# ProPrj_PEDRO.net
KiCad netlist of a schematic drawn in EasyEDA Pro
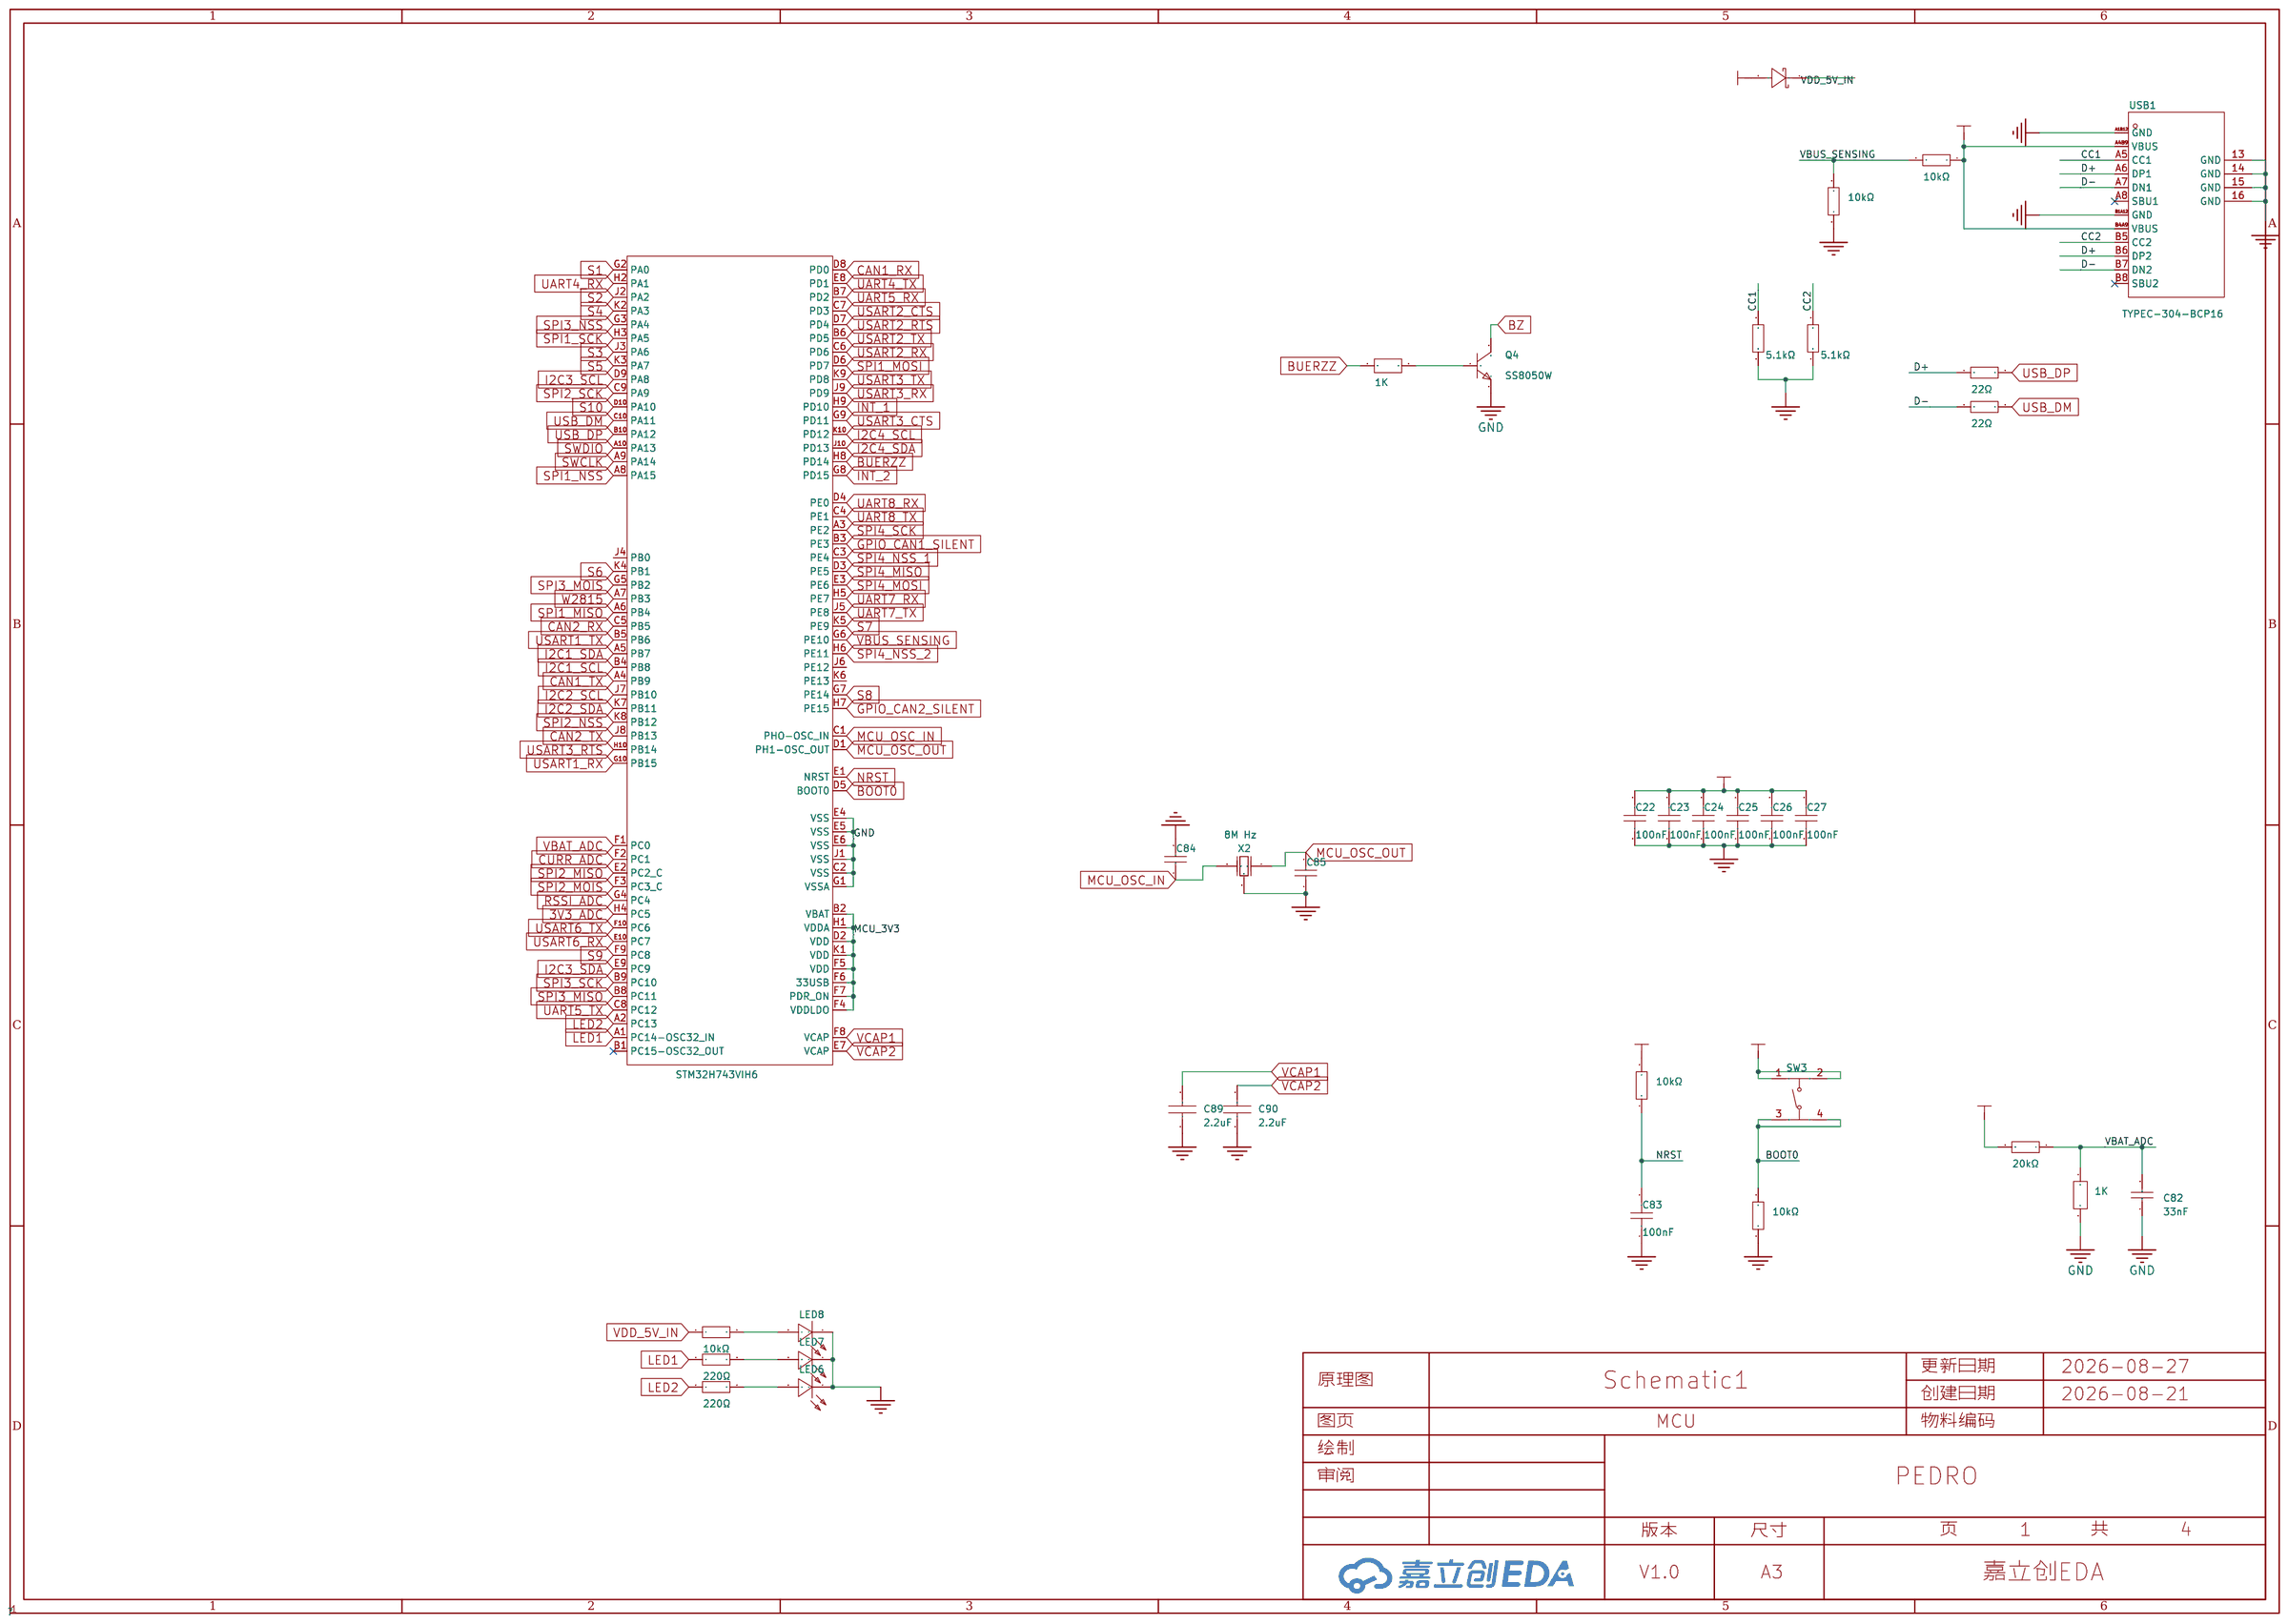
[diagram p0: MCU]
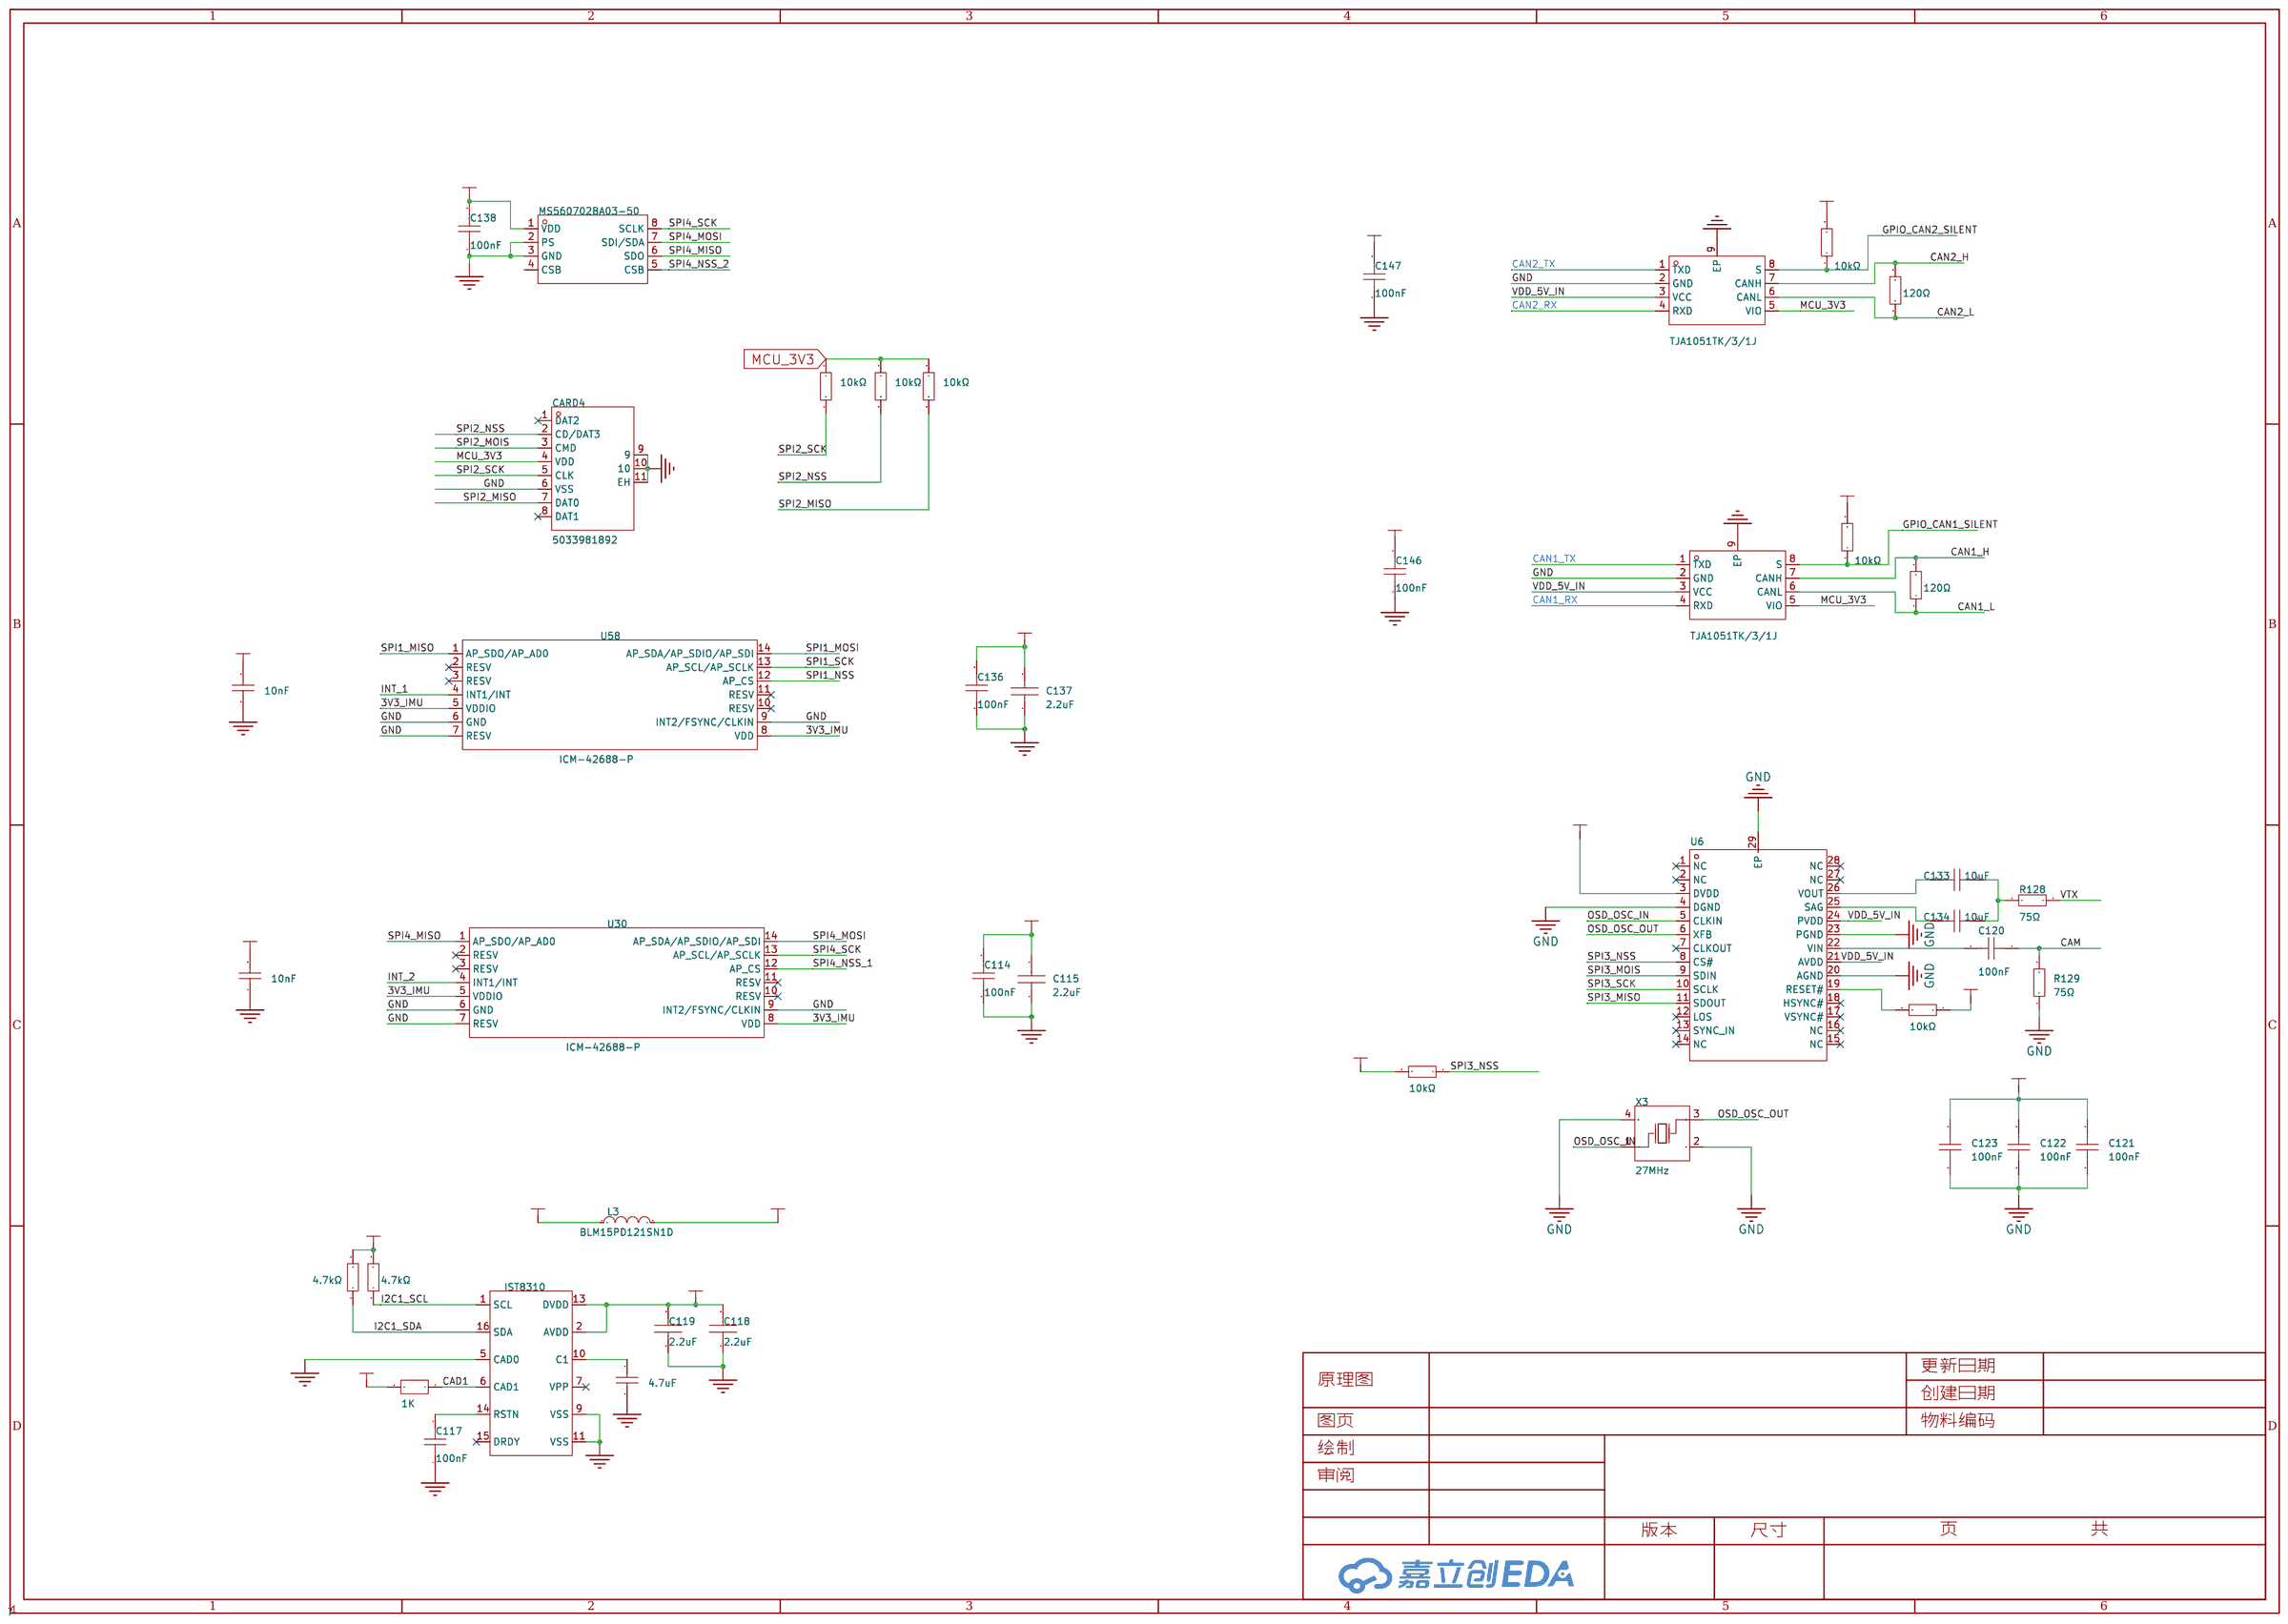
[diagram p1: 传感器]
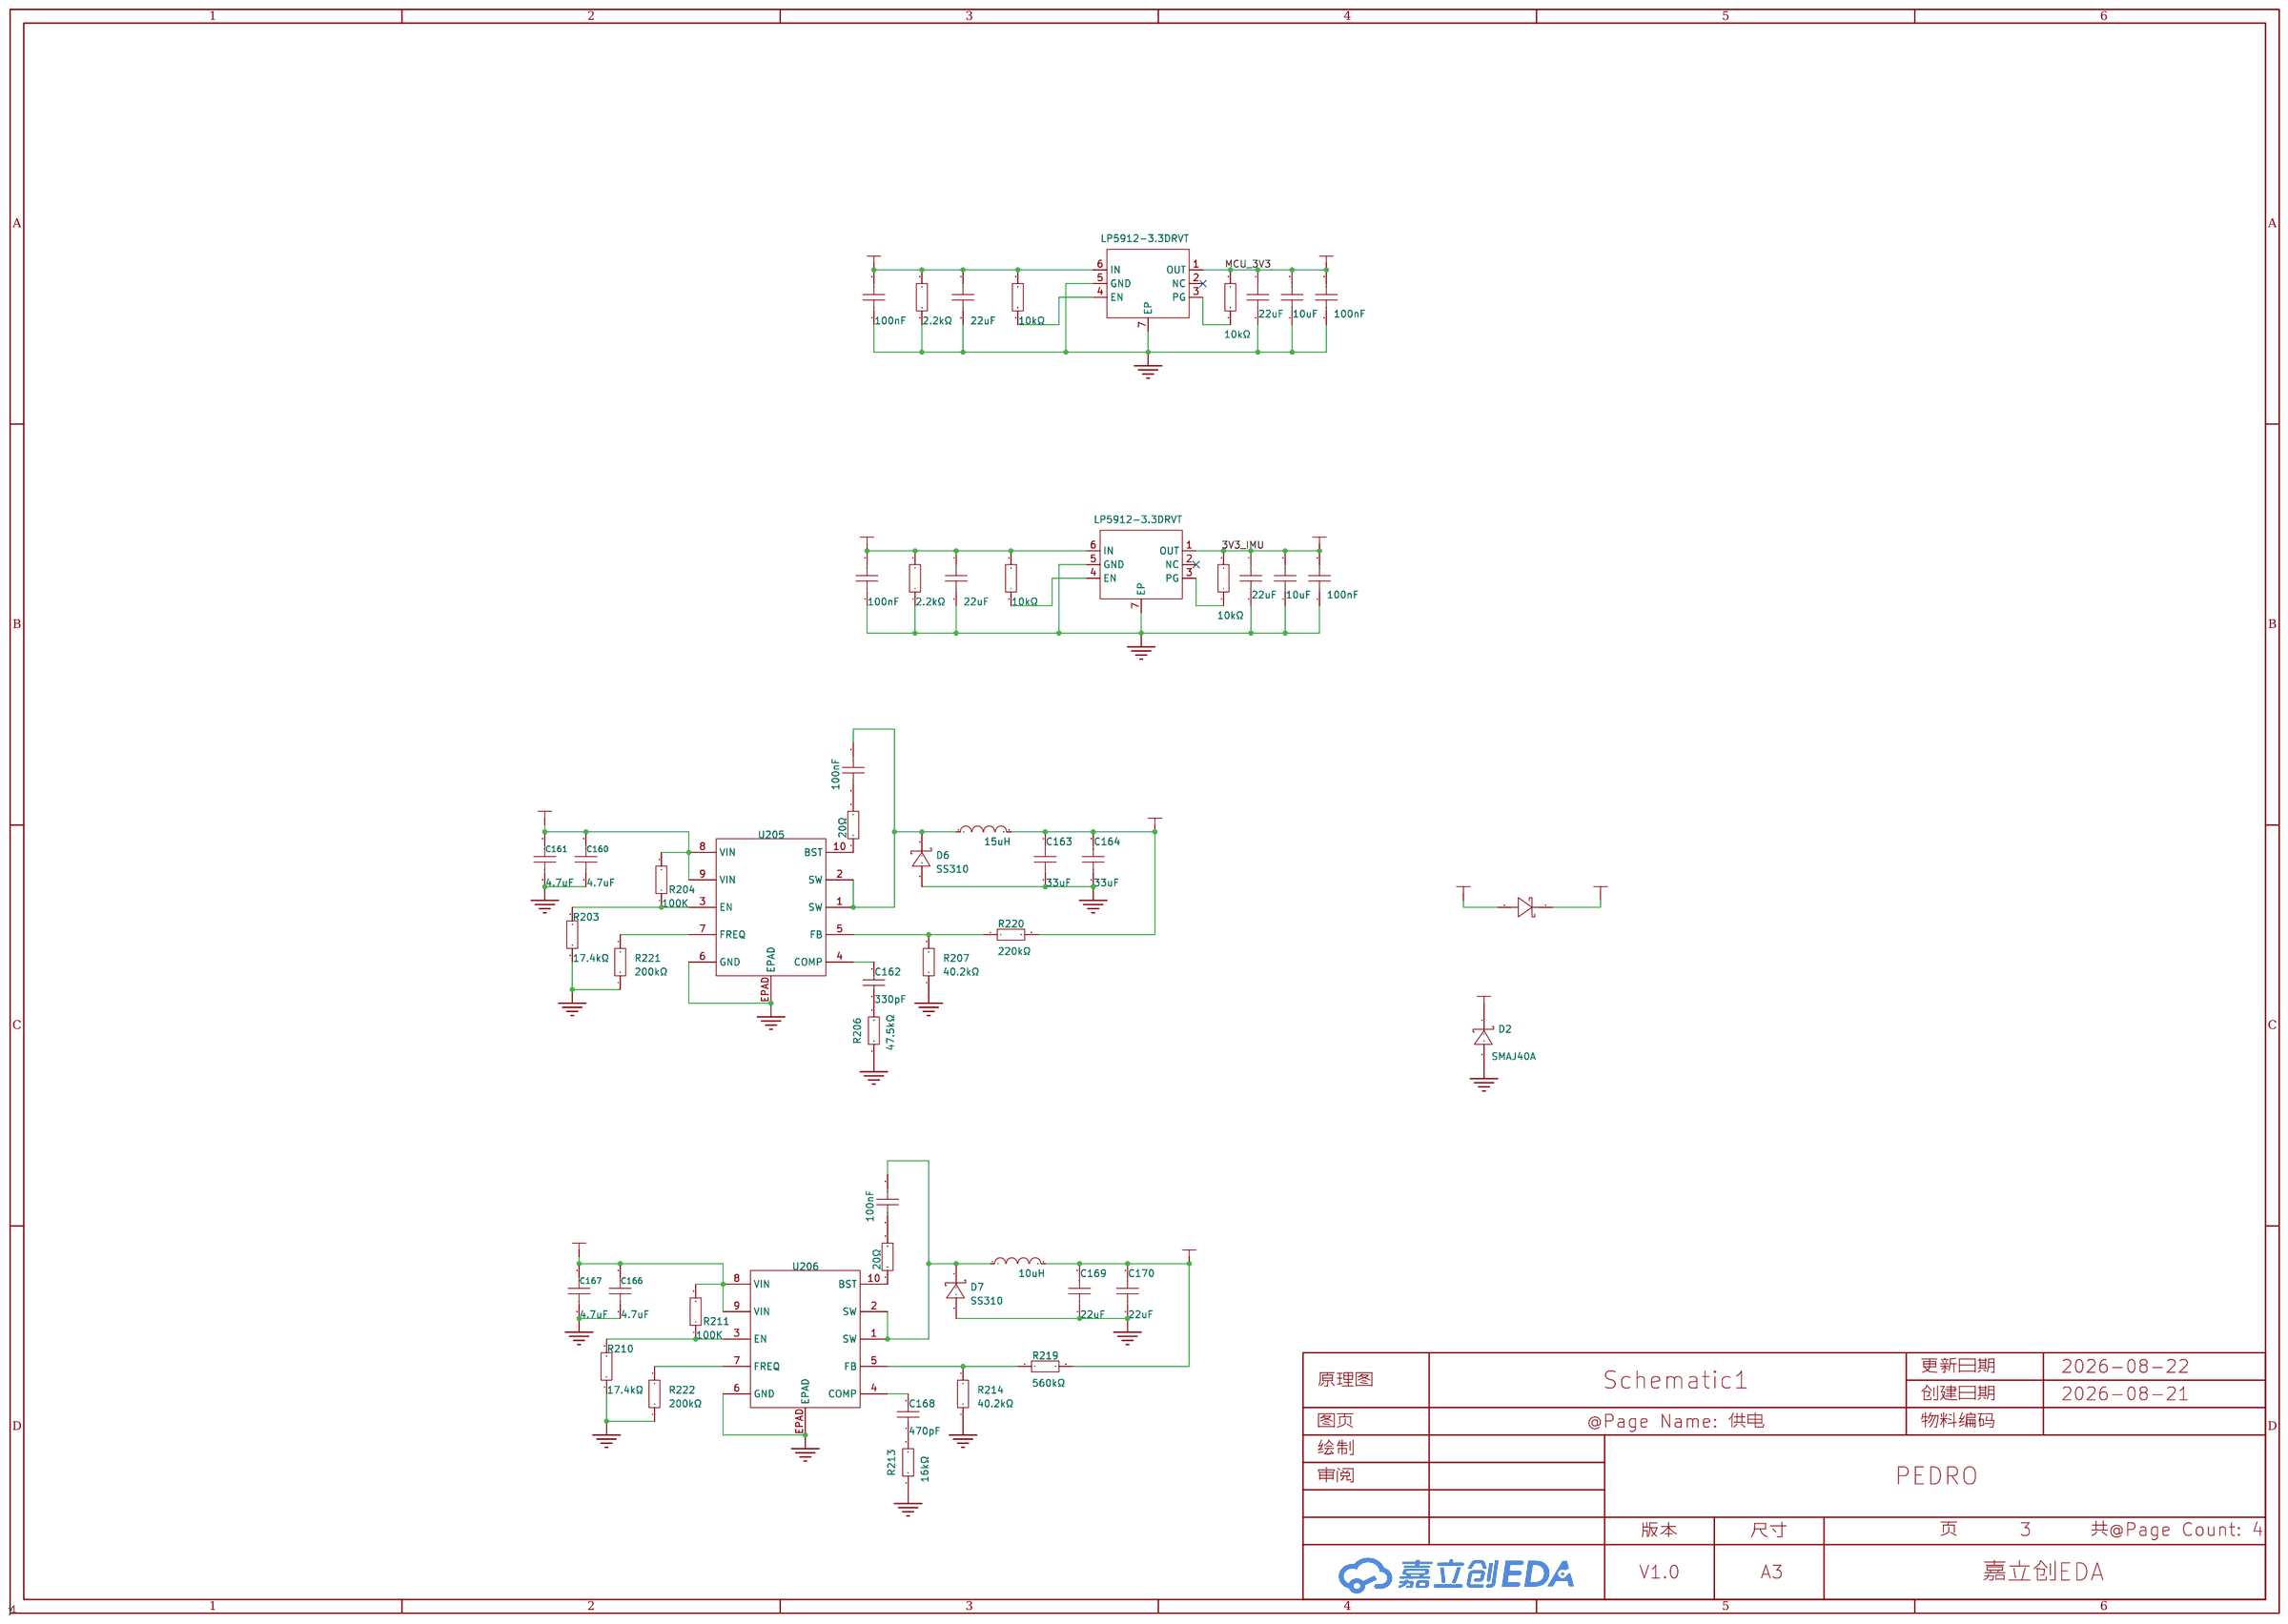
[diagram p2: 供电]
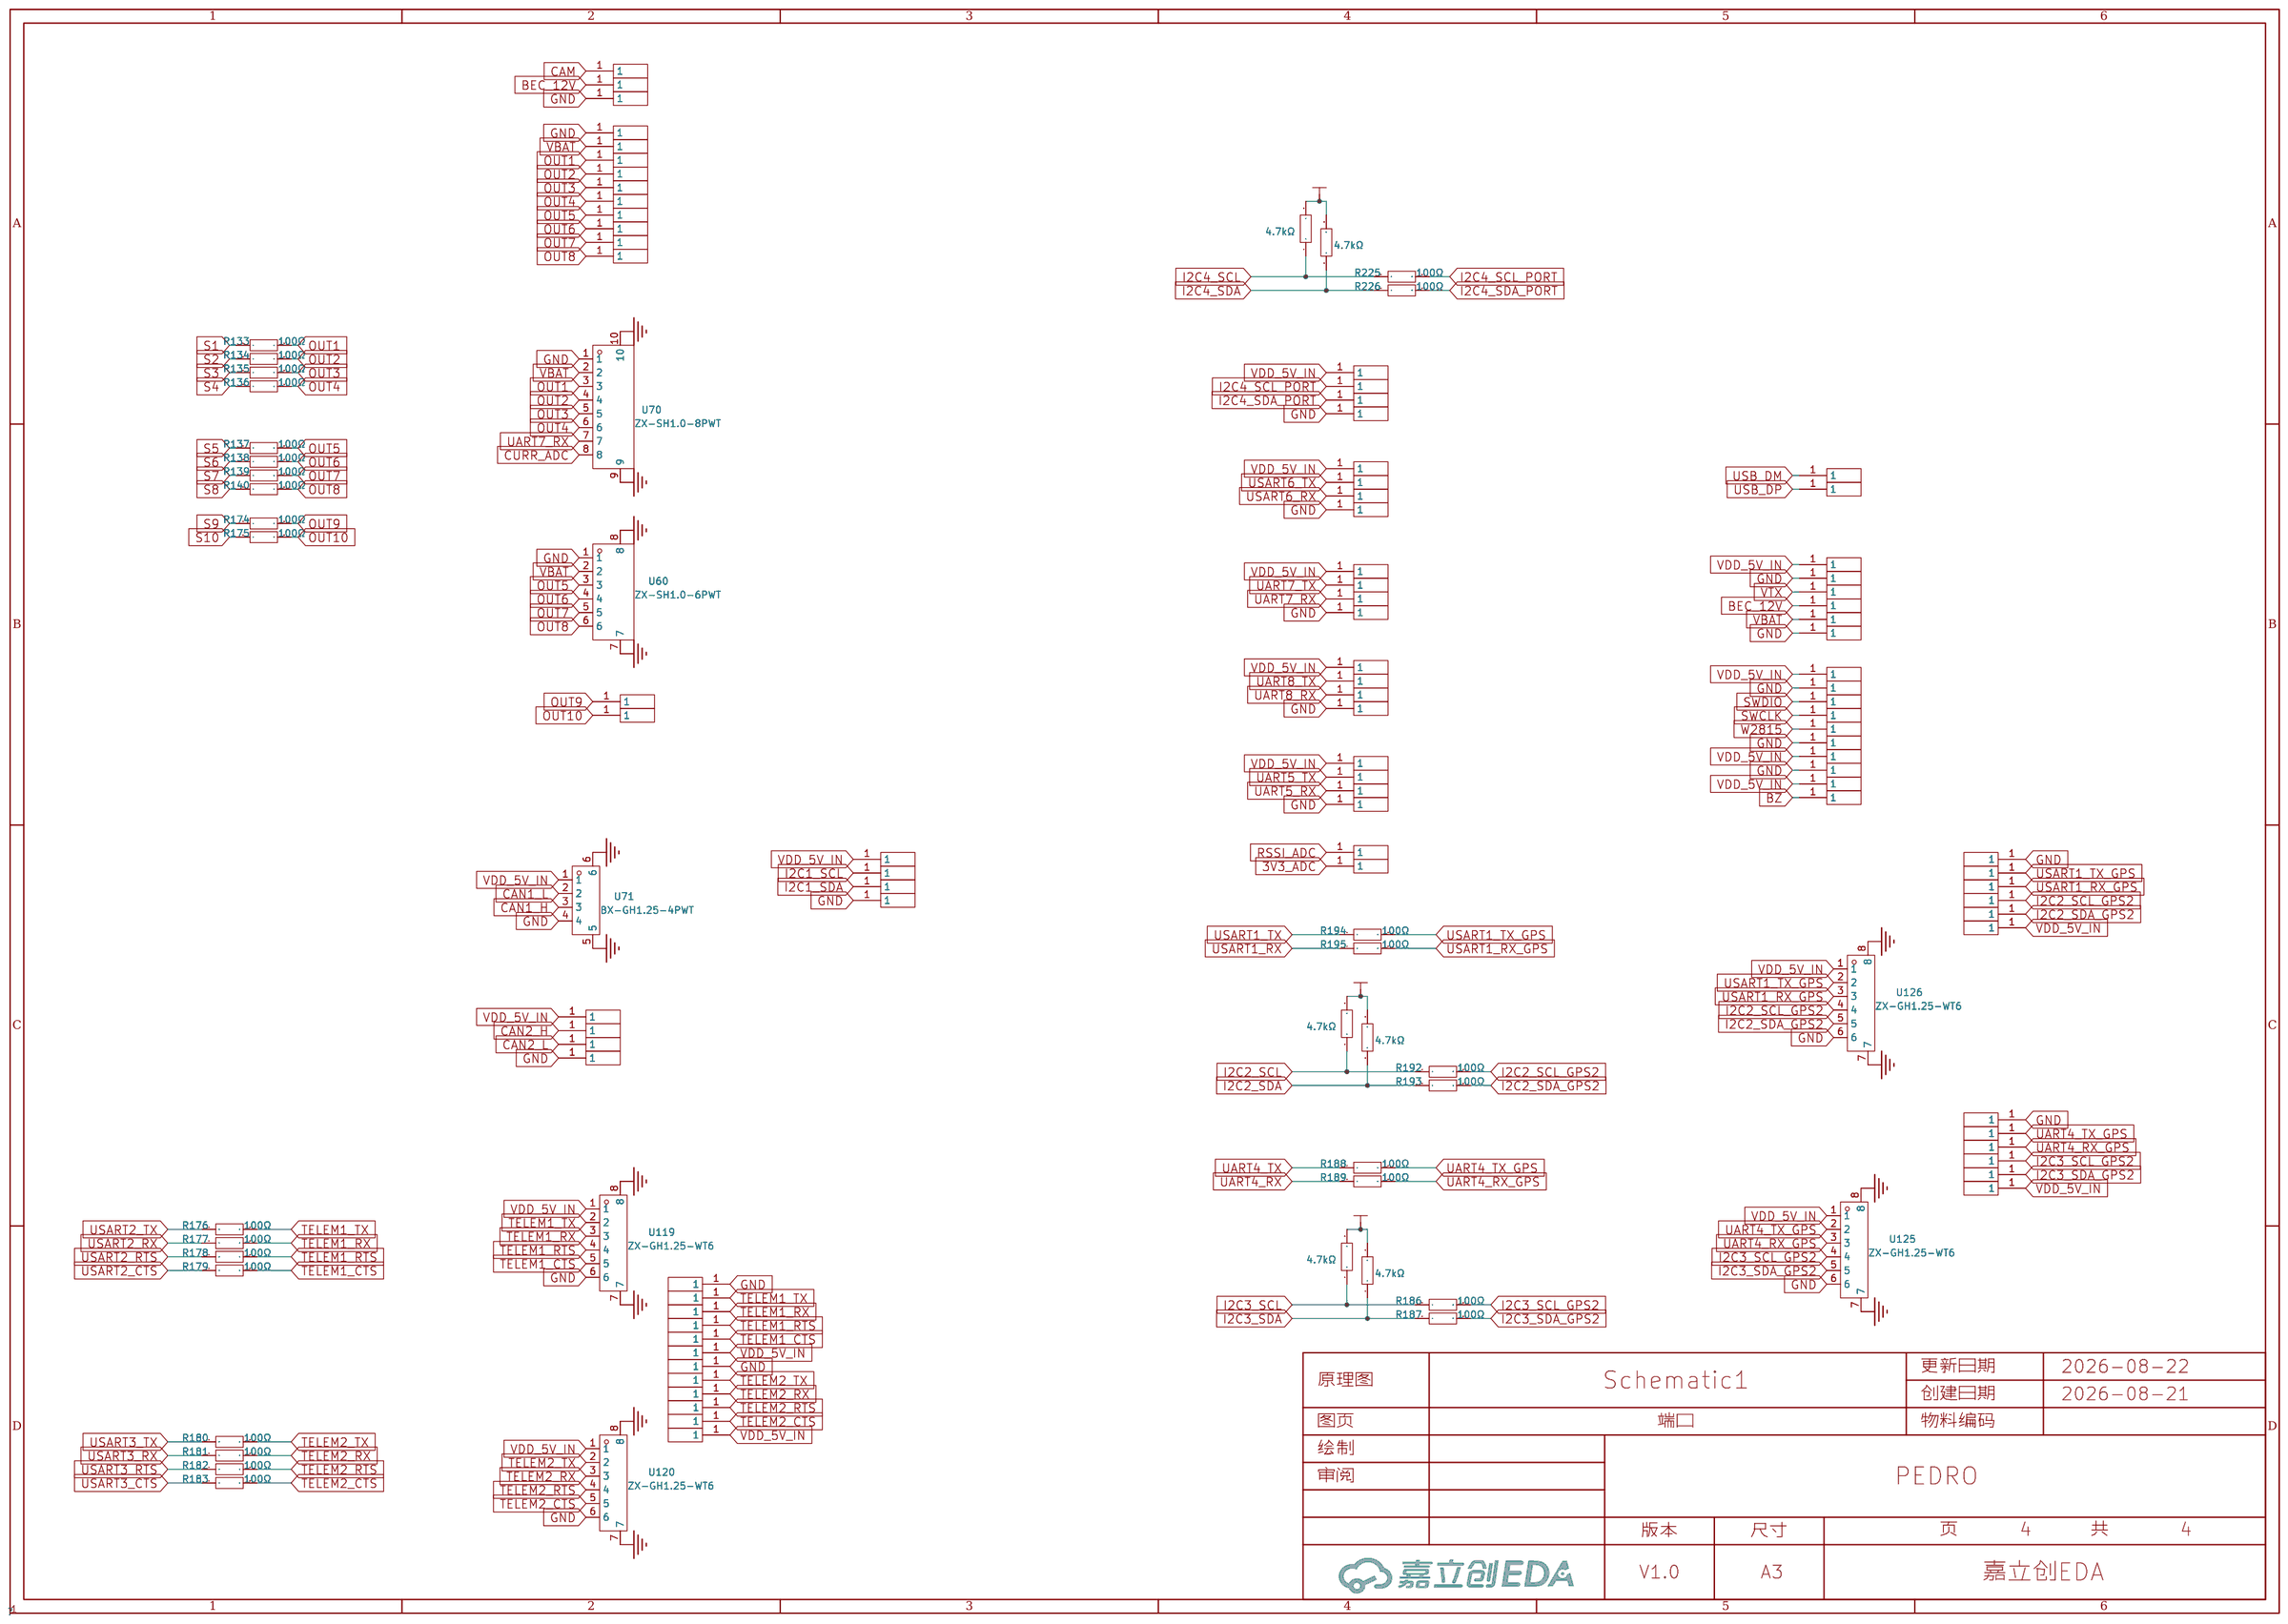
[diagram p3: 端口]

(export (version "E")
  (design (tool "Eeschema 10.0.6"))
  (components
    (comp (ref "C22")
      (value "100nF")
      (footprint "easyedapro:C0402")
      (description "容值:100nF;精度:±10%;额定电压:16V;材质(温度系数):X7R;")
      (fields
        (field (name "Manufacturer Part") "CC0402KRX7R7BB104")
        (field (name "Manufacturer") "YAGEO(国巨)")
      )
      (libsource (lib "easyedapro") (part "CC0402KRX7R7BB104"))
    )
    (comp (ref "C23")
      (value "100nF")
      (footprint "easyedapro:C0402")
      (description "容值:100nF;精度:±10%;额定电压:16V;材质(温度系数):X7R;")
      (fields
        (field (name "Manufacturer Part") "CC0402KRX7R7BB104")
        (field (name "Manufacturer") "YAGEO(国巨)")
      )
      (libsource (lib "easyedapro") (part "CC0402KRX7R7BB104"))
    )
    (comp (ref "C24")
      (value "100nF")
      (footprint "easyedapro:C0402")
      (description "容值:100nF;精度:±10%;额定电压:16V;材质(温度系数):X7R;")
      (fields
        (field (name "Manufacturer Part") "CC0402KRX7R7BB104")
        (field (name "Manufacturer") "YAGEO(国巨)")
      )
      (libsource (lib "easyedapro") (part "CC0402KRX7R7BB104"))
    )
    (comp (ref "C25")
      (value "100nF")
      (footprint "easyedapro:C0402")
      (description "容值:100nF;精度:±10%;额定电压:16V;材质(温度系数):X7R;")
      (fields
        (field (name "Manufacturer Part") "CC0402KRX7R7BB104")
        (field (name "Manufacturer") "YAGEO(国巨)")
      )
      (libsource (lib "easyedapro") (part "CC0402KRX7R7BB104"))
    )
    (comp (ref "C26")
      (value "100nF")
      (footprint "easyedapro:C0402")
      (description "容值:100nF;精度:±10%;额定电压:16V;材质(温度系数):X7R;")
      (fields
        (field (name "Manufacturer Part") "CC0402KRX7R7BB104")
        (field (name "Manufacturer") "YAGEO(国巨)")
      )
      (libsource (lib "easyedapro") (part "CC0402KRX7R7BB104"))
    )
    (comp (ref "C27")
      (value "100nF")
      (footprint "easyedapro:C0402")
      (description "容值:100nF;精度:±10%;额定电压:16V;材质(温度系数):X7R;")
      (fields
        (field (name "Manufacturer Part") "CC0402KRX7R7BB104")
        (field (name "Manufacturer") "YAGEO(国巨)")
      )
      (libsource (lib "easyedapro") (part "CC0402KRX7R7BB104"))
    )
    (comp (ref "C82")
      (value "33nF")
      (footprint "easyedapro:C0402")
      (description "容值:33nF;精度:±10%;额定电压:50V;材质(温度系数):X7R;")
      (fields
        (field (name "Manufacturer Part") "CC0402KRX7R9BB333")
        (field (name "Manufacturer") "YAGEO(国巨)")
      )
      (libsource (lib "easyedapro") (part "CC0402KRX7R9BB333"))
    )
    (comp (ref "C83")
      (value "100nF")
      (footprint "easyedapro:C0402")
      (description "容值:100nF;精度:±10%;额定电压:16V;材质(温度系数):X7R;")
      (fields
        (field (name "Manufacturer Part") "CC0402KRX7R7BB104")
        (field (name "Manufacturer") "YAGEO(国巨)")
      )
      (libsource (lib "easyedapro") (part "CC0402KRX7R7BB104"))
    )
    (comp (ref "C84")
      (value "12pF")
      (footprint "easyedapro:C0402")
      (description "容值:12pF;精度:±5%;额定电压:50V;材质(温度系数):C0G;")
      (fields (field (name "Manufacturer Part") "0402CG120J500NT") (field (name "Manufacturer") "FH(风华)"))
      (libsource (lib "easyedapro") (part "0402CG120J500NT"))
    )
    (comp (ref "C85")
      (value "12pF")
      (footprint "easyedapro:C0402")
      (description "容值:12pF;精度:±5%;额定电压:50V;材质(温度系数):C0G;")
      (fields (field (name "Manufacturer Part") "0402CG120J500NT") (field (name "Manufacturer") "FH(风华)"))
      (libsource (lib "easyedapro") (part "0402CG120J500NT"))
    )
    (comp (ref "C89")
      (value "2.2uF")
      (footprint "easyedapro:C0402")
      (description "容值:2.2uF;精度:±20%;额定电压:6.3V;材质(温度系数):X5R;")
      (fields
        (field (name "Manufacturer Part") "CL05A225MQ5NSNC")
        (field (name "Manufacturer") "SAMSUNG(三星)")
      )
      (libsource (lib "easyedapro") (part "CL05A225MQ5NSNC"))
    )
    (comp (ref "C90")
      (value "2.2uF")
      (footprint "easyedapro:C0402")
      (description "容值:2.2uF;精度:±20%;额定电压:6.3V;材质(温度系数):X5R;")
      (fields
        (field (name "Manufacturer Part") "CL05A225MQ5NSNC")
        (field (name "Manufacturer") "SAMSUNG(三星)")
      )
      (libsource (lib "easyedapro") (part "CL05A225MQ5NSNC"))
    )
    (comp (ref "D4")
      (value "DSK34")
      (footprint "easyedapro:SOD-123_L2.8-W1.8-LS3.7-RD")
      (description "二极管配置:-;正向压降(Vf):550mV@3A;直流反向耐压(Vr):40V;平均整流电流(Io):3A;")
      (fields (field (name "Manufacturer") "FUXINSEMI(富芯森美)"))
      (libsource (lib "easyedapro") (part "DSK34_C908230"))
    )
    (comp (ref "LED6")
      (value "NCD0402R1")
      (footprint "easyedapro:LED0402-RD")
      (fields (field (name "Manufacturer") "国星光电"))
      (libsource (lib "easyedapro") (part "FC-F1005HRK-620H5"))
    )
    (comp (ref "LED7")
      (value "NCD0402R1")
      (footprint "easyedapro:LED0402-RD")
      (fields (field (name "Manufacturer") "国星光电"))
      (libsource (lib "easyedapro") (part "FC-F1005HRK-620H5"))
    )
    (comp (ref "LED8")
      (value "NCD0402R1")
      (footprint "easyedapro:LED0402-RD")
      (fields (field (name "Manufacturer") "国星光电"))
      (libsource (lib "easyedapro") (part "FC-F1005HRK-620H5"))
    )
    (comp (ref "Q4")
      (value "SS8050W")
      (footprint "easyedapro:SOT-323-3_L2.1-W1.3-P1.30-LS2.3-BR")
      (description "晶体管类型:-;集电极电流(Ic):-;集射极击穿电压(Vceo):-;功率(Pd):-;")
      (fields (field (name "Manufacturer") "CBI(创基)"))
      (libsource (lib "easyedapro") (part "SS8050W"))
    )
    (comp (ref "R99")
      (value "5.1kΩ")
      (footprint "easyedapro:R0402")
      (description "电阻类型:厚膜电阻;阻值:5.1kΩ;精度:±1%;功率:62.5mW;最大工作电压:50V;温度系数:±100ppm/°C;")
      (fields
        (field (name "Manufacturer Part") "0402WGF5101TCE")
        (field (name "Manufacturer") "UNI-ROYAL(厚声)")
      )
      (libsource (lib "easyedapro") (part "0402WGF5101TCE"))
    )
    (comp (ref "R100")
      (value "5.1kΩ")
      (footprint "easyedapro:R0402")
      (description "电阻类型:厚膜电阻;阻值:5.1kΩ;精度:±1%;功率:62.5mW;最大工作电压:50V;温度系数:±100ppm/°C;")
      (fields
        (field (name "Manufacturer Part") "0402WGF5101TCE")
        (field (name "Manufacturer") "UNI-ROYAL(厚声)")
      )
      (libsource (lib "easyedapro") (part "0402WGF5101TCE"))
    )
    (comp (ref "R101")
      (value "22Ω")
      (footprint "easyedapro:R0402")
      (description "电阻类型:厚膜电阻;阻值:22Ω;精度:±1%;功率:62.5mW;最大工作电压:50V;温度系数:±100ppm/°C;")
      (fields
        (field (name "Manufacturer Part") "0402WGF220JTCE")
        (field (name "Manufacturer") "UNI-ROYAL(厚声)")
      )
      (libsource (lib "easyedapro") (part "0402WGF220JTCE"))
    )
    (comp (ref "R102")
      (value "22Ω")
      (footprint "easyedapro:R0402")
      (description "电阻类型:厚膜电阻;阻值:22Ω;精度:±1%;功率:62.5mW;最大工作电压:50V;温度系数:±100ppm/°C;")
      (fields
        (field (name "Manufacturer Part") "0402WGF220JTCE")
        (field (name "Manufacturer") "UNI-ROYAL(厚声)")
      )
      (libsource (lib "easyedapro") (part "0402WGF220JTCE"))
    )
    (comp (ref "R108")
      (value "10kΩ")
      (footprint "easyedapro:R0402")
      (description "电阻类型:厚膜电阻;阻值:10kΩ;精度:±1%;功率:62.5mW;最大工作电压:50V;温度系数:±100ppm/°C;")
      (fields (field (name "Manufacturer Part") "RC0402FR-0710KL") (field (name "Manufacturer") "YAGEO(国巨)"))
      (libsource (lib "easyedapro") (part "RC0402FR-0710KL"))
    )
    (comp (ref "R109")
      (value "10kΩ")
      (footprint "easyedapro:R0402")
      (description "电阻类型:厚膜电阻;阻值:10kΩ;精度:±1%;功率:62.5mW;最大工作电压:50V;温度系数:±100ppm/°C;")
      (fields (field (name "Manufacturer Part") "RC0402FR-0710KL") (field (name "Manufacturer") "YAGEO(国巨)"))
      (libsource (lib "easyedapro") (part "RC0402FR-0710KL"))
    )
    (comp (ref "R118")
      (value "10kΩ")
      (footprint "easyedapro:R0402")
      (description "电阻类型:厚膜电阻;阻值:10kΩ;精度:±1%;功率:62.5mW;最大工作电压:50V;温度系数:±100ppm/°C;")
      (fields (field (name "Manufacturer Part") "RC0402FR-0710KL") (field (name "Manufacturer") "YAGEO(国巨)"))
      (libsource (lib "easyedapro") (part "RC0402FR-0710KL"))
    )
    (comp (ref "R119")
      (value "10kΩ")
      (footprint "easyedapro:R0402")
      (description "电阻类型:厚膜电阻;阻值:10kΩ;精度:±1%;功率:62.5mW;最大工作电压:50V;温度系数:±100ppm/°C;")
      (fields (field (name "Manufacturer Part") "RC0402FR-0710KL") (field (name "Manufacturer") "YAGEO(国巨)"))
      (libsource (lib "easyedapro") (part "RC0402FR-0710KL"))
    )
    (comp (ref "R143")
      (value "10kΩ")
      (footprint "easyedapro:R0402")
      (description "电阻类型:厚膜电阻;阻值:10kΩ;精度:±1%;功率:62.5mW;最大工作电压:50V;温度系数:±100ppm/°C;")
      (fields (field (name "Manufacturer Part") "RC0402FR-0710KL") (field (name "Manufacturer") "YAGEO(国巨)"))
      (libsource (lib "easyedapro") (part "RC0402FR-0710KL"))
    )
    (comp (ref "R170")
      (value "20kΩ")
      (footprint "easyedapro:R0402")
      (description "电阻类型:厚膜电阻;阻值:10kΩ;精度:±1%;功率:62.5mW;最大工作电压:50V;温度系数:±100ppm/°C;")
      (fields (field (name "Manufacturer Part") "RC0402FR-0710KL") (field (name "Manufacturer") "YAGEO(国巨)"))
      (libsource (lib "easyedapro") (part "RC0402FR-0710KL"))
    )
    (comp (ref "R171")
      (value "1K")
      (footprint "easyedapro:R0402")
      (description "电阻类型:厚膜电阻;阻值:22Ω;精度:±1%;功率:200mW;温度系数:±100ppm/°C;最大工作电压:-;工作温度范围:-55°C~+155°C;")
      (fields (field (name "Manufacturer Part") "ERJPA2F22R0X") (field (name "Manufacturer") "PANASONIC(松下)"))
      (libsource (lib "easyedapro") (part "ERJPA2F22R0X"))
    )
    (comp (ref "R228")
      (value "1K")
      (footprint "easyedapro:R0402")
      (description "电阻类型:厚膜电阻;阻值:22Ω;精度:±1%;功率:200mW;温度系数:±100ppm/°C;最大工作电压:-;工作温度范围:-55°C~+155°C;")
      (fields (field (name "Manufacturer Part") "ERJPA2F22R0X") (field (name "Manufacturer") "PANASONIC(松下)"))
      (libsource (lib "easyedapro") (part "ERJPA2F22R0X"))
    )
    (comp (ref "R229")
      (value "220Ω")
      (footprint "easyedapro:R0402")
      (description "电阻类型:厚膜电阻;阻值:220Ω;精度:±1%;功率:62.5mW;最大工作电压:50V;温度系数:±100ppm/°C;")
      (fields
        (field (name "Manufacturer Part") "0402WGF2200TCE")
        (field (name "Manufacturer") "UNI-ROYAL(厚声)")
      )
      (libsource (lib "easyedapro") (part "0402WGF2200TCE"))
    )
    (comp (ref "R230")
      (value "220Ω")
      (footprint "easyedapro:R0402")
      (description "电阻类型:厚膜电阻;阻值:220Ω;精度:±1%;功率:62.5mW;最大工作电压:50V;温度系数:±100ppm/°C;")
      (fields
        (field (name "Manufacturer Part") "0402WGF2200TCE")
        (field (name "Manufacturer") "UNI-ROYAL(厚声)")
      )
      (libsource (lib "easyedapro") (part "0402WGF2200TCE"))
    )
    (comp (ref "SW3")
      (value "TS-1089S-02526")
      (footprint "easyedapro:SW-SMD_4P-L4.2-W3.3-P2.15-LS5.1")
      (description "电路结构:单刀单掷;按钮形状:椭圆形按钮;安装方式:立贴;开关长度:4.2mm;开关宽度:3.25mm;开关高度:2.5mm;触点电流:50mA;额定电压(DC):12V;带灯:-;机械寿命:-;")
      (fields (field (name "Manufacturer") "XUNPU(讯普)"))
      (libsource (lib "easyedapro") (part "TS-1089S-02526"))
    )
    (comp (ref "U65")
      (value "STM32H743VIH6")
      (footprint "easyedapro:BGA-100_L8.0-W8.0-P0.80-R10-C10-BL")
      (description "32位Arm Cortex -M7 480MHz mcu,高达2MB的Flash,高达1MB的RAM,46com和模拟接口")
      (fields (field (name "Manufacturer") "ST(意法半导体)"))
      (libsource (lib "easyedapro") (part "STM32H743VIH6"))
    )
    (comp (ref "USB1")
      (value "TYPEC-304-BCP16")
      (footprint "easyedapro:USB-C-SMD_TYPEC-304-BCP16_2")
      (fields (field (name "Manufacturer") "XUNPU(讯普)"))
      (libsource (lib "easyedapro") (part "TYPEC-304-BCP16_2"))
    )
    (comp (ref "X2")
      (value "8M Hz")
      (footprint "easyedapro:OSC-SMD_3P-L3.2-W1.3-P1.20-L")
      (fields
        (field (name "Manufacturer Part") "CSTNE8M00GH5C000R0")
        (field (name "Manufacturer") "muRata(村田)")
      )
      (libsource (lib "easyedapro") (part "CSTNE8M00GH5C000R0"))
    )
    (comp (ref "C32")
      (value "10nF")
      (footprint "easyedapro:C0402")
      (description "容值:10nF;精度:±10%;额定电压:50V;材质(温度系数):X7R;")
      (fields
        (field (name "Manufacturer Part") "CC0402KRX7R9BB103")
        (field (name "Manufacturer") "YAGEO(国巨)")
      )
      (libsource (lib "easyedapro") (part "CC0402KRX7R9BB103"))
    )
    (comp (ref "C102")
      (value "4.7uF")
      (footprint "easyedapro:C0402")
      (description "容值:4.7uF;精度:±20%;额定电压:10V;材质(温度系数):X5R;")
      (fields
        (field (name "Manufacturer Part") "CL05A475MP5NRNC")
        (field (name "Manufacturer") "SAMSUNG(三星)")
      )
      (libsource (lib "easyedapro") (part "CL05A475MP5NRNC"))
    )
    (comp (ref "C114")
      (value "100nF")
      (footprint "easyedapro:C0402")
      (description "容值:100nF;精度:±10%;额定电压:16V;材质(温度系数):X7R;")
      (fields
        (field (name "Manufacturer Part") "CC0402KRX7R7BB104")
        (field (name "Manufacturer") "YAGEO(国巨)")
      )
      (libsource (lib "easyedapro") (part "CC0402KRX7R7BB104"))
    )
    (comp (ref "C115")
      (value "2.2uF")
      (footprint "easyedapro:C0402")
      (description "容值:2.2uF;精度:±20%;额定电压:6.3V;材质(温度系数):X5R;")
      (fields
        (field (name "Manufacturer Part") "CL05A225MQ5NSNC")
        (field (name "Manufacturer") "SAMSUNG(三星)")
      )
      (libsource (lib "easyedapro") (part "CL05A225MQ5NSNC"))
    )
    (comp (ref "C117")
      (value "100nF")
      (footprint "easyedapro:C0402")
      (description "容值:100nF;精度:±10%;额定电压:16V;材质(温度系数):X7R;")
      (fields
        (field (name "Manufacturer Part") "CC0402KRX7R7BB104")
        (field (name "Manufacturer") "YAGEO(国巨)")
      )
      (libsource (lib "easyedapro") (part "CC0402KRX7R7BB104"))
    )
    (comp (ref "C118")
      (value "2.2uF")
      (footprint "easyedapro:C0402")
      (description "容值:2.2uF;精度:±20%;额定电压:6.3V;材质(温度系数):X5R;")
      (fields
        (field (name "Manufacturer Part") "CL05A225MQ5NSNC")
        (field (name "Manufacturer") "SAMSUNG(三星)")
      )
      (libsource (lib "easyedapro") (part "CL05A225MQ5NSNC"))
    )
    (comp (ref "C119")
      (value "2.2uF")
      (footprint "easyedapro:C0402")
      (description "容值:2.2uF;精度:±20%;额定电压:6.3V;材质(温度系数):X5R;")
      (fields
        (field (name "Manufacturer Part") "CL05A225MQ5NSNC")
        (field (name "Manufacturer") "SAMSUNG(三星)")
      )
      (libsource (lib "easyedapro") (part "CL05A225MQ5NSNC"))
    )
    (comp (ref "C120")
      (value "100nF")
      (footprint "easyedapro:C0402")
      (description "容值:100nF;精度:±10%;额定电压:16V;材质(温度系数):X7R;")
      (fields
        (field (name "Manufacturer Part") "CC0402KRX7R7BB104")
        (field (name "Manufacturer") "YAGEO(国巨)")
      )
      (libsource (lib "easyedapro") (part "CC0402KRX7R7BB104"))
    )
    (comp (ref "C121")
      (value "100nF")
      (footprint "easyedapro:C0402")
      (description "容值:100nF;精度:±10%;额定电压:16V;材质(温度系数):X7R;")
      (fields
        (field (name "Manufacturer Part") "CC0402KRX7R7BB104")
        (field (name "Manufacturer") "YAGEO(国巨)")
      )
      (libsource (lib "easyedapro") (part "CC0402KRX7R7BB104"))
    )
    (comp (ref "C122")
      (value "100nF")
      (footprint "easyedapro:C0402")
      (description "容值:100nF;精度:±10%;额定电压:16V;材质(温度系数):X7R;")
      (fields
        (field (name "Manufacturer Part") "CC0402KRX7R7BB104")
        (field (name "Manufacturer") "YAGEO(国巨)")
      )
      (libsource (lib "easyedapro") (part "CC0402KRX7R7BB104"))
    )
    (comp (ref "C123")
      (value "100nF")
      (footprint "easyedapro:C0402")
      (description "容值:100nF;精度:±10%;额定电压:16V;材质(温度系数):X7R;")
      (fields
        (field (name "Manufacturer Part") "CC0402KRX7R7BB104")
        (field (name "Manufacturer") "YAGEO(国巨)")
      )
      (libsource (lib "easyedapro") (part "CC0402KRX7R7BB104"))
    )
    (comp (ref "C133")
      (value "10uF")
      (footprint "easyedapro:C0603")
      (description "容值:10uF;精度:±10%;额定电压:10V;材质(温度系数):X5R;")
      (fields
        (field (name "Manufacturer Part") "CL10A106KP8NNNC")
        (field (name "Manufacturer") "SAMSUNG(三星)")
      )
      (libsource (lib "easyedapro") (part "CL10A106KP8NNNC"))
    )
    (comp (ref "C134")
      (value "10uF")
      (footprint "easyedapro:C0603")
      (description "容值:10uF;精度:±10%;额定电压:10V;材质(温度系数):X5R;")
      (fields
        (field (name "Manufacturer Part") "CL10A106KP8NNNC")
        (field (name "Manufacturer") "SAMSUNG(三星)")
      )
      (libsource (lib "easyedapro") (part "CL10A106KP8NNNC"))
    )
    (comp (ref "C135")
      (value "10nF")
      (footprint "easyedapro:C0402")
      (description "容值:10nF;精度:±10%;额定电压:50V;材质(温度系数):X7R;")
      (fields
        (field (name "Manufacturer Part") "CC0402KRX7R9BB103")
        (field (name "Manufacturer") "YAGEO(国巨)")
      )
      (libsource (lib "easyedapro") (part "CC0402KRX7R9BB103"))
    )
    (comp (ref "C136")
      (value "100nF")
      (footprint "easyedapro:C0402")
      (description "容值:100nF;精度:±10%;额定电压:16V;材质(温度系数):X7R;")
      (fields
        (field (name "Manufacturer Part") "CC0402KRX7R7BB104")
        (field (name "Manufacturer") "YAGEO(国巨)")
      )
      (libsource (lib "easyedapro") (part "CC0402KRX7R7BB104"))
    )
    (comp (ref "C137")
      (value "2.2uF")
      (footprint "easyedapro:C0402")
      (description "容值:2.2uF;精度:±20%;额定电压:6.3V;材质(温度系数):X5R;")
      (fields
        (field (name "Manufacturer Part") "CL05A225MQ5NSNC")
        (field (name "Manufacturer") "SAMSUNG(三星)")
      )
      (libsource (lib "easyedapro") (part "CL05A225MQ5NSNC"))
    )
    (comp (ref "C138")
      (value "100nF")
      (footprint "easyedapro:C0402")
      (description "容值:100nF;精度:±10%;额定电压:16V;材质(温度系数):X7R;")
      (fields
        (field (name "Manufacturer Part") "CC0402KRX7R7BB104")
        (field (name "Manufacturer") "YAGEO(国巨)")
      )
      (libsource (lib "easyedapro") (part "CC0402KRX7R7BB104"))
    )
    (comp (ref "C146")
      (value "100nF")
      (footprint "easyedapro:C0402")
      (description "容值:100nF;精度:±10%;额定电压:16V;材质(温度系数):X7R;")
      (fields
        (field (name "Manufacturer Part") "CC0402KRX7R7BB104")
        (field (name "Manufacturer") "YAGEO(国巨)")
      )
      (libsource (lib "easyedapro") (part "CC0402KRX7R7BB104"))
    )
    (comp (ref "C147")
      (value "100nF")
      (footprint "easyedapro:C0402")
      (description "容值:100nF;精度:±10%;额定电压:16V;材质(温度系数):X7R;")
      (fields
        (field (name "Manufacturer Part") "CC0402KRX7R7BB104")
        (field (name "Manufacturer") "YAGEO(国巨)")
      )
      (libsource (lib "easyedapro") (part "CC0402KRX7R7BB104"))
    )
    (comp (ref "CARD4")
      (value "5033981892")
      (footprint "easyedapro:TF-SMD_503398-1892")
      (description "卡连接方式:自弹式;卡类型:MicroSD卡(TF卡);连接器类型:卡座;本体最大高度:1.28mm;触头镀层:金;工作温度范围:-25°C~+85°C;")
      (fields (field (name "Manufacturer") "MOLEX"))
      (libsource (lib "easyedapro") (part "503398-1892"))
    )
    (comp (ref "L3")
      (value "BLM15PD121SN1D")
      (footprint "easyedapro:L0402")
      (description "标称阻抗@测试频率:120Ω@100MHz;误差:±25%;直流电阻(RDC):90mΩ;")
      (fields (field (name "Manufacturer") "muRata(村田)"))
      (libsource (lib "easyedapro") (part "BLM15PD121SN1D"))
    )
    (comp (ref "R56")
      (value "120Ω")
      (footprint "easyedapro:R0402")
      (description "电阻类型:厚膜电阻;阻值:120Ω;精度:±1%;功率:62.5mW;")
      (fields
        (field (name "Manufacturer Part") "0402WGF1200TCE")
        (field (name "Manufacturer") "UNI-ROYAL(厚声)")
      )
      (libsource (lib "easyedapro") (part "0402WGF1200TCE"))
    )
    (comp (ref "R76")
      (value "4.7kΩ")
      (footprint "easyedapro:R0402")
      (description "电阻类型:厚膜电阻;阻值:4.7kΩ;精度:±1%;功率:62.5mW;最大工作电压:50V;温度系数:±100ppm/°C;")
      (fields
        (field (name "Manufacturer Part") "0402WGF4701TCE")
        (field (name "Manufacturer") "UNI-ROYAL(厚声)")
      )
      (libsource (lib "easyedapro") (part "0402WGF4701TCE"))
    )
    (comp (ref "R88")
      (value "4.7kΩ")
      (footprint "easyedapro:R0402")
      (description "电阻类型:厚膜电阻;阻值:4.7kΩ;精度:±1%;功率:62.5mW;最大工作电压:50V;温度系数:±100ppm/°C;")
      (fields
        (field (name "Manufacturer Part") "0402WGF4701TCE")
        (field (name "Manufacturer") "UNI-ROYAL(厚声)")
      )
      (libsource (lib "easyedapro") (part "0402WGF4701TCE"))
    )
    (comp (ref "R110")
      (value "10kΩ")
      (footprint "easyedapro:R0402")
      (description "电阻类型:厚膜电阻;阻值:10kΩ;精度:±1%;功率:62.5mW;")
      (fields
        (field (name "Manufacturer Part") "0402WGF1002TCE")
        (field (name "Manufacturer") "UNI-ROYAL(厚声)")
      )
      (libsource (lib "easyedapro") (part "0402WGF1002TCE"))
    )
    (comp (ref "R111")
      (value "10kΩ")
      (footprint "easyedapro:R0402")
      (description "电阻类型:厚膜电阻;阻值:10kΩ;精度:±1%;功率:62.5mW;")
      (fields
        (field (name "Manufacturer Part") "0402WGF1002TCE")
        (field (name "Manufacturer") "UNI-ROYAL(厚声)")
      )
      (libsource (lib "easyedapro") (part "0402WGF1002TCE"))
    )
    (comp (ref "R126")
      (value "1K")
      (footprint "easyedapro:R0402")
      (description "电阻类型:厚膜电阻;阻值:22Ω;精度:±1%;功率:200mW;温度系数:±100ppm/°C;最大工作电压:-;工作温度范围:-55°C~+155°C;")
      (fields (field (name "Manufacturer Part") "ERJPA2F22R0X") (field (name "Manufacturer") "PANASONIC(松下)"))
      (libsource (lib "easyedapro") (part "ERJPA2F22R0X"))
    )
    (comp (ref "R128")
      (value "75Ω")
      (footprint "easyedapro:R0402")
      (description "电阻类型:厚膜电阻;阻值:75Ω;精度:±1%;功率:62.5mW;最大工作电压:50V;温度系数:±100ppm/°C;")
      (fields
        (field (name "Manufacturer Part") "0402WGF750JTCE")
        (field (name "Manufacturer") "UNI-ROYAL(厚声)")
      )
      (libsource (lib "easyedapro") (part "0402WGF750JTCE"))
    )
    (comp (ref "R129")
      (value "75Ω")
      (footprint "easyedapro:R0402")
      (description "电阻类型:厚膜电阻;阻值:75Ω;精度:±1%;功率:62.5mW;最大工作电压:50V;温度系数:±100ppm/°C;")
      (fields
        (field (name "Manufacturer Part") "0402WGF750JTCE")
        (field (name "Manufacturer") "UNI-ROYAL(厚声)")
      )
      (libsource (lib "easyedapro") (part "0402WGF750JTCE"))
    )
    (comp (ref "R130")
      (value "10kΩ")
      (footprint "easyedapro:R0402")
      (description "电阻类型:厚膜电阻;阻值:10kΩ;精度:±1%;功率:62.5mW;最大工作电压:50V;温度系数:±100ppm/°C;")
      (fields (field (name "Manufacturer Part") "RC0402FR-0710KL") (field (name "Manufacturer") "YAGEO(国巨)"))
      (libsource (lib "easyedapro") (part "RC0402FR-0710KL"))
    )
    (comp (ref "R131")
      (value "10kΩ")
      (footprint "easyedapro:R0402")
      (description "电阻类型:厚膜电阻;阻值:10kΩ;精度:±1%;功率:62.5mW;最大工作电压:50V;温度系数:±100ppm/°C;")
      (fields (field (name "Manufacturer Part") "RC0402FR-0710KL") (field (name "Manufacturer") "YAGEO(国巨)"))
      (libsource (lib "easyedapro") (part "RC0402FR-0710KL"))
    )
    (comp (ref "R172")
      (value "120Ω")
      (footprint "easyedapro:R0402")
      (description "电阻类型:厚膜电阻;阻值:120Ω;精度:±1%;功率:62.5mW;")
      (fields
        (field (name "Manufacturer Part") "0402WGF1200TCE")
        (field (name "Manufacturer") "UNI-ROYAL(厚声)")
      )
      (libsource (lib "easyedapro") (part "0402WGF1200TCE"))
    )
    (comp (ref "R173")
      (value "10kΩ")
      (footprint "easyedapro:R0402")
      (description "电阻类型:厚膜电阻;阻值:10kΩ;精度:±1%;功率:62.5mW;最大工作电压:50V;温度系数:±100ppm/°C;")
      (fields (field (name "Manufacturer Part") "RC0402FR-0710KL") (field (name "Manufacturer") "YAGEO(国巨)"))
      (libsource (lib "easyedapro") (part "RC0402FR-0710KL"))
    )
    (comp (ref "R196")
      (value "10kΩ")
      (footprint "easyedapro:R0402")
      (description "电阻类型:厚膜电阻;阻值:10kΩ;精度:±1%;功率:62.5mW;")
      (fields
        (field (name "Manufacturer Part") "0402WGF1002TCE")
        (field (name "Manufacturer") "UNI-ROYAL(厚声)")
      )
      (libsource (lib "easyedapro") (part "0402WGF1002TCE"))
    )
    (comp (ref "R227")
      (value "10kΩ")
      (footprint "easyedapro:R0402")
      (description "电阻类型:厚膜电阻;阻值:10kΩ;精度:±1%;功率:62.5mW;最大工作电压:50V;温度系数:±100ppm/°C;")
      (fields (field (name "Manufacturer Part") "RC0402FR-0710KL") (field (name "Manufacturer") "YAGEO(国巨)"))
      (libsource (lib "easyedapro") (part "RC0402FR-0710KL"))
    )
    (comp (ref "U6")
      (value "AT7456E")
      (footprint "easyedapro:TSSOP-28_L9.7-W4.4-P0.65-LS6.4-BL-EP-2")
      (description "视频字符叠加芯片，跟MAX7456-pin-pin")
      (fields (field (name "Manufacturer") "杭州中科微"))
      (libsource (lib "easyedapro") (part "AT7456E"))
    )
    (comp (ref "U30")
      (value "ICM-42688-P")
      (footprint "easyedapro:LGA-14_L3.0-W2.5-P0.50-TL")
      (description "传感器类型:加速度计陀螺仪;")
      (fields (field (name "Manufacturer") "TDK InvenSense(应美盛)"))
      (libsource (lib "easyedapro") (part "ICM-42688-P"))
    )
    (comp (ref "U37")
      (value "IST8310")
      (footprint "easyedapro:LGA-16_L3.0-W3.0-P0.5-BL")
      (libsource (lib "easyedapro") (part "IST8310"))
    )
    (comp (ref "U38")
      (value "TJA1051TK/3/1J")
      (footprint "easyedapro:HVSON-8_L3.0-W3.0-P0.65-BL-EP")
      (fields (field (name "Manufacturer") "NXP(恩智浦)"))
      (libsource (lib "easyedapro") (part "TJA1051TK/3/1J"))
    )
    (comp (ref "U58")
      (value "ICM-42688-P")
      (footprint "easyedapro:LGA-14_L3.0-W2.5-P0.50-TL")
      (description "传感器类型:加速度计陀螺仪;")
      (fields (field (name "Manufacturer") "TDK InvenSense(应美盛)"))
      (libsource (lib "easyedapro") (part "ICM-42688-P"))
    )
    (comp (ref "U59")
      (value "MS560702BA03-50")
      (footprint "easyedapro:SENSOR-SMD_MS560702BA03-50")
      (description "压力范围:1Kpa~120Kpa;")
      (fields (field (name "Manufacturer") "TE Connectivity(泰科电子)"))
      (libsource (lib "easyedapro") (part "MS560702BA03-50"))
    )
    (comp (ref "U67")
      (value "TJA1051TK/3/1J")
      (footprint "easyedapro:HVSON-8_L3.0-W3.0-P0.65-BL-EP")
      (fields (field (name "Manufacturer") "NXP(恩智浦)"))
      (libsource (lib "easyedapro") (part "TJA1051TK/3/1J"))
    )
    (comp (ref "X3")
      (value "27MHz")
      (footprint "easyedapro:CRYSTAL-SMD_4P-L2.0-W1.6-BL-A")
      (description "频率:24MHz;频率公差:±20ppm;负载电容:10pF;")
      (fields (field (name "Manufacturer Part") "TAXM24M4ZDBCCT2T") (field (name "Manufacturer") "TAE(雅晶鑫)"))
      (libsource (lib "easyedapro") (part "TAXM24M4ZDBCCT2T"))
    )
    (comp (ref "C150")
      (value "22uF")
      (footprint "easyedapro:C0603")
      (description "容值:22uF;精度:±20%;额定电压:16V;材质(温度系数):X5R;")
      (fields
        (field (name "Manufacturer Part") "CL10A226MO7JZNC")
        (field (name "Manufacturer") "SAMSUNG(三星)")
      )
      (libsource (lib "easyedapro") (part "CL10A226MO7JZNC"))
    )
    (comp (ref "C151")
      (value "10uF")
      (footprint "easyedapro:C0603")
      (description "容值:10uF;精度:±20%;额定电压:25V;材质(温度系数):X5R;")
      (fields
        (field (name "Manufacturer Part") "CL10A106MA8NRNC")
        (field (name "Manufacturer") "SAMSUNG(三星)")
      )
      (libsource (lib "easyedapro") (part "CL10A106MA8NRNC"))
    )
    (comp (ref "C152")
      (value "22uF")
      (footprint "easyedapro:C0603")
      (description "容值:22uF;精度:±20%;额定电压:16V;材质(温度系数):X5R;")
      (fields
        (field (name "Manufacturer Part") "CL10A226MO7JZNC")
        (field (name "Manufacturer") "SAMSUNG(三星)")
      )
      (libsource (lib "easyedapro") (part "CL10A226MO7JZNC"))
    )
    (comp (ref "C153")
      (value "100nF")
      (footprint "easyedapro:C0402")
      (description "容值:100nF;精度:±10%;额定电压:50V;材质(温度系数):X7R;")
      (fields
        (field (name "Manufacturer Part") "GRM155R71H104KE14D")
        (field (name "Manufacturer") "muRata(村田)")
      )
      (libsource (lib "easyedapro") (part "GRM155R71H104KE14D"))
    )
    (comp (ref "C154")
      (value "100nF")
      (footprint "easyedapro:C0402")
      (description "容值:100nF;精度:±10%;额定电压:50V;材质(温度系数):X7R;")
      (fields
        (field (name "Manufacturer Part") "GRM155R71H104KE14D")
        (field (name "Manufacturer") "muRata(村田)")
      )
      (libsource (lib "easyedapro") (part "GRM155R71H104KE14D"))
    )
    (comp (ref "C155")
      (value "100nF")
      (footprint "easyedapro:C0402")
      (description "容值:100nF;精度:±10%;额定电压:50V;材质(温度系数):X7R;")
      (fields
        (field (name "Manufacturer Part") "GRM155R71H104KE14D")
        (field (name "Manufacturer") "muRata(村田)")
      )
      (libsource (lib "easyedapro") (part "GRM155R71H104KE14D"))
    )
    (comp (ref "C156")
      (value "22uF")
      (footprint "easyedapro:C0603")
      (description "容值:22uF;精度:±20%;额定电压:16V;材质(温度系数):X5R;")
      (fields
        (field (name "Manufacturer Part") "CL10A226MO7JZNC")
        (field (name "Manufacturer") "SAMSUNG(三星)")
      )
      (libsource (lib "easyedapro") (part "CL10A226MO7JZNC"))
    )
    (comp (ref "C157")
      (value "10uF")
      (footprint "easyedapro:C0603")
      (description "容值:10uF;精度:±20%;额定电压:25V;材质(温度系数):X5R;")
      (fields
        (field (name "Manufacturer Part") "CL10A106MA8NRNC")
        (field (name "Manufacturer") "SAMSUNG(三星)")
      )
      (libsource (lib "easyedapro") (part "CL10A106MA8NRNC"))
    )
    (comp (ref "C158")
      (value "22uF")
      (footprint "easyedapro:C0603")
      (description "容值:22uF;精度:±20%;额定电压:16V;材质(温度系数):X5R;")
      (fields
        (field (name "Manufacturer Part") "CL10A226MO7JZNC")
        (field (name "Manufacturer") "SAMSUNG(三星)")
      )
      (libsource (lib "easyedapro") (part "CL10A226MO7JZNC"))
    )
    (comp (ref "C159")
      (value "100nF")
      (footprint "easyedapro:C0402")
      (description "容值:100nF;精度:±10%;额定电压:50V;材质(温度系数):X7R;")
      (fields
        (field (name "Manufacturer Part") "GRM155R71H104KE14D")
        (field (name "Manufacturer") "muRata(村田)")
      )
      (libsource (lib "easyedapro") (part "GRM155R71H104KE14D"))
    )
    (comp (ref "C160")
      (value "4.7uF")
      (footprint "easyedapro:C1206")
      (description "容值:4.7uF;精度:±10%;额定电压:100V;材质(温度系数):X7S;")
      (fields
        (field (name "Manufacturer Part") "CM316X7S475K100AT")
        (field (name "Manufacturer") "Kyocera AVX")
      )
      (libsource (lib "easyedapro") (part "CM316X7S475K100AT"))
    )
    (comp (ref "C161")
      (value "4.7uF")
      (footprint "easyedapro:C1206")
      (description "容值:4.7uF;精度:±10%;额定电压:100V;材质(温度系数):X7S;")
      (fields
        (field (name "Manufacturer Part") "CM316X7S475K100AT")
        (field (name "Manufacturer") "Kyocera AVX")
      )
      (libsource (lib "easyedapro") (part "CM316X7S475K100AT"))
    )
    (comp (ref "C162")
      (value "330pF")
      (footprint "easyedapro:C0402")
      (description "容值:330pF;精度:±10%;额定电压:50V;材质(温度系数):X7R;")
      (fields (field (name "Manufacturer Part") "0402B331K500NT") (field (name "Manufacturer") "FH(风华)"))
      (libsource (lib "easyedapro") (part "0402B331K500NT"))
    )
    (comp (ref "C163")
      (value "33uF")
      (footprint "easyedapro:C1206")
      (description "容值:33uF;精度:±20%;额定电压:25V;材质(温度系数):X5R;")
      (fields (field (name "Manufacturer Part") "C3216X5R1E336MT000E") (field (name "Manufacturer") "TDK"))
      (libsource (lib "easyedapro") (part "C3216X5R1E336MT000E"))
    )
    (comp (ref "C164")
      (value "33uF")
      (footprint "easyedapro:C1206")
      (description "容值:33uF;精度:±20%;额定电压:25V;材质(温度系数):X5R;")
      (fields (field (name "Manufacturer Part") "C3216X5R1E336MT000E") (field (name "Manufacturer") "TDK"))
      (libsource (lib "easyedapro") (part "C3216X5R1E336MT000E"))
    )
    (comp (ref "C165")
      (value "100nF")
      (footprint "easyedapro:C0402")
      (description "容值:100nF;精度:±10%;额定电压:50V;材质(温度系数):X7R;")
      (fields
        (field (name "Manufacturer Part") "GRM155R71H104KE14D")
        (field (name "Manufacturer") "muRata(村田)")
      )
      (libsource (lib "easyedapro") (part "GRM155R71H104KE14D"))
    )
    (comp (ref "C166")
      (value "4.7uF")
      (footprint "easyedapro:C1206")
      (description "容值:4.7uF;精度:±10%;额定电压:100V;材质(温度系数):X7S;")
      (fields
        (field (name "Manufacturer Part") "CM316X7S475K100AT")
        (field (name "Manufacturer") "Kyocera AVX")
      )
      (libsource (lib "easyedapro") (part "CM316X7S475K100AT"))
    )
    (comp (ref "C167")
      (value "4.7uF")
      (footprint "easyedapro:C1206")
      (description "容值:4.7uF;精度:±10%;额定电压:100V;材质(温度系数):X7S;")
      (fields
        (field (name "Manufacturer Part") "CM316X7S475K100AT")
        (field (name "Manufacturer") "Kyocera AVX")
      )
      (libsource (lib "easyedapro") (part "CM316X7S475K100AT"))
    )
    (comp (ref "C168")
      (value "470pF")
      (footprint "easyedapro:C0402")
      (description "容值:330pF;精度:±10%;额定电压:50V;材质(温度系数):X7R;")
      (fields (field (name "Manufacturer Part") "0402B331K500NT") (field (name "Manufacturer") "FH(风华)"))
      (libsource (lib "easyedapro") (part "0402B331K500NT"))
    )
    (comp (ref "C169")
      (value "22uF")
      (footprint "easyedapro:C1206")
      (description "容值:33uF;精度:±20%;额定电压:25V;材质(温度系数):X5R;")
      (fields (field (name "Manufacturer Part") "C3216X5R1E336MT000E") (field (name "Manufacturer") "TDK"))
      (libsource (lib "easyedapro") (part "C3216X5R1E336MT000E"))
    )
    (comp (ref "C170")
      (value "22uF")
      (footprint "easyedapro:C1206")
      (description "容值:33uF;精度:±20%;额定电压:25V;材质(温度系数):X5R;")
      (fields (field (name "Manufacturer Part") "C3216X5R1E336MT000E") (field (name "Manufacturer") "TDK"))
      (libsource (lib "easyedapro") (part "C3216X5R1E336MT000E"))
    )
    (comp (ref "C171")
      (value "100nF")
      (footprint "easyedapro:C0402")
      (description "容值:100nF;精度:±10%;额定电压:50V;材质(温度系数):X7R;")
      (fields
        (field (name "Manufacturer Part") "GRM155R71H104KE14D")
        (field (name "Manufacturer") "muRata(村田)")
      )
      (libsource (lib "easyedapro") (part "GRM155R71H104KE14D"))
    )
    (comp (ref "D2")
      (value "SMAJ40A")
      (footprint "easyedapro:SMA_L4.4-W2.6-LS5.0-RD")
      (description "极性:单向;反向截止电压(Vrwm):33V;击穿电压:36.7V;反向漏电流(Ir):5uA;峰值脉冲电流(Ipp)@10/1000s:7.5A;最大钳位电压:53.3V;")
      (fields (field (name "Manufacturer") "FMS(美丽微)"))
      (libsource (lib "easyedapro") (part "SMAJ33A_C143131"))
    )
    (comp (ref "D5")
      (value "DSK34")
      (footprint "easyedapro:SOD-123_L2.8-W1.8-LS3.7-RD")
      (description "二极管配置:-;正向压降(Vf):550mV@3A;直流反向耐压(Vr):40V;平均整流电流(Io):3A;")
      (fields (field (name "Manufacturer") "FUXINSEMI(富芯森美)"))
      (libsource (lib "easyedapro") (part "DSK34_C908230"))
    )
    (comp (ref "D6")
      (value "SS310")
      (footprint "easyedapro:SMA_L4.3-W2.6-LS5.2-RD")
      (description "正向压降(Vf):850mV@3A;直流反向耐压(Vr):100V;平均整流电流(Io):3A;")
      (fields (field (name "Manufacturer") "MDD"))
      (libsource (lib "easyedapro") (part "SS310"))
    )
    (comp (ref "D7")
      (value "SS310")
      (footprint "easyedapro:SMA_L4.3-W2.6-LS5.2-RD")
      (description "正向压降(Vf):850mV@3A;直流反向耐压(Vr):100V;平均整流电流(Io):3A;")
      (fields (field (name "Manufacturer") "MDD"))
      (libsource (lib "easyedapro") (part "SS310"))
    )
    (comp (ref "L8")
      (value "15uH")
      (footprint "easyedapro:IND-SMD_L4.4-W4.2")
      (description "类型:一体成型电感;电感值:10uH;精度:±20%;额定电流:1.6A;饱和电流(Isat):2.2A;")
      (fields (field (name "Manufacturer Part") "FXL0420-100-M") (field (name "Manufacturer") "cjiang(长江微电)"))
      (libsource (lib "easyedapro") (part "FXL0420-100-M"))
    )
    (comp (ref "L9")
      (value "10uH")
      (footprint "easyedapro:IND-SMD_L4.4-W4.2")
      (description "类型:一体成型电感;电感值:10uH;精度:±20%;额定电流:1.6A;饱和电流(Isat):2.2A;")
      (fields (field (name "Manufacturer Part") "FXL0420-100-M") (field (name "Manufacturer") "cjiang(长江微电)"))
      (libsource (lib "easyedapro") (part "FXL0420-100-M"))
    )
    (comp (ref "R197")
      (value "2.2kΩ")
      (footprint "easyedapro:R0402")
      (description "电阻类型:厚膜电阻;阻值:2.2kΩ;精度:±1%;功率:62.5mW;最大工作电压:50V;温度系数:±100ppm/°C;")
      (fields
        (field (name "Manufacturer Part") "0402WGF2201TCE")
        (field (name "Manufacturer") "UNI-ROYAL(厚声)")
      )
      (libsource (lib "easyedapro") (part "0402WGF2201TCE"))
    )
    (comp (ref "R198")
      (value "10kΩ")
      (footprint "easyedapro:R0402")
      (description "电阻类型:厚膜电阻;阻值:10kΩ;精度:±1%;功率:62.5mW;最大工作电压:50V;温度系数:±100ppm/°C;")
      (fields (field (name "Manufacturer Part") "RC0402FR-0710KL") (field (name "Manufacturer") "YAGEO(国巨)"))
      (libsource (lib "easyedapro") (part "RC0402FR-0710KL"))
    )
    (comp (ref "R199")
      (value "10kΩ")
      (footprint "easyedapro:R0402")
      (description "电阻类型:厚膜电阻;阻值:10kΩ;精度:±1%;功率:62.5mW;最大工作电压:50V;温度系数:±100ppm/°C;")
      (fields (field (name "Manufacturer Part") "RC0402FR-0710KL") (field (name "Manufacturer") "YAGEO(国巨)"))
      (libsource (lib "easyedapro") (part "RC0402FR-0710KL"))
    )
    (comp (ref "R200")
      (value "2.2kΩ")
      (footprint "easyedapro:R0402")
      (description "电阻类型:厚膜电阻;阻值:2.2kΩ;精度:±1%;功率:62.5mW;最大工作电压:50V;温度系数:±100ppm/°C;")
      (fields
        (field (name "Manufacturer Part") "0402WGF2201TCE")
        (field (name "Manufacturer") "UNI-ROYAL(厚声)")
      )
      (libsource (lib "easyedapro") (part "0402WGF2201TCE"))
    )
    (comp (ref "R201")
      (value "10kΩ")
      (footprint "easyedapro:R0402")
      (description "电阻类型:厚膜电阻;阻值:10kΩ;精度:±1%;功率:62.5mW;最大工作电压:50V;温度系数:±100ppm/°C;")
      (fields (field (name "Manufacturer Part") "RC0402FR-0710KL") (field (name "Manufacturer") "YAGEO(国巨)"))
      (libsource (lib "easyedapro") (part "RC0402FR-0710KL"))
    )
    (comp (ref "R202")
      (value "10kΩ")
      (footprint "easyedapro:R0402")
      (description "电阻类型:厚膜电阻;阻值:10kΩ;精度:±1%;功率:62.5mW;最大工作电压:50V;温度系数:±100ppm/°C;")
      (fields (field (name "Manufacturer Part") "RC0402FR-0710KL") (field (name "Manufacturer") "YAGEO(国巨)"))
      (libsource (lib "easyedapro") (part "RC0402FR-0710KL"))
    )
    (comp (ref "R203")
      (value "17.4kΩ")
      (footprint "easyedapro:R0402")
      (description "电阻类型:厚膜电阻;阻值:17.4kΩ;精度:±1%;功率:62.5mW;最大工作电压:50V;温度系数:±100ppm/°C;")
      (fields
        (field (name "Manufacturer Part") "0402WGF1742TCE")
        (field (name "Manufacturer") "UNI-ROYAL(厚声)")
      )
      (libsource (lib "easyedapro") (part "0402WGF1742TCE"))
    )
    (comp (ref "R204")
      (value "100K")
      (footprint "easyedapro:R0402")
      (description "电阻类型:厚膜电阻;阻值:1MΩ;精度:±1%;功率:62.5mW;最大工作电压:50V;温度系数:±100ppm/°C;")
      (fields
        (field (name "Manufacturer Part") "0402WGF1004TCE")
        (field (name "Manufacturer") "UNI-ROYAL(厚声)")
      )
      (libsource (lib "easyedapro") (part "0402WGF1004TCE"))
    )
    (comp (ref "R206")
      (value "47.5kΩ")
      (footprint "easyedapro:R0402")
      (description "电阻类型:厚膜电阻;阻值:47.5kΩ;精度:±1%;功率:62.5mW;最大工作电压:50V;温度系数:±100ppm/°C;")
      (fields
        (field (name "Manufacturer Part") "0402WGF4752TCE")
        (field (name "Manufacturer") "UNI-ROYAL(厚声)")
      )
      (libsource (lib "easyedapro") (part "0402WGF4752TCE"))
    )
    (comp (ref "R207")
      (value "40.2kΩ")
      (footprint "easyedapro:R0402")
      (description "电阻类型:厚膜电阻;阻值:40.2kΩ;精度:±1%;功率:62.5mW;最大工作电压:50V;温度系数:±100ppm/°C;")
      (fields
        (field (name "Manufacturer Part") "0402WGF4022TCE")
        (field (name "Manufacturer") "UNI-ROYAL(厚声)")
      )
      (libsource (lib "easyedapro") (part "0402WGF4022TCE"))
    )
    (comp (ref "R209")
      (value "20Ω")
      (footprint "easyedapro:R0402")
      (description "电阻类型:厚膜电阻;阻值:20Ω;精度:±1%;功率:62.5mW;最大工作电压:50V;温度系数:±200ppm/°C;")
      (fields
        (field (name "Manufacturer Part") "0402WGF200JTCE")
        (field (name "Manufacturer") "UNI-ROYAL(厚声)")
      )
      (libsource (lib "easyedapro") (part "0402WGF200JTCE"))
    )
    (comp (ref "R210")
      (value "17.4kΩ")
      (footprint "easyedapro:R0402")
      (description "电阻类型:厚膜电阻;阻值:17.4kΩ;精度:±1%;功率:62.5mW;最大工作电压:50V;温度系数:±100ppm/°C;")
      (fields
        (field (name "Manufacturer Part") "0402WGF1742TCE")
        (field (name "Manufacturer") "UNI-ROYAL(厚声)")
      )
      (libsource (lib "easyedapro") (part "0402WGF1742TCE"))
    )
    (comp (ref "R211")
      (value "100K")
      (footprint "easyedapro:R0402")
      (description "电阻类型:厚膜电阻;阻值:1MΩ;精度:±1%;功率:62.5mW;最大工作电压:50V;温度系数:±100ppm/°C;")
      (fields
        (field (name "Manufacturer Part") "0402WGF1004TCE")
        (field (name "Manufacturer") "UNI-ROYAL(厚声)")
      )
      (libsource (lib "easyedapro") (part "0402WGF1004TCE"))
    )
    (comp (ref "R213")
      (value "16kΩ")
      (footprint "easyedapro:R0402")
      (description "电阻类型:厚膜电阻;阻值:47.5kΩ;精度:±1%;功率:62.5mW;最大工作电压:50V;温度系数:±100ppm/°C;")
      (fields
        (field (name "Manufacturer Part") "0402WGF4752TCE")
        (field (name "Manufacturer") "UNI-ROYAL(厚声)")
      )
      (libsource (lib "easyedapro") (part "0402WGF4752TCE"))
    )
    (comp (ref "R214")
      (value "40.2kΩ")
      (footprint "easyedapro:R0402")
      (description "电阻类型:厚膜电阻;阻值:40.2kΩ;精度:±1%;功率:62.5mW;最大工作电压:50V;温度系数:±100ppm/°C;")
      (fields
        (field (name "Manufacturer Part") "0402WGF4022TCE")
        (field (name "Manufacturer") "UNI-ROYAL(厚声)")
      )
      (libsource (lib "easyedapro") (part "0402WGF4022TCE"))
    )
    (comp (ref "R216")
      (value "20Ω")
      (footprint "easyedapro:R0402")
      (description "电阻类型:厚膜电阻;阻值:20Ω;精度:±1%;功率:62.5mW;最大工作电压:50V;温度系数:±200ppm/°C;")
      (fields
        (field (name "Manufacturer Part") "0402WGF200JTCE")
        (field (name "Manufacturer") "UNI-ROYAL(厚声)")
      )
      (libsource (lib "easyedapro") (part "0402WGF200JTCE"))
    )
    (comp (ref "R219")
      (value "560kΩ")
      (footprint "easyedapro:R0402")
      (description "电阻类型:厚膜电阻;阻值:560kΩ;精度:±1%;功率:62.5mW;最大工作电压:50V;温度系数:±100ppm/°C;")
      (fields (field (name "Manufacturer Part") "RC0402FR-07560KL") (field (name "Manufacturer") "YAGEO(国巨)"))
      (libsource (lib "easyedapro") (part "RC0402FR-07560KL"))
    )
    (comp (ref "R220")
      (value "220kΩ")
      (footprint "easyedapro:R0402")
      (description "电阻类型:厚膜电阻;阻值:220kΩ;精度:±1%;功率:62.5mW;最大工作电压:50V;温度系数:±100ppm/°C;")
      (fields
        (field (name "Manufacturer Part") "0402WGF2203TCE")
        (field (name "Manufacturer") "UNI-ROYAL(厚声)")
      )
      (libsource (lib "easyedapro") (part "0402WGF2203TCE"))
    )
    (comp (ref "R221")
      (value "200kΩ")
      (footprint "easyedapro:R0402")
      (description "电阻类型:厚膜电阻;阻值:200kΩ;精度:±1%;功率:62.5mW;最大工作电压:50V;温度系数:±100ppm/°C;")
      (fields
        (field (name "Manufacturer Part") "0402WGF2003TCE")
        (field (name "Manufacturer") "UNI-ROYAL(厚声)")
      )
      (libsource (lib "easyedapro") (part "0402WGF2003TCE"))
    )
    (comp (ref "R222")
      (value "200kΩ")
      (footprint "easyedapro:R0402")
      (description "电阻类型:厚膜电阻;阻值:200kΩ;精度:±1%;功率:62.5mW;最大工作电压:50V;温度系数:±100ppm/°C;")
      (fields
        (field (name "Manufacturer Part") "0402WGF2003TCE")
        (field (name "Manufacturer") "UNI-ROYAL(厚声)")
      )
      (libsource (lib "easyedapro") (part "0402WGF2003TCE"))
    )
    (comp (ref "U98")
      (value "LP5912-3.3DRVT")
      (footprint "easyedapro:WSON-6_L2.0-W2.0-P0.65-TL-EP")
      (description "输出类型:固定;最大输入电压:6.5V;输出电压:3.3V;最大输出电流:500mA;电源纹波抑制比(PSRR):40dB@(100kHz);输出极性:正极;")
      (fields (field (name "Manufacturer") "TI(德州仪器)"))
      (libsource (lib "easyedapro") (part "LP5912-3.3DRVT"))
    )
    (comp (ref "U204")
      (value "LP5912-3.3DRVT")
      (footprint "easyedapro:WSON-6_L2.0-W2.0-P0.65-TL-EP")
      (description "输出类型:固定;最大输入电压:6.5V;输出电压:3.3V;最大输出电流:500mA;电源纹波抑制比(PSRR):40dB@(100kHz);输出极性:正极;")
      (fields (field (name "Manufacturer") "TI(德州仪器)"))
      (libsource (lib "easyedapro") (part "LP5912-3.3DRVT"))
    )
    (comp (ref "U205") (value "~") (libsource (lib "easyedapro") (part "MP4560DQ")))
    (comp (ref "U206") (value "~") (libsource (lib "easyedapro") (part "MP4560DQ")))
    (comp (ref "R133")
      (value "100Ω")
      (footprint "easyedapro:R0402")
      (description "电阻类型:厚膜电阻;阻值:100Ω;精度:±1%;功率:62.5mW;最大工作电压:50V;温度系数:±200ppm/°C;")
      (fields
        (field (name "Manufacturer Part") "0402WGF1000TCE")
        (field (name "Manufacturer") "UNI-ROYAL(厚声)")
      )
      (libsource (lib "easyedapro") (part "0402WGF1000TCE"))
    )
    (comp (ref "R134")
      (value "100Ω")
      (footprint "easyedapro:R0402")
      (description "电阻类型:厚膜电阻;阻值:100Ω;精度:±1%;功率:62.5mW;最大工作电压:50V;温度系数:±200ppm/°C;")
      (fields
        (field (name "Manufacturer Part") "0402WGF1000TCE")
        (field (name "Manufacturer") "UNI-ROYAL(厚声)")
      )
      (libsource (lib "easyedapro") (part "0402WGF1000TCE"))
    )
    (comp (ref "R135")
      (value "100Ω")
      (footprint "easyedapro:R0402")
      (description "电阻类型:厚膜电阻;阻值:100Ω;精度:±1%;功率:62.5mW;最大工作电压:50V;温度系数:±200ppm/°C;")
      (fields
        (field (name "Manufacturer Part") "0402WGF1000TCE")
        (field (name "Manufacturer") "UNI-ROYAL(厚声)")
      )
      (libsource (lib "easyedapro") (part "0402WGF1000TCE"))
    )
    (comp (ref "R136")
      (value "100Ω")
      (footprint "easyedapro:R0402")
      (description "电阻类型:厚膜电阻;阻值:100Ω;精度:±1%;功率:62.5mW;最大工作电压:50V;温度系数:±200ppm/°C;")
      (fields
        (field (name "Manufacturer Part") "0402WGF1000TCE")
        (field (name "Manufacturer") "UNI-ROYAL(厚声)")
      )
      (libsource (lib "easyedapro") (part "0402WGF1000TCE"))
    )
    (comp (ref "R137")
      (value "100Ω")
      (footprint "easyedapro:R0402")
      (description "电阻类型:厚膜电阻;阻值:100Ω;精度:±1%;功率:62.5mW;最大工作电压:50V;温度系数:±200ppm/°C;")
      (fields
        (field (name "Manufacturer Part") "0402WGF1000TCE")
        (field (name "Manufacturer") "UNI-ROYAL(厚声)")
      )
      (libsource (lib "easyedapro") (part "0402WGF1000TCE"))
    )
    (comp (ref "R138")
      (value "100Ω")
      (footprint "easyedapro:R0402")
      (description "电阻类型:厚膜电阻;阻值:100Ω;精度:±1%;功率:62.5mW;最大工作电压:50V;温度系数:±200ppm/°C;")
      (fields
        (field (name "Manufacturer Part") "0402WGF1000TCE")
        (field (name "Manufacturer") "UNI-ROYAL(厚声)")
      )
      (libsource (lib "easyedapro") (part "0402WGF1000TCE"))
    )
    (comp (ref "R139")
      (value "100Ω")
      (footprint "easyedapro:R0402")
      (description "电阻类型:厚膜电阻;阻值:100Ω;精度:±1%;功率:62.5mW;最大工作电压:50V;温度系数:±200ppm/°C;")
      (fields
        (field (name "Manufacturer Part") "0402WGF1000TCE")
        (field (name "Manufacturer") "UNI-ROYAL(厚声)")
      )
      (libsource (lib "easyedapro") (part "0402WGF1000TCE"))
    )
    (comp (ref "R140")
      (value "100Ω")
      (footprint "easyedapro:R0402")
      (description "电阻类型:厚膜电阻;阻值:100Ω;精度:±1%;功率:62.5mW;最大工作电压:50V;温度系数:±200ppm/°C;")
      (fields
        (field (name "Manufacturer Part") "0402WGF1000TCE")
        (field (name "Manufacturer") "UNI-ROYAL(厚声)")
      )
      (libsource (lib "easyedapro") (part "0402WGF1000TCE"))
    )
    (comp (ref "R174")
      (value "100Ω")
      (footprint "easyedapro:R0402")
      (description "电阻类型:厚膜电阻;阻值:100Ω;精度:±1%;功率:62.5mW;最大工作电压:50V;温度系数:±200ppm/°C;")
      (fields
        (field (name "Manufacturer Part") "0402WGF1000TCE")
        (field (name "Manufacturer") "UNI-ROYAL(厚声)")
      )
      (libsource (lib "easyedapro") (part "0402WGF1000TCE"))
    )
    (comp (ref "R175")
      (value "100Ω")
      (footprint "easyedapro:R0402")
      (description "电阻类型:厚膜电阻;阻值:100Ω;精度:±1%;功率:62.5mW;最大工作电压:50V;温度系数:±200ppm/°C;")
      (fields
        (field (name "Manufacturer Part") "0402WGF1000TCE")
        (field (name "Manufacturer") "UNI-ROYAL(厚声)")
      )
      (libsource (lib "easyedapro") (part "0402WGF1000TCE"))
    )
    (comp (ref "R176")
      (value "100Ω")
      (footprint "easyedapro:R0402")
      (description "电阻类型:厚膜电阻;阻值:100Ω;精度:±1%;功率:62.5mW;最大工作电压:50V;温度系数:±200ppm/°C;")
      (fields
        (field (name "Manufacturer Part") "0402WGF1000TCE")
        (field (name "Manufacturer") "UNI-ROYAL(厚声)")
      )
      (libsource (lib "easyedapro") (part "0402WGF1000TCE"))
    )
    (comp (ref "R177")
      (value "100Ω")
      (footprint "easyedapro:R0402")
      (description "电阻类型:厚膜电阻;阻值:100Ω;精度:±1%;功率:62.5mW;最大工作电压:50V;温度系数:±200ppm/°C;")
      (fields
        (field (name "Manufacturer Part") "0402WGF1000TCE")
        (field (name "Manufacturer") "UNI-ROYAL(厚声)")
      )
      (libsource (lib "easyedapro") (part "0402WGF1000TCE"))
    )
    (comp (ref "R178")
      (value "100Ω")
      (footprint "easyedapro:R0402")
      (description "电阻类型:厚膜电阻;阻值:100Ω;精度:±1%;功率:62.5mW;最大工作电压:50V;温度系数:±200ppm/°C;")
      (fields
        (field (name "Manufacturer Part") "0402WGF1000TCE")
        (field (name "Manufacturer") "UNI-ROYAL(厚声)")
      )
      (libsource (lib "easyedapro") (part "0402WGF1000TCE"))
    )
    (comp (ref "R179")
      (value "100Ω")
      (footprint "easyedapro:R0402")
      (description "电阻类型:厚膜电阻;阻值:100Ω;精度:±1%;功率:62.5mW;最大工作电压:50V;温度系数:±200ppm/°C;")
      (fields
        (field (name "Manufacturer Part") "0402WGF1000TCE")
        (field (name "Manufacturer") "UNI-ROYAL(厚声)")
      )
      (libsource (lib "easyedapro") (part "0402WGF1000TCE"))
    )
    (comp (ref "R180")
      (value "100Ω")
      (footprint "easyedapro:R0402")
      (description "电阻类型:厚膜电阻;阻值:100Ω;精度:±1%;功率:62.5mW;最大工作电压:50V;温度系数:±200ppm/°C;")
      (fields
        (field (name "Manufacturer Part") "0402WGF1000TCE")
        (field (name "Manufacturer") "UNI-ROYAL(厚声)")
      )
      (libsource (lib "easyedapro") (part "0402WGF1000TCE"))
    )
    (comp (ref "R181")
      (value "100Ω")
      (footprint "easyedapro:R0402")
      (description "电阻类型:厚膜电阻;阻值:100Ω;精度:±1%;功率:62.5mW;最大工作电压:50V;温度系数:±200ppm/°C;")
      (fields
        (field (name "Manufacturer Part") "0402WGF1000TCE")
        (field (name "Manufacturer") "UNI-ROYAL(厚声)")
      )
      (libsource (lib "easyedapro") (part "0402WGF1000TCE"))
    )
    (comp (ref "R182")
      (value "100Ω")
      (footprint "easyedapro:R0402")
      (description "电阻类型:厚膜电阻;阻值:100Ω;精度:±1%;功率:62.5mW;最大工作电压:50V;温度系数:±200ppm/°C;")
      (fields
        (field (name "Manufacturer Part") "0402WGF1000TCE")
        (field (name "Manufacturer") "UNI-ROYAL(厚声)")
      )
      (libsource (lib "easyedapro") (part "0402WGF1000TCE"))
    )
    (comp (ref "R183")
      (value "100Ω")
      (footprint "easyedapro:R0402")
      (description "电阻类型:厚膜电阻;阻值:100Ω;精度:±1%;功率:62.5mW;最大工作电压:50V;温度系数:±200ppm/°C;")
      (fields
        (field (name "Manufacturer Part") "0402WGF1000TCE")
        (field (name "Manufacturer") "UNI-ROYAL(厚声)")
      )
      (libsource (lib "easyedapro") (part "0402WGF1000TCE"))
    )
    (comp (ref "R184")
      (value "4.7kΩ")
      (footprint "easyedapro:R0402")
      (description "电阻类型:厚膜电阻;阻值:4.7kΩ;精度:±1%;功率:62.5mW;最大工作电压:50V;温度系数:±100ppm/°C;")
      (fields
        (field (name "Manufacturer Part") "0402WGF4701TCE")
        (field (name "Manufacturer") "UNI-ROYAL(厚声)")
      )
      (libsource (lib "easyedapro") (part "0402WGF4701TCE"))
    )
    (comp (ref "R185")
      (value "4.7kΩ")
      (footprint "easyedapro:R0402")
      (description "电阻类型:厚膜电阻;阻值:4.7kΩ;精度:±1%;功率:62.5mW;最大工作电压:50V;温度系数:±100ppm/°C;")
      (fields
        (field (name "Manufacturer Part") "0402WGF4701TCE")
        (field (name "Manufacturer") "UNI-ROYAL(厚声)")
      )
      (libsource (lib "easyedapro") (part "0402WGF4701TCE"))
    )
    (comp (ref "R186")
      (value "100Ω")
      (footprint "easyedapro:R0402")
      (description "电阻类型:厚膜电阻;阻值:100Ω;精度:±1%;功率:62.5mW;最大工作电压:50V;温度系数:±200ppm/°C;")
      (fields
        (field (name "Manufacturer Part") "0402WGF1000TCE")
        (field (name "Manufacturer") "UNI-ROYAL(厚声)")
      )
      (libsource (lib "easyedapro") (part "0402WGF1000TCE"))
    )
    (comp (ref "R187")
      (value "100Ω")
      (footprint "easyedapro:R0402")
      (description "电阻类型:厚膜电阻;阻值:100Ω;精度:±1%;功率:62.5mW;最大工作电压:50V;温度系数:±200ppm/°C;")
      (fields
        (field (name "Manufacturer Part") "0402WGF1000TCE")
        (field (name "Manufacturer") "UNI-ROYAL(厚声)")
      )
      (libsource (lib "easyedapro") (part "0402WGF1000TCE"))
    )
    (comp (ref "R188")
      (value "100Ω")
      (footprint "easyedapro:R0402")
      (description "电阻类型:厚膜电阻;阻值:100Ω;精度:±1%;功率:62.5mW;最大工作电压:50V;温度系数:±200ppm/°C;")
      (fields
        (field (name "Manufacturer Part") "0402WGF1000TCE")
        (field (name "Manufacturer") "UNI-ROYAL(厚声)")
      )
      (libsource (lib "easyedapro") (part "0402WGF1000TCE"))
    )
    (comp (ref "R189")
      (value "100Ω")
      (footprint "easyedapro:R0402")
      (description "电阻类型:厚膜电阻;阻值:100Ω;精度:±1%;功率:62.5mW;最大工作电压:50V;温度系数:±200ppm/°C;")
      (fields
        (field (name "Manufacturer Part") "0402WGF1000TCE")
        (field (name "Manufacturer") "UNI-ROYAL(厚声)")
      )
      (libsource (lib "easyedapro") (part "0402WGF1000TCE"))
    )
    (comp (ref "R190")
      (value "4.7kΩ")
      (footprint "easyedapro:R0402")
      (description "电阻类型:厚膜电阻;阻值:4.7kΩ;精度:±1%;功率:62.5mW;最大工作电压:50V;温度系数:±100ppm/°C;")
      (fields
        (field (name "Manufacturer Part") "0402WGF4701TCE")
        (field (name "Manufacturer") "UNI-ROYAL(厚声)")
      )
      (libsource (lib "easyedapro") (part "0402WGF4701TCE"))
    )
    (comp (ref "R191")
      (value "4.7kΩ")
      (footprint "easyedapro:R0402")
      (description "电阻类型:厚膜电阻;阻值:4.7kΩ;精度:±1%;功率:62.5mW;最大工作电压:50V;温度系数:±100ppm/°C;")
      (fields
        (field (name "Manufacturer Part") "0402WGF4701TCE")
        (field (name "Manufacturer") "UNI-ROYAL(厚声)")
      )
      (libsource (lib "easyedapro") (part "0402WGF4701TCE"))
    )
    (comp (ref "R192")
      (value "100Ω")
      (footprint "easyedapro:R0402")
      (description "电阻类型:厚膜电阻;阻值:100Ω;精度:±1%;功率:62.5mW;最大工作电压:50V;温度系数:±200ppm/°C;")
      (fields
        (field (name "Manufacturer Part") "0402WGF1000TCE")
        (field (name "Manufacturer") "UNI-ROYAL(厚声)")
      )
      (libsource (lib "easyedapro") (part "0402WGF1000TCE"))
    )
    (comp (ref "R193")
      (value "100Ω")
      (footprint "easyedapro:R0402")
      (description "电阻类型:厚膜电阻;阻值:100Ω;精度:±1%;功率:62.5mW;最大工作电压:50V;温度系数:±200ppm/°C;")
      (fields
        (field (name "Manufacturer Part") "0402WGF1000TCE")
        (field (name "Manufacturer") "UNI-ROYAL(厚声)")
      )
      (libsource (lib "easyedapro") (part "0402WGF1000TCE"))
    )
    (comp (ref "R194")
      (value "100Ω")
      (footprint "easyedapro:R0402")
      (description "电阻类型:厚膜电阻;阻值:100Ω;精度:±1%;功率:62.5mW;最大工作电压:50V;温度系数:±200ppm/°C;")
      (fields
        (field (name "Manufacturer Part") "0402WGF1000TCE")
        (field (name "Manufacturer") "UNI-ROYAL(厚声)")
      )
      (libsource (lib "easyedapro") (part "0402WGF1000TCE"))
    )
    (comp (ref "R195")
      (value "100Ω")
      (footprint "easyedapro:R0402")
      (description "电阻类型:厚膜电阻;阻值:100Ω;精度:±1%;功率:62.5mW;最大工作电压:50V;温度系数:±200ppm/°C;")
      (fields
        (field (name "Manufacturer Part") "0402WGF1000TCE")
        (field (name "Manufacturer") "UNI-ROYAL(厚声)")
      )
      (libsource (lib "easyedapro") (part "0402WGF1000TCE"))
    )
    (comp (ref "R223")
      (value "4.7kΩ")
      (footprint "easyedapro:R0402")
      (description "电阻类型:厚膜电阻;阻值:4.7kΩ;精度:±1%;功率:62.5mW;最大工作电压:50V;温度系数:±100ppm/°C;")
      (fields
        (field (name "Manufacturer Part") "0402WGF4701TCE")
        (field (name "Manufacturer") "UNI-ROYAL(厚声)")
      )
      (libsource (lib "easyedapro") (part "0402WGF4701TCE"))
    )
    (comp (ref "R224")
      (value "4.7kΩ")
      (footprint "easyedapro:R0402")
      (description "电阻类型:厚膜电阻;阻值:4.7kΩ;精度:±1%;功率:62.5mW;最大工作电压:50V;温度系数:±100ppm/°C;")
      (fields
        (field (name "Manufacturer Part") "0402WGF4701TCE")
        (field (name "Manufacturer") "UNI-ROYAL(厚声)")
      )
      (libsource (lib "easyedapro") (part "0402WGF4701TCE"))
    )
    (comp (ref "R225")
      (value "100Ω")
      (footprint "easyedapro:R0402")
      (description "电阻类型:厚膜电阻;阻值:100Ω;精度:±1%;功率:62.5mW;最大工作电压:50V;温度系数:±200ppm/°C;")
      (fields
        (field (name "Manufacturer Part") "0402WGF1000TCE")
        (field (name "Manufacturer") "UNI-ROYAL(厚声)")
      )
      (libsource (lib "easyedapro") (part "0402WGF1000TCE"))
    )
    (comp (ref "R226")
      (value "100Ω")
      (footprint "easyedapro:R0402")
      (description "电阻类型:厚膜电阻;阻值:100Ω;精度:±1%;功率:62.5mW;最大工作电压:50V;温度系数:±200ppm/°C;")
      (fields
        (field (name "Manufacturer Part") "0402WGF1000TCE")
        (field (name "Manufacturer") "UNI-ROYAL(厚声)")
      )
      (libsource (lib "easyedapro") (part "0402WGF1000TCE"))
    )
    (comp (ref "U60")
      (value "ZX-SH1.0-6PWT")
      (footprint "easyedapro:CONN-SMD_6P-P1.00_MEGASTAR_ZX-SH1.0-6PWT")
      (fields (field (name "Manufacturer") "Megastar(兆星)"))
      (libsource (lib "easyedapro") (part "ZX-SH1.0-6PWT"))
    )
    (comp (ref "U70")
      (value "ZX-SH1.0-8PWT")
      (footprint "easyedapro:CONN-SMD_8P-P1.00_MEGASTAR_ZX-SH1.0-8PWT")
      (fields (field (name "Manufacturer") "Megastar(兆星)"))
      (libsource (lib "easyedapro") (part "ZX-SH1.0-8PWT"))
    )
    (comp (ref "U71")
      (value "BX-GH1.25-4PWT")
      (footprint "easyedapro:CONN-SMD_4P-P1.25_BX-GH1.25-4PWT")
      (fields (field (name "Manufacturer") "Bossie(博锡)"))
      (libsource (lib "easyedapro") (part "BX-GH1.25-4PWT"))
    )
    (comp (ref "U106") (value "~") (libsource (lib "easyedapro") (part "焊盘原件")))
    (comp (ref "U114") (value "~") (libsource (lib "easyedapro") (part "焊盘原件")))
    (comp (ref "U115") (value "~") (libsource (lib "easyedapro") (part "焊盘原件")))
    (comp (ref "U116") (value "~") (libsource (lib "easyedapro") (part "焊盘原件")))
    (comp (ref "U117") (value "~") (libsource (lib "easyedapro") (part "焊盘原件")))
    (comp (ref "U118") (value "~") (libsource (lib "easyedapro") (part "焊盘原件")))
    (comp (ref "U119")
      (value "ZX-GH1.25-WT6")
      (footprint "easyedapro:CONN-SMD_6P-P1.25_ZX-GH1.25-WT6")
      (fields (field (name "Manufacturer") "Megastar(兆星)"))
      (libsource (lib "easyedapro") (part "ZX-GH1.25-WT6"))
    )
    (comp (ref "U120")
      (value "ZX-GH1.25-WT6")
      (footprint "easyedapro:CONN-SMD_6P-P1.25_ZX-GH1.25-WT6")
      (fields (field (name "Manufacturer") "Megastar(兆星)"))
      (libsource (lib "easyedapro") (part "ZX-GH1.25-WT6"))
    )
    (comp (ref "U121") (value "~") (libsource (lib "easyedapro") (part "焊盘原件")))
    (comp (ref "U122") (value "~") (libsource (lib "easyedapro") (part "焊盘原件")))
    (comp (ref "U123") (value "~") (libsource (lib "easyedapro") (part "焊盘原件")))
    (comp (ref "U124") (value "~") (libsource (lib "easyedapro") (part "焊盘原件")))
    (comp (ref "U125")
      (value "ZX-GH1.25-WT6")
      (footprint "easyedapro:CONN-SMD_6P-P1.25_ZX-GH1.25-WT6")
      (fields (field (name "Manufacturer") "Megastar(兆星)"))
      (libsource (lib "easyedapro") (part "ZX-GH1.25-WT6"))
    )
    (comp (ref "U126")
      (value "ZX-GH1.25-WT6")
      (footprint "easyedapro:CONN-SMD_6P-P1.25_ZX-GH1.25-WT6")
      (fields (field (name "Manufacturer") "Megastar(兆星)"))
      (libsource (lib "easyedapro") (part "ZX-GH1.25-WT6"))
    )
    (comp (ref "U127") (value "~") (libsource (lib "easyedapro") (part "焊盘原件")))
    (comp (ref "U128") (value "~") (libsource (lib "easyedapro") (part "焊盘原件")))
    (comp (ref "U129") (value "~") (libsource (lib "easyedapro") (part "焊盘原件")))
    (comp (ref "U130") (value "~") (libsource (lib "easyedapro") (part "焊盘原件")))
    (comp (ref "U131") (value "~") (libsource (lib "easyedapro") (part "焊盘原件")))
    (comp (ref "U132") (value "~") (libsource (lib "easyedapro") (part "焊盘原件")))
    (comp (ref "U133") (value "~") (libsource (lib "easyedapro") (part "焊盘原件")))
    (comp (ref "U134") (value "~") (libsource (lib "easyedapro") (part "焊盘原件")))
    (comp (ref "U135") (value "~") (libsource (lib "easyedapro") (part "焊盘原件")))
    (comp (ref "U136") (value "~") (libsource (lib "easyedapro") (part "焊盘原件")))
    (comp (ref "U137") (value "~") (libsource (lib "easyedapro") (part "焊盘原件")))
    (comp (ref "U138") (value "~") (libsource (lib "easyedapro") (part "焊盘原件")))
    (comp (ref "U139") (value "~") (libsource (lib "easyedapro") (part "焊盘原件")))
    (comp (ref "U140") (value "~") (libsource (lib "easyedapro") (part "焊盘原件")))
    (comp (ref "U141") (value "~") (libsource (lib "easyedapro") (part "焊盘原件")))
    (comp (ref "U142") (value "~") (libsource (lib "easyedapro") (part "焊盘原件")))
    (comp (ref "U143") (value "~") (libsource (lib "easyedapro") (part "焊盘原件")))
    (comp (ref "U144") (value "~") (libsource (lib "easyedapro") (part "焊盘原件")))
    (comp (ref "U145") (value "~") (libsource (lib "easyedapro") (part "焊盘原件")))
    (comp (ref "U146") (value "~") (libsource (lib "easyedapro") (part "焊盘原件")))
    (comp (ref "U147") (value "~") (libsource (lib "easyedapro") (part "焊盘原件")))
    (comp (ref "U148") (value "~") (libsource (lib "easyedapro") (part "焊盘原件")))
    (comp (ref "U149") (value "~") (libsource (lib "easyedapro") (part "焊盘原件")))
    (comp (ref "U150") (value "~") (libsource (lib "easyedapro") (part "焊盘原件")))
    (comp (ref "U151") (value "~") (libsource (lib "easyedapro") (part "焊盘原件")))
    (comp (ref "U152") (value "~") (libsource (lib "easyedapro") (part "焊盘原件")))
    (comp (ref "U153") (value "~") (libsource (lib "easyedapro") (part "焊盘原件")))
    (comp (ref "U154") (value "~") (libsource (lib "easyedapro") (part "焊盘原件")))
    (comp (ref "U155") (value "~") (libsource (lib "easyedapro") (part "焊盘原件")))
    (comp (ref "U156") (value "~") (libsource (lib "easyedapro") (part "焊盘原件")))
    (comp (ref "U157") (value "~") (libsource (lib "easyedapro") (part "焊盘原件")))
    (comp (ref "U158") (value "~") (libsource (lib "easyedapro") (part "焊盘原件")))
    (comp (ref "U159") (value "~") (libsource (lib "easyedapro") (part "焊盘原件")))
    (comp (ref "U160") (value "~") (libsource (lib "easyedapro") (part "焊盘原件")))
    (comp (ref "U161") (value "~") (libsource (lib "easyedapro") (part "焊盘原件")))
    (comp (ref "U162") (value "~") (libsource (lib "easyedapro") (part "焊盘原件")))
    (comp (ref "U163") (value "~") (libsource (lib "easyedapro") (part "焊盘原件")))
    (comp (ref "U164") (value "~") (libsource (lib "easyedapro") (part "焊盘原件")))
    (comp (ref "U165") (value "~") (libsource (lib "easyedapro") (part "焊盘原件")))
    (comp (ref "U166") (value "~") (libsource (lib "easyedapro") (part "焊盘原件")))
    (comp (ref "U167") (value "~") (libsource (lib "easyedapro") (part "焊盘原件")))
    (comp (ref "U168") (value "~") (libsource (lib "easyedapro") (part "焊盘原件")))
    (comp (ref "U169") (value "~") (libsource (lib "easyedapro") (part "焊盘原件")))
    (comp (ref "U170") (value "~") (libsource (lib "easyedapro") (part "焊盘原件")))
    (comp (ref "U171") (value "~") (libsource (lib "easyedapro") (part "焊盘原件")))
    (comp (ref "U172") (value "~") (libsource (lib "easyedapro") (part "焊盘原件")))
    (comp (ref "U173") (value "~") (libsource (lib "easyedapro") (part "焊盘原件")))
    (comp (ref "U174") (value "~") (libsource (lib "easyedapro") (part "焊盘原件")))
    (comp (ref "U175") (value "~") (libsource (lib "easyedapro") (part "焊盘原件")))
    (comp (ref "U176") (value "~") (libsource (lib "easyedapro") (part "焊盘原件")))
    (comp (ref "U177") (value "~") (libsource (lib "easyedapro") (part "焊盘原件")))
    (comp (ref "U178") (value "~") (libsource (lib "easyedapro") (part "焊盘原件")))
    (comp (ref "U179") (value "~") (libsource (lib "easyedapro") (part "焊盘原件")))
    (comp (ref "U180") (value "~") (libsource (lib "easyedapro") (part "焊盘原件")))
    (comp (ref "U181") (value "~") (libsource (lib "easyedapro") (part "焊盘原件")))
    (comp (ref "U182") (value "~") (libsource (lib "easyedapro") (part "焊盘原件")))
    (comp (ref "U183") (value "~") (libsource (lib "easyedapro") (part "焊盘原件")))
    (comp (ref "U184") (value "~") (libsource (lib "easyedapro") (part "焊盘原件")))
    (comp (ref "U185") (value "~") (libsource (lib "easyedapro") (part "焊盘原件")))
    (comp (ref "U186") (value "~") (libsource (lib "easyedapro") (part "焊盘原件")))
    (comp (ref "U187") (value "~") (libsource (lib "easyedapro") (part "焊盘原件")))
    (comp (ref "U188") (value "~") (libsource (lib "easyedapro") (part "焊盘原件")))
    (comp (ref "U189") (value "~") (libsource (lib "easyedapro") (part "焊盘原件")))
    (comp (ref "U190") (value "~") (libsource (lib "easyedapro") (part "焊盘原件")))
    (comp (ref "U191") (value "~") (libsource (lib "easyedapro") (part "焊盘原件")))
    (comp (ref "U192") (value "~") (libsource (lib "easyedapro") (part "焊盘原件")))
    (comp (ref "U193") (value "~") (libsource (lib "easyedapro") (part "焊盘原件")))
    (comp (ref "U194") (value "~") (libsource (lib "easyedapro") (part "焊盘原件")))
    (comp (ref "U195") (value "~") (libsource (lib "easyedapro") (part "焊盘原件")))
    (comp (ref "U196") (value "~") (libsource (lib "easyedapro") (part "焊盘原件")))
    (comp (ref "U197") (value "~") (libsource (lib "easyedapro") (part "焊盘原件")))
    (comp (ref "U198") (value "~") (libsource (lib "easyedapro") (part "焊盘原件")))
    (comp (ref "U199") (value "~") (libsource (lib "easyedapro") (part "焊盘原件")))
    (comp (ref "U200") (value "~") (libsource (lib "easyedapro") (part "焊盘原件")))
    (comp (ref "U201") (value "~") (libsource (lib "easyedapro") (part "焊盘原件")))
    (comp (ref "U202") (value "~") (libsource (lib "easyedapro") (part "焊盘原件")))
    (comp (ref "U203") (value "~") (libsource (lib "easyedapro") (part "焊盘原件")))
  )
  (nets
    (net (code "1") (name "3V3_ADC") (class "Default")
      (node (ref "U160") (pin "1") (pinfunction "1_1") (pintype "input"))
      (node (ref "U65") (pin "H4") (pinfunction "PC5_H4") (pintype "input"))
    )
    (net (code "2") (name "3V3_IMU") (class "Default")
      (node (ref "C114") (pin "2") (pinfunction "2_2") (pintype "unspecified"))
      (node (ref "C115") (pin "2") (pinfunction "2_2") (pintype "unspecified"))
      (node (ref "C135") (pin "2") (pinfunction "2_2") (pintype "input"))
      (node (ref "C136") (pin "2") (pinfunction "2_2") (pintype "unspecified"))
      (node (ref "C137") (pin "2") (pinfunction "2_2") (pintype "unspecified"))
      (node (ref "C138") (pin "2") (pinfunction "2_2") (pintype "unspecified"))
      (node (ref "C157") (pin "2") (pinfunction "2_2") (pintype "unspecified"))
      (node (ref "C158") (pin "1") (pinfunction "1_1") (pintype "input"))
      (node (ref "C159") (pin "2") (pinfunction "2_2") (pintype "unspecified"))
      (node (ref "C32") (pin "2") (pinfunction "2_2") (pintype "input"))
      (node (ref "L3") (pin "2") (pinfunction "2_2") (pintype "input"))
      (node (ref "R173") (pin "2") (pinfunction "2_2") (pintype "input"))
      (node (ref "R202") (pin "2") (pinfunction "2_2") (pintype "input"))
      (node (ref "R227") (pin "2") (pinfunction "2_2") (pintype "input"))
      (node (ref "U204") (pin "1") (pinfunction "OUT_1") (pintype "input"))
      (node (ref "U30") (pin "5") (pinfunction "VDDIO_5") (pintype "unspecified"))
      (node (ref "U30") (pin "8") (pinfunction "VDD_8") (pintype "unspecified"))
      (node (ref "U58") (pin "5") (pinfunction "VDDIO_5") (pintype "unspecified"))
      (node (ref "U58") (pin "8") (pinfunction "VDD_8") (pintype "unspecified"))
      (node (ref "U59") (pin "1") (pinfunction "VDD_1") (pintype "unspecified"))
    )
    (net (code "3") (name "AWG3V3") (class "Default")
      (node (ref "C118") (pin "2") (pinfunction "2_2") (pintype "unspecified"))
      (node (ref "C119") (pin "2") (pinfunction "2_2") (pintype "unspecified"))
      (node (ref "L3") (pin "1") (pinfunction "1_1") (pintype "input"))
      (node (ref "R126") (pin "2") (pinfunction "2_2") (pintype "input"))
      (node (ref "R76") (pin "2") (pinfunction "2_2") (pintype "input"))
      (node (ref "R88") (pin "2") (pinfunction "2_2") (pintype "input"))
      (node (ref "U37") (pin "13") (pinfunction "DVDD_13") (pintype "unspecified"))
      (node (ref "U37") (pin "2") (pinfunction "AVDD_2") (pintype "unspecified"))
    )
    (net (code "4") (name "BEC_5V") (class "Default")
      (node (ref "C163") (pin "2") (pinfunction "2_2") (pintype "unspecified"))
      (node (ref "C164") (pin "2") (pinfunction "2_2") (pintype "unspecified"))
      (node (ref "D5") (pin "2") (pinfunction "A_2") (pintype "unspecified"))
      (node (ref "L8") (pin "2") (pinfunction "2_2") (pintype "input"))
      (node (ref "R220") (pin "2") (pinfunction "2_2") (pintype "input"))
    )
    (net (code "5") (name "BEC_12V") (class "Default")
      (node (ref "C169") (pin "2") (pinfunction "2_2") (pintype "unspecified"))
      (node (ref "C170") (pin "2") (pinfunction "2_2") (pintype "unspecified"))
      (node (ref "L9") (pin "2") (pinfunction "2_2") (pintype "input"))
      (node (ref "R219") (pin "2") (pinfunction "2_2") (pintype "input"))
      (node (ref "U157") (pin "1") (pinfunction "1_1") (pintype "input"))
      (node (ref "U195") (pin "1") (pinfunction "1_1") (pintype "input"))
    )
    (net (code "6") (name "BOOT0") (class "Default")
      (node (ref "R108") (pin "2") (pinfunction "2_2") (pintype "input"))
      (node (ref "SW3") (pin "3") (pinfunction "3_3") (pintype "unspecified"))
      (node (ref "SW3") (pin "4") (pinfunction "4_4") (pintype "unspecified"))
      (node (ref "U65") (pin "D5") (pinfunction "BOOT0_D5") (pintype "input"))
    )
    (net (code "7") (name "BUERZZ") (class "Default")
      (node (ref "R228") (pin "1") (pinfunction "1_1") (pintype "input"))
      (node (ref "U65") (pin "H8") (pinfunction "PD14_H8") (pintype "input"))
    )
    (net (code "8") (name "BZ") (class "Default")
      (node (ref "Q4") (pin "3") (pinfunction "C_3") (pintype "input"))
      (node (ref "U184") (pin "1") (pinfunction "1_1") (pintype "input"))
    )
    (net (code "9") (name "CAD1") (class "Default")
      (node (ref "R126") (pin "1") (pinfunction "1_1") (pintype "input"))
      (node (ref "U37") (pin "6") (pinfunction "CAD1_6") (pintype "unspecified"))
    )
    (net (code "10") (name "CAM") (class "Default")
      (node (ref "C120") (pin "1") (pinfunction "1_1") (pintype "unspecified"))
      (node (ref "R129") (pin "2") (pinfunction "2_2") (pintype "input"))
      (node (ref "U158") (pin "1") (pinfunction "1_1") (pintype "input"))
    )
    (net (code "11") (name "CAN1_H") (class "Default")
      (node (ref "R56") (pin "2") (pinfunction "2_2") (pintype "input"))
      (node (ref "U38") (pin "7") (pinfunction "CANH_7") (pintype "input"))
      (node (ref "U71") (pin "3") (pinfunction "3_3") (pintype "unspecified"))
    )
    (net (code "12") (name "CAN1_L") (class "Default")
      (node (ref "R56") (pin "1") (pinfunction "1_1") (pintype "input"))
      (node (ref "U38") (pin "6") (pinfunction "CANL_6") (pintype "input"))
      (node (ref "U71") (pin "2") (pinfunction "2_2") (pintype "unspecified"))
    )
    (net (code "13") (name "CAN1_RX") (class "Default")
      (node (ref "U38") (pin "4") (pinfunction "RXD_4") (pintype "input"))
      (node (ref "U65") (pin "D8") (pinfunction "PD0_D8") (pintype "input"))
    )
    (net (code "14") (name "CAN1_TX") (class "Default")
      (node (ref "U38") (pin "1") (pinfunction "TXD_1") (pintype "input"))
      (node (ref "U65") (pin "A4") (pinfunction "PB9_A4") (pintype "input"))
    )
    (net (code "15") (name "CAN2_H") (class "Default")
      (node (ref "R172") (pin "2") (pinfunction "2_2") (pintype "input"))
      (node (ref "U127") (pin "1") (pinfunction "1_1") (pintype "input"))
      (node (ref "U67") (pin "7") (pinfunction "CANH_7") (pintype "input"))
    )
    (net (code "16") (name "CAN2_L") (class "Default")
      (node (ref "R172") (pin "1") (pinfunction "1_1") (pintype "input"))
      (node (ref "U130") (pin "1") (pinfunction "1_1") (pintype "input"))
      (node (ref "U67") (pin "6") (pinfunction "CANL_6") (pintype "input"))
    )
    (net (code "17") (name "CAN2_RX") (class "Default")
      (node (ref "U65") (pin "C5") (pinfunction "PB5_C5") (pintype "input"))
      (node (ref "U67") (pin "4") (pinfunction "RXD_4") (pintype "input"))
    )
    (net (code "18") (name "CAN2_TX") (class "Default")
      (node (ref "U65") (pin "J8") (pinfunction "PB13_J8") (pintype "input"))
      (node (ref "U67") (pin "1") (pinfunction "TXD_1") (pintype "input"))
    )
    (net (code "19") (name "CC1") (class "Default")
      (node (ref "R99") (pin "2") (pinfunction "2_2") (pintype "input"))
      (node (ref "USB1") (pin "A5") (pinfunction "CC1_A5") (pintype "input"))
    )
    (net (code "20") (name "CC2") (class "Default")
      (node (ref "R100") (pin "2") (pinfunction "2_2") (pintype "input"))
      (node (ref "USB1") (pin "B5") (pinfunction "CC2_B5") (pintype "input"))
    )
    (net (code "21") (name "CURR_ADC") (class "Default")
      (node (ref "U65") (pin "F2") (pinfunction "PC1_F2") (pintype "input"))
      (node (ref "U70") (pin "8") (pinfunction "8_8") (pintype "unspecified"))
    )
    (net (code "22") (name "D+") (class "Default")
      (node (ref "R101") (pin "1") (pinfunction "1_1") (pintype "input"))
      (node (ref "USB1") (pin "A6") (pinfunction "DP1_A6") (pintype "input"))
      (node (ref "USB1") (pin "B6") (pinfunction "DP2_B6") (pintype "input"))
    )
    (net (code "23") (name "D-") (class "Default")
      (node (ref "R102") (pin "1") (pinfunction "1_1") (pintype "input"))
      (node (ref "USB1") (pin "A7") (pinfunction "DN1_A7") (pintype "input"))
      (node (ref "USB1") (pin "B7") (pinfunction "DN2_B7") (pintype "input"))
    )
    (net (code "24") (name "GND") (class "Default")
      (node (ref "C102") (pin "2") (pinfunction "2_2") (pintype "input"))
      (node (ref "C114") (pin "1") (pinfunction "1_1") (pintype "unspecified"))
      (node (ref "C115") (pin "1") (pinfunction "1_1") (pintype "unspecified"))
      (node (ref "C117") (pin "1") (pinfunction "1_1") (pintype "unspecified"))
      (node (ref "C118") (pin "1") (pinfunction "1_1") (pintype "unspecified"))
      (node (ref "C119") (pin "1") (pinfunction "1_1") (pintype "unspecified"))
      (node (ref "C121") (pin "2") (pinfunction "2_2") (pintype "unspecified"))
      (node (ref "C122") (pin "2") (pinfunction "2_2") (pintype "unspecified"))
      (node (ref "C123") (pin "2") (pinfunction "2_2") (pintype "unspecified"))
      (node (ref "C135") (pin "1") (pinfunction "1_1") (pintype "input"))
      (node (ref "C136") (pin "1") (pinfunction "1_1") (pintype "unspecified"))
      (node (ref "C137") (pin "1") (pinfunction "1_1") (pintype "unspecified"))
      (node (ref "C138") (pin "1") (pinfunction "1_1") (pintype "unspecified"))
      (node (ref "C146") (pin "1") (pinfunction "1_1") (pintype "unspecified"))
      (node (ref "C147") (pin "1") (pinfunction "1_1") (pintype "unspecified"))
      (node (ref "C150") (pin "2") (pinfunction "2_2") (pintype "input"))
      (node (ref "C151") (pin "1") (pinfunction "1_1") (pintype "unspecified"))
      (node (ref "C152") (pin "2") (pinfunction "2_2") (pintype "input"))
      (node (ref "C153") (pin "1") (pinfunction "1_1") (pintype "unspecified"))
      (node (ref "C154") (pin "1") (pinfunction "1_1") (pintype "unspecified"))
      (node (ref "C155") (pin "1") (pinfunction "1_1") (pintype "unspecified"))
      (node (ref "C156") (pin "2") (pinfunction "2_2") (pintype "input"))
      (node (ref "C157") (pin "1") (pinfunction "1_1") (pintype "unspecified"))
      (node (ref "C158") (pin "2") (pinfunction "2_2") (pintype "input"))
      (node (ref "C159") (pin "1") (pinfunction "1_1") (pintype "unspecified"))
      (node (ref "C160") (pin "1") (pinfunction "1_1") (pintype "input"))
      (node (ref "C161") (pin "1") (pinfunction "1_1") (pintype "input"))
      (node (ref "C163") (pin "1") (pinfunction "1_1") (pintype "unspecified"))
      (node (ref "C164") (pin "1") (pinfunction "1_1") (pintype "unspecified"))
      (node (ref "C166") (pin "1") (pinfunction "1_1") (pintype "input"))
      (node (ref "C167") (pin "1") (pinfunction "1_1") (pintype "input"))
      (node (ref "C169") (pin "1") (pinfunction "1_1") (pintype "unspecified"))
      (node (ref "C170") (pin "1") (pinfunction "1_1") (pintype "unspecified"))
      (node (ref "C22") (pin "1") (pinfunction "1_1") (pintype "unspecified"))
      (node (ref "C23") (pin "1") (pinfunction "1_1") (pintype "unspecified"))
      (node (ref "C24") (pin "1") (pinfunction "1_1") (pintype "unspecified"))
      (node (ref "C25") (pin "1") (pinfunction "1_1") (pintype "unspecified"))
      (node (ref "C26") (pin "1") (pinfunction "1_1") (pintype "unspecified"))
      (node (ref "C27") (pin "1") (pinfunction "1_1") (pintype "unspecified"))
      (node (ref "C32") (pin "1") (pinfunction "1_1") (pintype "input"))
      (node (ref "C82") (pin "1") (pinfunction "1_1") (pintype "input"))
      (node (ref "C83") (pin "1") (pinfunction "1_1") (pintype "unspecified"))
      (node (ref "C84") (pin "2") (pinfunction "2_2") (pintype "input"))
      (node (ref "C85") (pin "1") (pinfunction "1_1") (pintype "input"))
      (node (ref "C89") (pin "1") (pinfunction "1_1") (pintype "unspecified"))
      (node (ref "C90") (pin "1") (pinfunction "1_1") (pintype "unspecified"))
      (node (ref "CARD4") (pin "10") (pinfunction "10_10") (pintype "input"))
      (node (ref "CARD4") (pin "11") (pinfunction "EH_11") (pintype "input"))
      (node (ref "CARD4") (pin "6") (pinfunction "VSS_6") (pintype "input"))
      (node (ref "CARD4") (pin "9") (pinfunction "9_9") (pintype "input"))
      (node (ref "D2") (pin "2") (pinfunction "A_2") (pintype "input"))
      (node (ref "D6") (pin "2") (pinfunction "A_2") (pintype "unspecified"))
      (node (ref "D7") (pin "2") (pinfunction "A_2") (pintype "unspecified"))
      (node (ref "LED6") (pin "1") (pinfunction "K_1") (pintype "unspecified"))
      (node (ref "LED7") (pin "1") (pinfunction "K_1") (pintype "unspecified"))
      (node (ref "LED8") (pin "1") (pinfunction "K_1") (pintype "unspecified"))
      (node (ref "Q4") (pin "2") (pinfunction "E_2") (pintype "input"))
      (node (ref "R100") (pin "1") (pinfunction "1_1") (pintype "input"))
      (node (ref "R108") (pin "1") (pinfunction "1_1") (pintype "input"))
      (node (ref "R118") (pin "1") (pinfunction "1_1") (pintype "input"))
      (node (ref "R129") (pin "1") (pinfunction "1_1") (pintype "input"))
      (node (ref "R171") (pin "2") (pinfunction "2_2") (pintype "input"))
      (node (ref "R197") (pin "1") (pinfunction "1_1") (pintype "input"))
      (node (ref "R200") (pin "1") (pinfunction "1_1") (pintype "input"))
      (node (ref "R203") (pin "1") (pinfunction "1_1") (pintype "input"))
      (node (ref "R206") (pin "1") (pinfunction "1_1") (pintype "input"))
      (node (ref "R207") (pin "1") (pinfunction "1_1") (pintype "input"))
      (node (ref "R210") (pin "1") (pinfunction "1_1") (pintype "input"))
      (node (ref "R213") (pin "1") (pinfunction "1_1") (pintype "input"))
      (node (ref "R214") (pin "1") (pinfunction "1_1") (pintype "input"))
      (node (ref "R221") (pin "1") (pinfunction "1_1") (pintype "input"))
      (node (ref "R222") (pin "1") (pinfunction "1_1") (pintype "input"))
      (node (ref "R99") (pin "1") (pinfunction "1_1") (pintype "input"))
      (node (ref "U115") (pin "1") (pinfunction "1_1") (pintype "input"))
      (node (ref "U119") (pin "6") (pinfunction "6_6") (pintype "unspecified"))
      (node (ref "U119") (pin "7") (pinfunction "7_7") (pintype "unspecified"))
      (node (ref "U119") (pin "8") (pinfunction "8_8") (pintype "unspecified"))
      (node (ref "U120") (pin "6") (pinfunction "6_6") (pintype "unspecified"))
      (node (ref "U120") (pin "7") (pinfunction "7_7") (pintype "unspecified"))
      (node (ref "U120") (pin "8") (pinfunction "8_8") (pintype "unspecified"))
      (node (ref "U125") (pin "6") (pinfunction "6_6") (pintype "unspecified"))
      (node (ref "U125") (pin "7") (pinfunction "7_7") (pintype "unspecified"))
      (node (ref "U125") (pin "8") (pinfunction "8_8") (pintype "unspecified"))
      (node (ref "U126") (pin "6") (pinfunction "6_6") (pintype "unspecified"))
      (node (ref "U126") (pin "7") (pinfunction "7_7") (pintype "unspecified"))
      (node (ref "U126") (pin "8") (pinfunction "8_8") (pintype "unspecified"))
      (node (ref "U129") (pin "1") (pinfunction "1_1") (pintype "input"))
      (node (ref "U133") (pin "1") (pinfunction "1_1") (pintype "input"))
      (node (ref "U137") (pin "1") (pinfunction "1_1") (pintype "input"))
      (node (ref "U141") (pin "1") (pinfunction "1_1") (pintype "input"))
      (node (ref "U145") (pin "1") (pinfunction "1_1") (pintype "input"))
      (node (ref "U148") (pin "1") (pinfunction "1_1") (pintype "input"))
      (node (ref "U159") (pin "1") (pinfunction "1_1") (pintype "input"))
      (node (ref "U163") (pin "1") (pinfunction "1_1") (pintype "input"))
      (node (ref "U165") (pin "1") (pinfunction "1_1") (pintype "input"))
      (node (ref "U173") (pin "1") (pinfunction "1_1") (pintype "input"))
      (node (ref "U179") (pin "1") (pinfunction "1_1") (pintype "input"))
      (node (ref "U183") (pin "1") (pinfunction "1_1") (pintype "input"))
      (node (ref "U186") (pin "1") (pinfunction "1_1") (pintype "input"))
      (node (ref "U188") (pin "1") (pinfunction "1_1") (pintype "input"))
      (node (ref "U193") (pin "1") (pinfunction "1_1") (pintype "input"))
      (node (ref "U201") (pin "1") (pinfunction "1_1") (pintype "input"))
      (node (ref "U203") (pin "1") (pinfunction "1_1") (pintype "input"))
      (node (ref "U204") (pin "5") (pinfunction "GND_5") (pintype "input"))
      (node (ref "U204") (pin "7") (pinfunction "EP_7") (pintype "input"))
      (node (ref "U205") (pin "6") (pinfunction "GND_6") (pintype "unspecified"))
      (node (ref "U205") (pin "EPAD") (pinfunction "EPAD_EPAD") (pintype "unspecified"))
      (node (ref "U206") (pin "6") (pinfunction "GND_6") (pintype "unspecified"))
      (node (ref "U206") (pin "EPAD") (pinfunction "EPAD_EPAD") (pintype "unspecified"))
      (node (ref "U30") (pin "6") (pinfunction "GND_6") (pintype "unspecified"))
      (node (ref "U30") (pin "7") (pinfunction "RESV_7") (pintype "unspecified"))
      (node (ref "U30") (pin "9") (pinfunction "INT2/FSYNC/CLKIN_9") (pintype "unspecified"))
      (node (ref "U37") (pin "11") (pinfunction "VSS_11") (pintype "unspecified"))
      (node (ref "U37") (pin "5") (pinfunction "CAD0_5") (pintype "unspecified"))
      (node (ref "U37") (pin "9") (pinfunction "VSS_9") (pintype "unspecified"))
      (node (ref "U38") (pin "2") (pinfunction "GND_2") (pintype "input"))
      (node (ref "U38") (pin "9") (pinfunction "EP_9") (pintype "input"))
      (node (ref "U58") (pin "6") (pinfunction "GND_6") (pintype "unspecified"))
      (node (ref "U58") (pin "7") (pinfunction "RESV_7") (pintype "unspecified"))
      (node (ref "U58") (pin "9") (pinfunction "INT2/FSYNC/CLKIN_9") (pintype "unspecified"))
      (node (ref "U59") (pin "2") (pinfunction "PS_2") (pintype "unspecified"))
      (node (ref "U59") (pin "3") (pinfunction "GND_3") (pintype "unspecified"))
      (node (ref "U6") (pin "20") (pinfunction "AGND_20") (pintype "input"))
      (node (ref "U6") (pin "23") (pinfunction "PGND_23") (pintype "input"))
      (node (ref "U6") (pin "29") (pinfunction "EP_29") (pintype "input"))
      (node (ref "U6") (pin "4") (pinfunction "DGND_4") (pintype "input"))
      (node (ref "U60") (pin "1") (pinfunction "1_1") (pintype "unspecified"))
      (node (ref "U60") (pin "7") (pinfunction "7_7") (pintype "unspecified"))
      (node (ref "U60") (pin "8") (pinfunction "8_8") (pintype "unspecified"))
      (node (ref "U65") (pin "C2") (pinfunction "VSS_C2") (pintype "input"))
      (node (ref "U65") (pin "E4") (pinfunction "VSS_E4") (pintype "input"))
      (node (ref "U65") (pin "E5") (pinfunction "VSS_E5") (pintype "input"))
      (node (ref "U65") (pin "E6") (pinfunction "VSS_E6") (pintype "input"))
      (node (ref "U65") (pin "G1") (pinfunction "VSSA_G1") (pintype "input"))
      (node (ref "U65") (pin "J1") (pinfunction "VSS_J1") (pintype "input"))
      (node (ref "U67") (pin "2") (pinfunction "GND_2") (pintype "input"))
      (node (ref "U67") (pin "9") (pinfunction "EP_9") (pintype "input"))
      (node (ref "U70") (pin "1") (pinfunction "1_1") (pintype "unspecified"))
      (node (ref "U70") (pin "10") (pinfunction "10_10") (pintype "unspecified"))
      (node (ref "U70") (pin "9") (pinfunction "9_9") (pintype "unspecified"))
      (node (ref "U71") (pin "4") (pinfunction "4_4") (pintype "unspecified"))
      (node (ref "U71") (pin "5") (pinfunction "5_5") (pintype "unspecified"))
      (node (ref "U71") (pin "6") (pinfunction "6_6") (pintype "unspecified"))
      (node (ref "U98") (pin "5") (pinfunction "GND_5") (pintype "input"))
      (node (ref "U98") (pin "7") (pinfunction "EP_7") (pintype "input"))
      (node (ref "USB1") (pin "13") (pinfunction "GND_13") (pintype "input"))
      (node (ref "USB1") (pin "14") (pinfunction "GND_14") (pintype "input"))
      (node (ref "USB1") (pin "15") (pinfunction "GND_15") (pintype "input"))
      (node (ref "USB1") (pin "16") (pinfunction "GND_16") (pintype "input"))
      (node (ref "USB1") (pin "A1B12") (pinfunction "GND_A1B12") (pintype "input"))
      (node (ref "USB1") (pin "B1A12") (pinfunction "GND_B1A12") (pintype "input"))
      (node (ref "X2") (pin "2") (pinfunction "GND_2") (pintype "input"))
      (node (ref "X3") (pin "2") (pinfunction "GND_2") (pintype "input"))
      (node (ref "X3") (pin "4") (pinfunction "GND_4") (pintype "input"))
    )
    (net (code "25") (name "GPIO_CAN1_SILENT") (class "Default")
      (node (ref "R227") (pin "1") (pinfunction "1_1") (pintype "input"))
      (node (ref "U38") (pin "8") (pinfunction "S_8") (pintype "input"))
      (node (ref "U65") (pin "B3") (pinfunction "PE3_B3") (pintype "input"))
    )
    (net (code "26") (name "GPIO_CAN2_SILENT") (class "Default")
      (node (ref "R173") (pin "1") (pinfunction "1_1") (pintype "input"))
      (node (ref "U65") (pin "H7") (pinfunction "PE15_H7") (pintype "input"))
      (node (ref "U67") (pin "8") (pinfunction "S_8") (pintype "input"))
    )
    (net (code "27") (name "I2C1_SCL") (class "Default")
      (node (ref "R76") (pin "1") (pinfunction "1_1") (pintype "input"))
      (node (ref "U199") (pin "1") (pinfunction "1_1") (pintype "input"))
      (node (ref "U37") (pin "1") (pinfunction "SCL_1") (pintype "unspecified"))
      (node (ref "U65") (pin "B4") (pinfunction "PB8_B4") (pintype "input"))
    )
    (net (code "28") (name "I2C1_SDA") (class "Default")
      (node (ref "R88") (pin "1") (pinfunction "1_1") (pintype "input"))
      (node (ref "U202") (pin "1") (pinfunction "1_1") (pintype "input"))
      (node (ref "U37") (pin "16") (pinfunction "SDA_16") (pintype "unspecified"))
      (node (ref "U65") (pin "A5") (pinfunction "PB7_A5") (pintype "input"))
    )
    (net (code "29") (name "I2C2_SCL") (class "Default")
      (node (ref "R191") (pin "1") (pinfunction "1_1") (pintype "input"))
      (node (ref "R192") (pin "1") (pinfunction "1_1") (pintype "input"))
      (node (ref "U65") (pin "J7") (pinfunction "PB10_J7") (pintype "input"))
    )
    (net (code "30") (name "I2C2_SCL_GPS2") (class "Default")
      (node (ref "R192") (pin "2") (pinfunction "2_2") (pintype "input"))
      (node (ref "U126") (pin "4") (pinfunction "4_4") (pintype "unspecified"))
      (node (ref "U180") (pin "1") (pinfunction "1_1") (pintype "input"))
    )
    (net (code "31") (name "I2C2_SDA") (class "Default")
      (node (ref "R190") (pin "1") (pinfunction "1_1") (pintype "input"))
      (node (ref "R193") (pin "1") (pinfunction "1_1") (pintype "input"))
      (node (ref "U65") (pin "K7") (pinfunction "PB11_K7") (pintype "input"))
    )
    (net (code "32") (name "I2C2_SDA_GPS2") (class "Default")
      (node (ref "R193") (pin "2") (pinfunction "2_2") (pintype "input"))
      (node (ref "U126") (pin "5") (pinfunction "5_5") (pintype "unspecified"))
      (node (ref "U181") (pin "1") (pinfunction "1_1") (pintype "input"))
    )
    (net (code "33") (name "I2C3_SCL") (class "Default")
      (node (ref "R185") (pin "1") (pinfunction "1_1") (pintype "input"))
      (node (ref "R186") (pin "1") (pinfunction "1_1") (pintype "input"))
      (node (ref "U65") (pin "D9") (pinfunction "PA8_D9") (pintype "input"))
    )
    (net (code "34") (name "I2C3_SCL_GPS2") (class "Default")
      (node (ref "R186") (pin "2") (pinfunction "2_2") (pintype "input"))
      (node (ref "U125") (pin "4") (pinfunction "4_4") (pintype "unspecified"))
      (node (ref "U174") (pin "1") (pinfunction "1_1") (pintype "input"))
    )
    (net (code "35") (name "I2C3_SDA") (class "Default")
      (node (ref "R184") (pin "1") (pinfunction "1_1") (pintype "input"))
      (node (ref "R187") (pin "1") (pinfunction "1_1") (pintype "input"))
      (node (ref "U65") (pin "E9") (pinfunction "PC9_E9") (pintype "input"))
    )
    (net (code "36") (name "I2C3_SDA_GPS2") (class "Default")
      (node (ref "R187") (pin "2") (pinfunction "2_2") (pintype "input"))
      (node (ref "U125") (pin "5") (pinfunction "5_5") (pintype "unspecified"))
      (node (ref "U175") (pin "1") (pinfunction "1_1") (pintype "input"))
    )
    (net (code "37") (name "I2C4_SCL") (class "Default")
      (node (ref "R224") (pin "1") (pinfunction "1_1") (pintype "input"))
      (node (ref "R225") (pin "1") (pinfunction "1_1") (pintype "input"))
      (node (ref "U65") (pin "K10") (pinfunction "PD12_K10") (pintype "input"))
    )
    (net (code "38") (name "I2C4_SCL_PORT") (class "Default")
      (node (ref "R225") (pin "2") (pinfunction "2_2") (pintype "input"))
      (node (ref "U143") (pin "1") (pinfunction "1_1") (pintype "input"))
    )
    (net (code "39") (name "I2C4_SDA") (class "Default")
      (node (ref "R223") (pin "1") (pinfunction "1_1") (pintype "input"))
      (node (ref "R226") (pin "1") (pinfunction "1_1") (pintype "input"))
      (node (ref "U65") (pin "J10") (pinfunction "PD13_J10") (pintype "input"))
    )
    (net (code "40") (name "I2C4_SDA_PORT") (class "Default")
      (node (ref "R226") (pin "2") (pinfunction "2_2") (pintype "input"))
      (node (ref "U146") (pin "1") (pinfunction "1_1") (pintype "input"))
    )
    (net (code "41") (name "INT_1") (class "Default")
      (node (ref "U58") (pin "4") (pinfunction "INT1/INT_4") (pintype "unspecified"))
      (node (ref "U65") (pin "H9") (pinfunction "PD10_H9") (pintype "input"))
    )
    (net (code "42") (name "INT_2") (class "Default")
      (node (ref "U30") (pin "4") (pinfunction "INT1/INT_4") (pintype "unspecified"))
      (node (ref "U65") (pin "G8") (pinfunction "PD15_G8") (pintype "input"))
    )
    (net (code "43") (name "LED1") (class "Default")
      (node (ref "R229") (pin "1") (pinfunction "1_1") (pintype "input"))
      (node (ref "U65") (pin "A1") (pinfunction "PC14-OSC32_IN_A1") (pintype "input"))
    )
    (net (code "44") (name "LED2") (class "Default")
      (node (ref "R230") (pin "1") (pinfunction "1_1") (pintype "input"))
      (node (ref "U65") (pin "A2") (pinfunction "PC13_A2") (pintype "input"))
    )
    (net (code "45") (name "MCU_3V3") (class "Default")
      (node (ref "C151") (pin "2") (pinfunction "2_2") (pintype "unspecified"))
      (node (ref "C152") (pin "1") (pinfunction "1_1") (pintype "input"))
      (node (ref "C153") (pin "2") (pinfunction "2_2") (pintype "unspecified"))
      (node (ref "C22") (pin "2") (pinfunction "2_2") (pintype "unspecified"))
      (node (ref "C23") (pin "2") (pinfunction "2_2") (pintype "unspecified"))
      (node (ref "C24") (pin "2") (pinfunction "2_2") (pintype "unspecified"))
      (node (ref "C25") (pin "2") (pinfunction "2_2") (pintype "unspecified"))
      (node (ref "C26") (pin "2") (pinfunction "2_2") (pintype "unspecified"))
      (node (ref "C27") (pin "2") (pinfunction "2_2") (pintype "unspecified"))
      (node (ref "CARD4") (pin "4") (pinfunction "VDD_4") (pintype "input"))
      (node (ref "R109") (pin "2") (pinfunction "2_2") (pintype "input"))
      (node (ref "R110") (pin "1") (pinfunction "1_1") (pintype "input"))
      (node (ref "R111") (pin "1") (pinfunction "1_1") (pintype "input"))
      (node (ref "R184") (pin "2") (pinfunction "2_2") (pintype "input"))
      (node (ref "R185") (pin "2") (pinfunction "2_2") (pintype "input"))
      (node (ref "R190") (pin "2") (pinfunction "2_2") (pintype "input"))
      (node (ref "R191") (pin "2") (pinfunction "2_2") (pintype "input"))
      (node (ref "R196") (pin "1") (pinfunction "1_1") (pintype "input"))
      (node (ref "R199") (pin "2") (pinfunction "2_2") (pintype "input"))
      (node (ref "R223") (pin "2") (pinfunction "2_2") (pintype "input"))
      (node (ref "R224") (pin "2") (pinfunction "2_2") (pintype "input"))
      (node (ref "SW3") (pin "1") (pinfunction "1_1") (pintype "unspecified"))
      (node (ref "SW3") (pin "2") (pinfunction "2_2") (pintype "unspecified"))
      (node (ref "U38") (pin "5") (pinfunction "VIO_5") (pintype "input"))
      (node (ref "U65") (pin "B2") (pinfunction "VBAT_B2") (pintype "input"))
      (node (ref "U65") (pin "D2") (pinfunction "VDD_D2") (pintype "input"))
      (node (ref "U65") (pin "F4") (pinfunction "VDDLDO_F4") (pintype "input"))
      (node (ref "U65") (pin "F5") (pinfunction "VDD_F5") (pintype "input"))
      (node (ref "U65") (pin "F6") (pinfunction "33USB_F6") (pintype "input"))
      (node (ref "U65") (pin "F7") (pinfunction "PDR_ON_F7") (pintype "input"))
      (node (ref "U65") (pin "H1") (pinfunction "VDDA_H1") (pintype "input"))
      (node (ref "U65") (pin "K1") (pinfunction "VDD_K1") (pintype "input"))
      (node (ref "U67") (pin "5") (pinfunction "VIO_5") (pintype "input"))
      (node (ref "U98") (pin "1") (pinfunction "OUT_1") (pintype "input"))
    )
    (net (code "46") (name "MCU_OSC_IN") (class "Default")
      (node (ref "C84") (pin "1") (pinfunction "1_1") (pintype "input"))
      (node (ref "U65") (pin "C1") (pinfunction "PHO-OSC_IN_C1") (pintype "input"))
      (node (ref "X2") (pin "3") (pinfunction "OSC2_3") (pintype "input"))
    )
    (net (code "47") (name "MCU_OSC_OUT") (class "Default")
      (node (ref "C85") (pin "2") (pinfunction "2_2") (pintype "input"))
      (node (ref "U65") (pin "D1") (pinfunction "PH1-OSC_OUT_D1") (pintype "input"))
      (node (ref "X2") (pin "1") (pinfunction "OSC1_1") (pintype "input"))
    )
    (net (code "48") (name "NRST") (class "Default")
      (node (ref "C83") (pin "2") (pinfunction "2_2") (pintype "unspecified"))
      (node (ref "R109") (pin "1") (pinfunction "1_1") (pintype "input"))
      (node (ref "U65") (pin "E1") (pinfunction "NRST_E1") (pintype "input"))
    )
    (net (code "49") (name "Net-(C133-Pad2)") (class "Default")
      (node (ref "C133") (pin "2") (pinfunction "2_2") (pintype "unspecified"))
      (node (ref "C134") (pin "2") (pinfunction "2_2") (pintype "unspecified"))
      (node (ref "R128") (pin "1") (pinfunction "1_1") (pintype "input"))
    )
    (net (code "50") (name "Net-(C162-Pad1)") (class "Default")
      (node (ref "C162") (pin "1") (pinfunction "1_1") (pintype "input"))
      (node (ref "R206") (pin "2") (pinfunction "2_2") (pintype "input"))
    )
    (net (code "51") (name "Net-(C165-Pad2)") (class "Default")
      (node (ref "C165") (pin "2") (pinfunction "2_2") (pintype "unspecified"))
      (node (ref "R209") (pin "2") (pinfunction "2_2") (pintype "input"))
    )
    (net (code "52") (name "Net-(C168-Pad1)") (class "Default")
      (node (ref "C168") (pin "1") (pinfunction "1_1") (pintype "input"))
      (node (ref "R213") (pin "2") (pinfunction "2_2") (pintype "input"))
    )
    (net (code "53") (name "Net-(C171-Pad2)") (class "Default")
      (node (ref "C171") (pin "2") (pinfunction "2_2") (pintype "unspecified"))
      (node (ref "R216") (pin "2") (pinfunction "2_2") (pintype "input"))
    )
    (net (code "54") (name "Net-(D6-K)") (class "Default")
      (node (ref "C165") (pin "1") (pinfunction "1_1") (pintype "unspecified"))
      (node (ref "D6") (pin "1") (pinfunction "K_1") (pintype "unspecified"))
      (node (ref "L8") (pin "1") (pinfunction "1_1") (pintype "input"))
      (node (ref "U205") (pin "1") (pinfunction "SW_1") (pintype "unspecified"))
      (node (ref "U205") (pin "2") (pinfunction "SW_2") (pintype "unspecified"))
    )
    (net (code "55") (name "Net-(D7-K)") (class "Default")
      (node (ref "C171") (pin "1") (pinfunction "1_1") (pintype "unspecified"))
      (node (ref "D7") (pin "1") (pinfunction "K_1") (pintype "unspecified"))
      (node (ref "L9") (pin "1") (pinfunction "1_1") (pintype "input"))
      (node (ref "U206") (pin "1") (pinfunction "SW_1") (pintype "unspecified"))
      (node (ref "U206") (pin "2") (pinfunction "SW_2") (pintype "unspecified"))
    )
    (net (code "56") (name "Net-(LED6-A)") (class "Default")
      (node (ref "LED6") (pin "2") (pinfunction "A_2") (pintype "unspecified"))
      (node (ref "R230") (pin "2") (pinfunction "2_2") (pintype "input"))
    )
    (net (code "57") (name "Net-(LED7-A)") (class "Default")
      (node (ref "LED7") (pin "2") (pinfunction "A_2") (pintype "unspecified"))
      (node (ref "R229") (pin "2") (pinfunction "2_2") (pintype "input"))
    )
    (net (code "58") (name "Net-(LED8-A)") (class "Default")
      (node (ref "LED8") (pin "2") (pinfunction "A_2") (pintype "unspecified"))
      (node (ref "R143") (pin "2") (pinfunction "2_2") (pintype "input"))
    )
    (net (code "59") (name "Net-(Q4-B)") (class "Default")
      (node (ref "Q4") (pin "1") (pinfunction "B_1") (pintype "input"))
      (node (ref "R228") (pin "2") (pinfunction "2_2") (pintype "input"))
    )
    (net (code "60") (name "Net-(U6-RESET#)") (class "Default")
      (node (ref "R131") (pin "2") (pinfunction "2_2") (pintype "input"))
      (node (ref "U6") (pin "19") (pinfunction "RESET#_19") (pintype "input"))
    )
    (net (code "61") (name "Net-(U6-SAG)") (class "Default")
      (node (ref "C134") (pin "1") (pinfunction "1_1") (pintype "unspecified"))
      (node (ref "U6") (pin "25") (pinfunction "SAG_25") (pintype "input"))
    )
    (net (code "62") (name "Net-(U6-VIN)") (class "Default")
      (node (ref "C120") (pin "2") (pinfunction "2_2") (pintype "unspecified"))
      (node (ref "U6") (pin "22") (pinfunction "VIN_22") (pintype "input"))
    )
    (net (code "63") (name "Net-(U6-VOUT)") (class "Default")
      (node (ref "C133") (pin "1") (pinfunction "1_1") (pintype "unspecified"))
      (node (ref "U6") (pin "26") (pinfunction "VOUT_26") (pintype "input"))
    )
    (net (code "64") (name "Net-(U37-C1)") (class "Default")
      (node (ref "C102") (pin "1") (pinfunction "1_1") (pintype "input"))
      (node (ref "U37") (pin "10") (pinfunction "C1_10") (pintype "unspecified"))
    )
    (net (code "65") (name "Net-(U37-RSTN)") (class "Default")
      (node (ref "C117") (pin "2") (pinfunction "2_2") (pintype "unspecified"))
      (node (ref "U37") (pin "14") (pinfunction "RSTN_14") (pintype "unspecified"))
    )
    (net (code "66") (name "Net-(U98-EN)") (class "Default")
      (node (ref "R198") (pin "1") (pinfunction "1_1") (pintype "input"))
      (node (ref "U98") (pin "4") (pinfunction "EN_4") (pintype "input"))
    )
    (net (code "67") (name "Net-(U98-PG)") (class "Default")
      (node (ref "R199") (pin "1") (pinfunction "1_1") (pintype "input"))
      (node (ref "U98") (pin "3") (pinfunction "PG_3") (pintype "input"))
    )
    (net (code "68") (name "Net-(U204-EN)") (class "Default")
      (node (ref "R201") (pin "1") (pinfunction "1_1") (pintype "input"))
      (node (ref "U204") (pin "4") (pinfunction "EN_4") (pintype "input"))
    )
    (net (code "69") (name "Net-(U204-PG)") (class "Default")
      (node (ref "R202") (pin "1") (pinfunction "1_1") (pintype "input"))
      (node (ref "U204") (pin "3") (pinfunction "PG_3") (pintype "input"))
    )
    (net (code "70") (name "Net-(U205-BST)") (class "Default")
      (node (ref "R209") (pin "1") (pinfunction "1_1") (pintype "input"))
      (node (ref "U205") (pin "10") (pinfunction "BST_10") (pintype "unspecified"))
    )
    (net (code "71") (name "Net-(U205-COMP)") (class "Default")
      (node (ref "C162") (pin "2") (pinfunction "2_2") (pintype "input"))
      (node (ref "U205") (pin "4") (pinfunction "COMP_4") (pintype "unspecified"))
    )
    (net (code "72") (name "Net-(U205-EN)") (class "Default")
      (node (ref "R203") (pin "2") (pinfunction "2_2") (pintype "input"))
      (node (ref "R204") (pin "1") (pinfunction "1_1") (pintype "input"))
      (node (ref "U205") (pin "3") (pinfunction "EN_3") (pintype "unspecified"))
    )
    (net (code "73") (name "Net-(U205-FB)") (class "Default")
      (node (ref "R207") (pin "2") (pinfunction "2_2") (pintype "input"))
      (node (ref "R220") (pin "1") (pinfunction "1_1") (pintype "input"))
      (node (ref "U205") (pin "5") (pinfunction "FB_5") (pintype "unspecified"))
    )
    (net (code "74") (name "Net-(U205-FREQ)") (class "Default")
      (node (ref "R221") (pin "2") (pinfunction "2_2") (pintype "input"))
      (node (ref "U205") (pin "7") (pinfunction "FREQ_7") (pintype "unspecified"))
    )
    (net (code "75") (name "Net-(U206-BST)") (class "Default")
      (node (ref "R216") (pin "1") (pinfunction "1_1") (pintype "input"))
      (node (ref "U206") (pin "10") (pinfunction "BST_10") (pintype "unspecified"))
    )
    (net (code "76") (name "Net-(U206-COMP)") (class "Default")
      (node (ref "C168") (pin "2") (pinfunction "2_2") (pintype "input"))
      (node (ref "U206") (pin "4") (pinfunction "COMP_4") (pintype "unspecified"))
    )
    (net (code "77") (name "Net-(U206-EN)") (class "Default")
      (node (ref "R210") (pin "2") (pinfunction "2_2") (pintype "input"))
      (node (ref "R211") (pin "1") (pinfunction "1_1") (pintype "input"))
      (node (ref "U206") (pin "3") (pinfunction "EN_3") (pintype "unspecified"))
    )
    (net (code "78") (name "Net-(U206-FB)") (class "Default")
      (node (ref "R214") (pin "2") (pinfunction "2_2") (pintype "input"))
      (node (ref "R219") (pin "1") (pinfunction "1_1") (pintype "input"))
      (node (ref "U206") (pin "5") (pinfunction "FB_5") (pintype "unspecified"))
    )
    (net (code "79") (name "Net-(U206-FREQ)") (class "Default")
      (node (ref "R222") (pin "2") (pinfunction "2_2") (pintype "input"))
      (node (ref "U206") (pin "7") (pinfunction "FREQ_7") (pintype "unspecified"))
    )
    (net (code "80") (name "OSD_OSC_IN") (class "Default")
      (node (ref "U6") (pin "5") (pinfunction "CLKIN_5") (pintype "input"))
      (node (ref "X3") (pin "1") (pinfunction "OSC1_1") (pintype "input"))
    )
    (net (code "81") (name "OSD_OSC_OUT") (class "Default")
      (node (ref "U6") (pin "6") (pinfunction "XFB_6") (pintype "input"))
      (node (ref "X3") (pin "3") (pinfunction "OSC2_3") (pintype "input"))
    )
    (net (code "82") (name "OUT1") (class "Default")
      (node (ref "R133") (pin "2") (pinfunction "2_2") (pintype "input"))
      (node (ref "U150") (pin "1") (pinfunction "1_1") (pintype "input"))
      (node (ref "U70") (pin "3") (pinfunction "3_3") (pintype "unspecified"))
    )
    (net (code "83") (name "OUT2") (class "Default")
      (node (ref "R134") (pin "2") (pinfunction "2_2") (pintype "input"))
      (node (ref "U149") (pin "1") (pinfunction "1_1") (pintype "input"))
      (node (ref "U70") (pin "4") (pinfunction "4_4") (pintype "unspecified"))
    )
    (net (code "84") (name "OUT3") (class "Default")
      (node (ref "R135") (pin "2") (pinfunction "2_2") (pintype "input"))
      (node (ref "U152") (pin "1") (pinfunction "1_1") (pintype "input"))
      (node (ref "U70") (pin "5") (pinfunction "5_5") (pintype "unspecified"))
    )
    (net (code "85") (name "OUT4") (class "Default")
      (node (ref "R136") (pin "2") (pinfunction "2_2") (pintype "input"))
      (node (ref "U151") (pin "1") (pinfunction "1_1") (pintype "input"))
      (node (ref "U70") (pin "6") (pinfunction "6_6") (pintype "unspecified"))
    )
    (net (code "86") (name "OUT5") (class "Default")
      (node (ref "R137") (pin "2") (pinfunction "2_2") (pintype "input"))
      (node (ref "U154") (pin "1") (pinfunction "1_1") (pintype "input"))
      (node (ref "U60") (pin "3") (pinfunction "3_3") (pintype "unspecified"))
    )
    (net (code "87") (name "OUT6") (class "Default")
      (node (ref "R138") (pin "2") (pinfunction "2_2") (pintype "input"))
      (node (ref "U153") (pin "1") (pinfunction "1_1") (pintype "input"))
      (node (ref "U60") (pin "4") (pinfunction "4_4") (pintype "unspecified"))
    )
    (net (code "88") (name "OUT7") (class "Default")
      (node (ref "R139") (pin "2") (pinfunction "2_2") (pintype "input"))
      (node (ref "U156") (pin "1") (pinfunction "1_1") (pintype "input"))
      (node (ref "U60") (pin "5") (pinfunction "5_5") (pintype "unspecified"))
    )
    (net (code "89") (name "OUT8") (class "Default")
      (node (ref "R140") (pin "2") (pinfunction "2_2") (pintype "input"))
      (node (ref "U155") (pin "1") (pinfunction "1_1") (pintype "input"))
      (node (ref "U60") (pin "6") (pinfunction "6_6") (pintype "unspecified"))
    )
    (net (code "90") (name "OUT9") (class "Default")
      (node (ref "R174") (pin "2") (pinfunction "2_2") (pintype "input"))
      (node (ref "U118") (pin "1") (pinfunction "1_1") (pintype "input"))
    )
    (net (code "91") (name "OUT10") (class "Default")
      (node (ref "R175") (pin "2") (pinfunction "2_2") (pintype "input"))
      (node (ref "U117") (pin "1") (pinfunction "1_1") (pintype "input"))
    )
    (net (code "92") (name "RSSI_ADC") (class "Default")
      (node (ref "U161") (pin "1") (pinfunction "1_1") (pintype "input"))
      (node (ref "U65") (pin "G4") (pinfunction "PC4_G4") (pintype "input"))
    )
    (net (code "93") (name "S1") (class "Default")
      (node (ref "R133") (pin "1") (pinfunction "1_1") (pintype "input"))
      (node (ref "U65") (pin "G2") (pinfunction "PA0_G2") (pintype "input"))
    )
    (net (code "94") (name "S2") (class "Default")
      (node (ref "R134") (pin "1") (pinfunction "1_1") (pintype "input"))
      (node (ref "U65") (pin "J2") (pinfunction "PA2_J2") (pintype "input"))
    )
    (net (code "95") (name "S3") (class "Default")
      (node (ref "R135") (pin "1") (pinfunction "1_1") (pintype "input"))
      (node (ref "U65") (pin "J3") (pinfunction "PA6_J3") (pintype "input"))
    )
    (net (code "96") (name "S4") (class "Default")
      (node (ref "R136") (pin "1") (pinfunction "1_1") (pintype "input"))
      (node (ref "U65") (pin "K2") (pinfunction "PA3_K2") (pintype "input"))
    )
    (net (code "97") (name "S5") (class "Default")
      (node (ref "R137") (pin "1") (pinfunction "1_1") (pintype "input"))
      (node (ref "U65") (pin "K3") (pinfunction "PA7_K3") (pintype "input"))
    )
    (net (code "98") (name "S6") (class "Default")
      (node (ref "R138") (pin "1") (pinfunction "1_1") (pintype "input"))
      (node (ref "U65") (pin "K4") (pinfunction "PB1_K4") (pintype "input"))
    )
    (net (code "99") (name "S7") (class "Default")
      (node (ref "R139") (pin "1") (pinfunction "1_1") (pintype "input"))
      (node (ref "U65") (pin "K5") (pinfunction "PE9_K5") (pintype "input"))
    )
    (net (code "100") (name "S8") (class "Default")
      (node (ref "R140") (pin "1") (pinfunction "1_1") (pintype "input"))
      (node (ref "U65") (pin "G7") (pinfunction "PE14_G7") (pintype "input"))
    )
    (net (code "101") (name "S9") (class "Default")
      (node (ref "R174") (pin "1") (pinfunction "1_1") (pintype "input"))
      (node (ref "U65") (pin "F9") (pinfunction "PC8_F9") (pintype "input"))
    )
    (net (code "102") (name "S10") (class "Default")
      (node (ref "R175") (pin "1") (pinfunction "1_1") (pintype "input"))
      (node (ref "U65") (pin "D10") (pinfunction "PA10_D10") (pintype "input"))
    )
    (net (code "103") (name "SPI1_MISO") (class "Default")
      (node (ref "U58") (pin "1") (pinfunction "AP_SDO/AP_AD0_1") (pintype "unspecified"))
      (node (ref "U65") (pin "A6") (pinfunction "PB4_A6") (pintype "input"))
    )
    (net (code "104") (name "SPI1_MOSI") (class "Default")
      (node (ref "U58") (pin "14") (pinfunction "AP_SDA/AP_SDIO/AP_SDI_14") (pintype "unspecified"))
      (node (ref "U65") (pin "D6") (pinfunction "PD7_D6") (pintype "input"))
    )
    (net (code "105") (name "SPI1_NSS") (class "Default")
      (node (ref "U58") (pin "12") (pinfunction "AP_CS_12") (pintype "unspecified"))
      (node (ref "U65") (pin "A8") (pinfunction "PA15_A8") (pintype "input"))
    )
    (net (code "106") (name "SPI1_SCK") (class "Default")
      (node (ref "U58") (pin "13") (pinfunction "AP_SCL/AP_SCLK_13") (pintype "unspecified"))
      (node (ref "U65") (pin "H3") (pinfunction "PA5_H3") (pintype "input"))
    )
    (net (code "107") (name "SPI2_MISO") (class "Default")
      (node (ref "CARD4") (pin "7") (pinfunction "DAT0_7") (pintype "input"))
      (node (ref "R111") (pin "2") (pinfunction "2_2") (pintype "input"))
      (node (ref "U65") (pin "E2") (pinfunction "PC2_C_E2") (pintype "input"))
    )
    (net (code "108") (name "SPI2_MOIS") (class "Default")
      (node (ref "CARD4") (pin "3") (pinfunction "CMD_3") (pintype "input"))
      (node (ref "U65") (pin "F3") (pinfunction "PC3_C_F3") (pintype "input"))
    )
    (net (code "109") (name "SPI2_NSS") (class "Default")
      (node (ref "CARD4") (pin "2") (pinfunction "CD/DAT3_2") (pintype "input"))
      (node (ref "R110") (pin "2") (pinfunction "2_2") (pintype "input"))
      (node (ref "U65") (pin "K8") (pinfunction "PB12_K8") (pintype "input"))
    )
    (net (code "110") (name "SPI2_SCK") (class "Default")
      (node (ref "CARD4") (pin "5") (pinfunction "CLK_5") (pintype "input"))
      (node (ref "R196") (pin "2") (pinfunction "2_2") (pintype "input"))
      (node (ref "U65") (pin "C9") (pinfunction "PA9_C9") (pintype "input"))
    )
    (net (code "111") (name "SPI3_MISO") (class "Default")
      (node (ref "U6") (pin "11") (pinfunction "SDOUT_11") (pintype "input"))
      (node (ref "U65") (pin "B8") (pinfunction "PC11_B8") (pintype "input"))
    )
    (net (code "112") (name "SPI3_MOIS") (class "Default")
      (node (ref "U6") (pin "9") (pinfunction "SDIN_9") (pintype "input"))
      (node (ref "U65") (pin "G5") (pinfunction "PB2_G5") (pintype "input"))
    )
    (net (code "113") (name "SPI3_NSS") (class "Default")
      (node (ref "R130") (pin "1") (pinfunction "1_1") (pintype "input"))
      (node (ref "U6") (pin "8") (pinfunction "CS#_8") (pintype "input"))
      (node (ref "U65") (pin "G3") (pinfunction "PA4_G3") (pintype "input"))
    )
    (net (code "114") (name "SPI3_SCK") (class "Default")
      (node (ref "U6") (pin "10") (pinfunction "SCLK_10") (pintype "input"))
      (node (ref "U65") (pin "B9") (pinfunction "PC10_B9") (pintype "input"))
    )
    (net (code "115") (name "SPI4_MISO") (class "Default")
      (node (ref "U30") (pin "1") (pinfunction "AP_SDO/AP_AD0_1") (pintype "unspecified"))
      (node (ref "U59") (pin "6") (pinfunction "SDO_6") (pintype "unspecified"))
      (node (ref "U65") (pin "D3") (pinfunction "PE5_D3") (pintype "input"))
    )
    (net (code "116") (name "SPI4_MOSI") (class "Default")
      (node (ref "U30") (pin "14") (pinfunction "AP_SDA/AP_SDIO/AP_SDI_14") (pintype "unspecified"))
      (node (ref "U59") (pin "7") (pinfunction "SDI/SDA_7") (pintype "unspecified"))
      (node (ref "U65") (pin "E3") (pinfunction "PE6_E3") (pintype "input"))
    )
    (net (code "117") (name "SPI4_NSS_1") (class "Default")
      (node (ref "U30") (pin "12") (pinfunction "AP_CS_12") (pintype "unspecified"))
      (node (ref "U65") (pin "C3") (pinfunction "PE4_C3") (pintype "input"))
    )
    (net (code "118") (name "SPI4_NSS_2") (class "Default")
      (node (ref "U59") (pin "5") (pinfunction "CSB_5") (pintype "unspecified"))
      (node (ref "U65") (pin "H6") (pinfunction "PE11_H6") (pintype "input"))
    )
    (net (code "119") (name "SPI4_SCK") (class "Default")
      (node (ref "U30") (pin "13") (pinfunction "AP_SCL/AP_SCLK_13") (pintype "unspecified"))
      (node (ref "U59") (pin "8") (pinfunction "SCLK_8") (pintype "unspecified"))
      (node (ref "U65") (pin "A3") (pinfunction "PE2_A3") (pintype "input"))
    )
    (net (code "120") (name "SWCLK") (class "Default")
      (node (ref "U190") (pin "1") (pinfunction "1_1") (pintype "input"))
      (node (ref "U65") (pin "A9") (pinfunction "PA14_A9") (pintype "input"))
    )
    (net (code "121") (name "SWDIO") (class "Default")
      (node (ref "U191") (pin "1") (pinfunction "1_1") (pintype "input"))
      (node (ref "U65") (pin "A10") (pinfunction "PA13_A10") (pintype "input"))
    )
    (net (code "122") (name "TELEM1_CTS") (class "Default")
      (node (ref "R179") (pin "2") (pinfunction "2_2") (pintype "input"))
      (node (ref "U119") (pin "5") (pinfunction "5_5") (pintype "unspecified"))
      (node (ref "U167") (pin "1") (pinfunction "1_1") (pintype "input"))
    )
    (net (code "123") (name "TELEM1_RTS") (class "Default")
      (node (ref "R178") (pin "2") (pinfunction "2_2") (pintype "input"))
      (node (ref "U119") (pin "4") (pinfunction "4_4") (pintype "unspecified"))
      (node (ref "U166") (pin "1") (pinfunction "1_1") (pintype "input"))
    )
    (net (code "124") (name "TELEM1_RX") (class "Default")
      (node (ref "R177") (pin "2") (pinfunction "2_2") (pintype "input"))
      (node (ref "U119") (pin "3") (pinfunction "3_3") (pintype "unspecified"))
      (node (ref "U122") (pin "1") (pinfunction "1_1") (pintype "input"))
    )
    (net (code "125") (name "TELEM1_TX") (class "Default")
      (node (ref "R176") (pin "2") (pinfunction "2_2") (pintype "input"))
      (node (ref "U119") (pin "2") (pinfunction "2_2") (pintype "unspecified"))
      (node (ref "U121") (pin "1") (pinfunction "1_1") (pintype "input"))
    )
    (net (code "126") (name "TELEM2_CTS") (class "Default")
      (node (ref "R183") (pin "2") (pinfunction "2_2") (pintype "input"))
      (node (ref "U120") (pin "5") (pinfunction "5_5") (pintype "unspecified"))
      (node (ref "U169") (pin "1") (pinfunction "1_1") (pintype "input"))
    )
    (net (code "127") (name "TELEM2_RTS") (class "Default")
      (node (ref "R182") (pin "2") (pinfunction "2_2") (pintype "input"))
      (node (ref "U120") (pin "4") (pinfunction "4_4") (pintype "unspecified"))
      (node (ref "U168") (pin "1") (pinfunction "1_1") (pintype "input"))
    )
    (net (code "128") (name "TELEM2_RX") (class "Default")
      (node (ref "R181") (pin "2") (pinfunction "2_2") (pintype "input"))
      (node (ref "U120") (pin "3") (pinfunction "3_3") (pintype "unspecified"))
      (node (ref "U124") (pin "1") (pinfunction "1_1") (pintype "input"))
    )
    (net (code "129") (name "TELEM2_TX") (class "Default")
      (node (ref "R180") (pin "2") (pinfunction "2_2") (pintype "input"))
      (node (ref "U120") (pin "2") (pinfunction "2_2") (pintype "unspecified"))
      (node (ref "U123") (pin "1") (pinfunction "1_1") (pintype "input"))
    )
    (net (code "130") (name "UART4_RX") (class "Default")
      (node (ref "R189") (pin "1") (pinfunction "1_1") (pintype "input"))
      (node (ref "U65") (pin "H2") (pinfunction "PA1_H2") (pintype "input"))
    )
    (net (code "131") (name "UART4_RX_GPS") (class "Default")
      (node (ref "R189") (pin "2") (pinfunction "2_2") (pintype "input"))
      (node (ref "U125") (pin "3") (pinfunction "3_3") (pintype "unspecified"))
      (node (ref "U171") (pin "1") (pinfunction "1_1") (pintype "input"))
    )
    (net (code "132") (name "UART4_TX") (class "Default")
      (node (ref "R188") (pin "1") (pinfunction "1_1") (pintype "input"))
      (node (ref "U65") (pin "E8") (pinfunction "PD1_E8") (pintype "input"))
    )
    (net (code "133") (name "UART4_TX_GPS") (class "Default")
      (node (ref "R188") (pin "2") (pinfunction "2_2") (pintype "input"))
      (node (ref "U125") (pin "2") (pinfunction "2_2") (pintype "unspecified"))
      (node (ref "U170") (pin "1") (pinfunction "1_1") (pintype "input"))
    )
    (net (code "134") (name "UART5_RX") (class "Default")
      (node (ref "U116") (pin "1") (pinfunction "1_1") (pintype "input"))
      (node (ref "U65") (pin "B7") (pinfunction "PD2_B7") (pintype "input"))
    )
    (net (code "135") (name "UART5_TX") (class "Default")
      (node (ref "U106") (pin "1") (pinfunction "1_1") (pintype "input"))
      (node (ref "U65") (pin "C8") (pinfunction "PC12_C8") (pintype "input"))
    )
    (net (code "136") (name "UART7_RX") (class "Default")
      (node (ref "U138") (pin "1") (pinfunction "1_1") (pintype "input"))
      (node (ref "U65") (pin "H5") (pinfunction "PE7_H5") (pintype "input"))
      (node (ref "U70") (pin "7") (pinfunction "7_7") (pintype "unspecified"))
    )
    (net (code "137") (name "UART7_TX") (class "Default")
      (node (ref "U135") (pin "1") (pinfunction "1_1") (pintype "input"))
      (node (ref "U65") (pin "J5") (pinfunction "PE8_J5") (pintype "input"))
    )
    (net (code "138") (name "UART8_RX") (class "Default")
      (node (ref "U134") (pin "1") (pinfunction "1_1") (pintype "input"))
      (node (ref "U65") (pin "D4") (pinfunction "PE0_D4") (pintype "input"))
    )
    (net (code "139") (name "UART8_TX") (class "Default")
      (node (ref "U131") (pin "1") (pinfunction "1_1") (pintype "input"))
      (node (ref "U65") (pin "C4") (pinfunction "PE1_C4") (pintype "input"))
    )
    (net (code "140") (name "USART1_RX") (class "Default")
      (node (ref "R195") (pin "1") (pinfunction "1_1") (pintype "input"))
      (node (ref "U65") (pin "G10") (pinfunction "PB15_G10") (pintype "input"))
    )
    (net (code "141") (name "USART1_RX_GPS") (class "Default")
      (node (ref "R195") (pin "2") (pinfunction "2_2") (pintype "input"))
      (node (ref "U126") (pin "3") (pinfunction "3_3") (pintype "unspecified"))
      (node (ref "U177") (pin "1") (pinfunction "1_1") (pintype "input"))
    )
    (net (code "142") (name "USART1_TX") (class "Default")
      (node (ref "R194") (pin "1") (pinfunction "1_1") (pintype "input"))
      (node (ref "U65") (pin "B5") (pinfunction "PB6_B5") (pintype "input"))
    )
    (net (code "143") (name "USART1_TX_GPS") (class "Default")
      (node (ref "R194") (pin "2") (pinfunction "2_2") (pintype "input"))
      (node (ref "U126") (pin "2") (pinfunction "2_2") (pintype "unspecified"))
      (node (ref "U176") (pin "1") (pinfunction "1_1") (pintype "input"))
    )
    (net (code "144") (name "USART2_CTS") (class "Default")
      (node (ref "R179") (pin "1") (pinfunction "1_1") (pintype "input"))
      (node (ref "U65") (pin "C7") (pinfunction "PD3_C7") (pintype "input"))
    )
    (net (code "145") (name "USART2_RTS") (class "Default")
      (node (ref "R178") (pin "1") (pinfunction "1_1") (pintype "input"))
      (node (ref "U65") (pin "D7") (pinfunction "PD4_D7") (pintype "input"))
    )
    (net (code "146") (name "USART2_RX") (class "Default")
      (node (ref "R177") (pin "1") (pinfunction "1_1") (pintype "input"))
      (node (ref "U65") (pin "C6") (pinfunction "PD6_C6") (pintype "input"))
    )
    (net (code "147") (name "USART2_TX") (class "Default")
      (node (ref "R176") (pin "1") (pinfunction "1_1") (pintype "input"))
      (node (ref "U65") (pin "B6") (pinfunction "PD5_B6") (pintype "input"))
    )
    (net (code "148") (name "USART3_CTS") (class "Default")
      (node (ref "R183") (pin "1") (pinfunction "1_1") (pintype "input"))
      (node (ref "U65") (pin "G9") (pinfunction "PD11_G9") (pintype "input"))
    )
    (net (code "149") (name "USART3_RTS") (class "Default")
      (node (ref "R182") (pin "1") (pinfunction "1_1") (pintype "input"))
      (node (ref "U65") (pin "H10") (pinfunction "PB14_H10") (pintype "input"))
    )
    (net (code "150") (name "USART3_RX") (class "Default")
      (node (ref "R181") (pin "1") (pinfunction "1_1") (pintype "input"))
      (node (ref "U65") (pin "J9") (pinfunction "PD9_J9") (pintype "input"))
    )
    (net (code "151") (name "USART3_TX") (class "Default")
      (node (ref "R180") (pin "1") (pinfunction "1_1") (pintype "input"))
      (node (ref "U65") (pin "K9") (pinfunction "PD8_K9") (pintype "input"))
    )
    (net (code "152") (name "USART6_RX") (class "Default")
      (node (ref "U142") (pin "1") (pinfunction "1_1") (pintype "input"))
      (node (ref "U65") (pin "E10") (pinfunction "PC7_E10") (pintype "input"))
    )
    (net (code "153") (name "USART6_TX") (class "Default")
      (node (ref "U139") (pin "1") (pinfunction "1_1") (pintype "input"))
      (node (ref "U65") (pin "F10") (pinfunction "PC6_F10") (pintype "input"))
    )
    (net (code "154") (name "USB_5V") (class "Default")
      (node (ref "D4") (pin "2") (pinfunction "A_2") (pintype "unspecified"))
      (node (ref "R119") (pin "1") (pinfunction "1_1") (pintype "input"))
      (node (ref "USB1") (pin "A4B9") (pinfunction "VBUS_A4B9") (pintype "input"))
      (node (ref "USB1") (pin "B4A9") (pinfunction "VBUS_B4A9") (pintype "input"))
    )
    (net (code "155") (name "USB_DM") (class "Default")
      (node (ref "R102") (pin "2") (pinfunction "2_2") (pintype "input"))
      (node (ref "U198") (pin "1") (pinfunction "1_1") (pintype "input"))
      (node (ref "U65") (pin "C10") (pinfunction "PA11_C10") (pintype "input"))
    )
    (net (code "156") (name "USB_DP") (class "Default")
      (node (ref "R101") (pin "2") (pinfunction "2_2") (pintype "input"))
      (node (ref "U197") (pin "1") (pinfunction "1_1") (pintype "input"))
      (node (ref "U65") (pin "B10") (pinfunction "PA12_B10") (pintype "input"))
    )
    (net (code "157") (name "VBAT") (class "Default")
      (node (ref "C160") (pin "2") (pinfunction "2_2") (pintype "input"))
      (node (ref "C161") (pin "2") (pinfunction "2_2") (pintype "input"))
      (node (ref "C166") (pin "2") (pinfunction "2_2") (pintype "input"))
      (node (ref "C167") (pin "2") (pinfunction "2_2") (pintype "input"))
      (node (ref "D2") (pin "1") (pinfunction "K_1") (pintype "input"))
      (node (ref "R170") (pin "2") (pinfunction "2_2") (pintype "input"))
      (node (ref "R204") (pin "2") (pinfunction "2_2") (pintype "input"))
      (node (ref "R211") (pin "2") (pinfunction "2_2") (pintype "input"))
      (node (ref "U147") (pin "1") (pinfunction "1_1") (pintype "input"))
      (node (ref "U192") (pin "1") (pinfunction "1_1") (pintype "input"))
      (node (ref "U205") (pin "8") (pinfunction "VIN_8") (pintype "unspecified"))
      (node (ref "U205") (pin "9") (pinfunction "VIN_9") (pintype "unspecified"))
      (node (ref "U206") (pin "8") (pinfunction "VIN_8") (pintype "unspecified"))
      (node (ref "U206") (pin "9") (pinfunction "VIN_9") (pintype "unspecified"))
      (node (ref "U60") (pin "2") (pinfunction "2_2") (pintype "unspecified"))
      (node (ref "U70") (pin "2") (pinfunction "2_2") (pintype "unspecified"))
    )
    (net (code "158") (name "VBAT_ADC") (class "Default")
      (node (ref "C82") (pin "2") (pinfunction "2_2") (pintype "input"))
      (node (ref "R170") (pin "1") (pinfunction "1_1") (pintype "input"))
      (node (ref "R171") (pin "1") (pinfunction "1_1") (pintype "input"))
      (node (ref "U65") (pin "F1") (pinfunction "PC0_F1") (pintype "input"))
    )
    (net (code "159") (name "VBUS_SENSING") (class "Default")
      (node (ref "R118") (pin "2") (pinfunction "2_2") (pintype "input"))
      (node (ref "R119") (pin "2") (pinfunction "2_2") (pintype "input"))
      (node (ref "U65") (pin "G6") (pinfunction "PE10_G6") (pintype "input"))
    )
    (net (code "160") (name "VCAP1") (class "Default")
      (node (ref "C89") (pin "2") (pinfunction "2_2") (pintype "unspecified"))
      (node (ref "U65") (pin "F8") (pinfunction "VCAP_F8") (pintype "input"))
    )
    (net (code "161") (name "VCAP2") (class "Default")
      (node (ref "C90") (pin "2") (pinfunction "2_2") (pintype "unspecified"))
      (node (ref "U65") (pin "E7") (pinfunction "VCAP_E7") (pintype "input"))
    )
    (net (code "162") (name "VDD_5V_IN") (class "Default")
      (node (ref "C121") (pin "1") (pinfunction "1_1") (pintype "unspecified"))
      (node (ref "C122") (pin "1") (pinfunction "1_1") (pintype "unspecified"))
      (node (ref "C123") (pin "1") (pinfunction "1_1") (pintype "unspecified"))
      (node (ref "C146") (pin "2") (pinfunction "2_2") (pintype "unspecified"))
      (node (ref "C147") (pin "2") (pinfunction "2_2") (pintype "unspecified"))
      (node (ref "C150") (pin "1") (pinfunction "1_1") (pintype "input"))
      (node (ref "C154") (pin "2") (pinfunction "2_2") (pintype "unspecified"))
      (node (ref "C155") (pin "2") (pinfunction "2_2") (pintype "unspecified"))
      (node (ref "C156") (pin "1") (pinfunction "1_1") (pintype "input"))
      (node (ref "D4") (pin "1") (pinfunction "K_1") (pintype "unspecified"))
      (node (ref "D5") (pin "1") (pinfunction "K_1") (pintype "unspecified"))
      (node (ref "R130") (pin "2") (pinfunction "2_2") (pintype "input"))
      (node (ref "R131") (pin "1") (pinfunction "1_1") (pintype "input"))
      (node (ref "R143") (pin "1") (pinfunction "1_1") (pintype "input"))
      (node (ref "R197") (pin "2") (pinfunction "2_2") (pintype "input"))
      (node (ref "R198") (pin "2") (pinfunction "2_2") (pintype "input"))
      (node (ref "R200") (pin "2") (pinfunction "2_2") (pintype "input"))
      (node (ref "R201") (pin "2") (pinfunction "2_2") (pintype "input"))
      (node (ref "U114") (pin "1") (pinfunction "1_1") (pintype "input"))
      (node (ref "U119") (pin "1") (pinfunction "1_1") (pintype "unspecified"))
      (node (ref "U120") (pin "1") (pinfunction "1_1") (pintype "unspecified"))
      (node (ref "U125") (pin "1") (pinfunction "1_1") (pintype "unspecified"))
      (node (ref "U126") (pin "1") (pinfunction "1_1") (pintype "unspecified"))
      (node (ref "U128") (pin "1") (pinfunction "1_1") (pintype "input"))
      (node (ref "U132") (pin "1") (pinfunction "1_1") (pintype "input"))
      (node (ref "U136") (pin "1") (pinfunction "1_1") (pintype "input"))
      (node (ref "U140") (pin "1") (pinfunction "1_1") (pintype "input"))
      (node (ref "U144") (pin "1") (pinfunction "1_1") (pintype "input"))
      (node (ref "U162") (pin "1") (pinfunction "1_1") (pintype "input"))
      (node (ref "U164") (pin "1") (pinfunction "1_1") (pintype "input"))
      (node (ref "U172") (pin "1") (pinfunction "1_1") (pintype "input"))
      (node (ref "U178") (pin "1") (pinfunction "1_1") (pintype "input"))
      (node (ref "U182") (pin "1") (pinfunction "1_1") (pintype "input"))
      (node (ref "U185") (pin "1") (pinfunction "1_1") (pintype "input"))
      (node (ref "U189") (pin "1") (pinfunction "1_1") (pintype "input"))
      (node (ref "U194") (pin "1") (pinfunction "1_1") (pintype "input"))
      (node (ref "U200") (pin "1") (pinfunction "1_1") (pintype "input"))
      (node (ref "U204") (pin "6") (pinfunction "IN_6") (pintype "input"))
      (node (ref "U38") (pin "3") (pinfunction "VCC_3") (pintype "input"))
      (node (ref "U6") (pin "21") (pinfunction "AVDD_21") (pintype "input"))
      (node (ref "U6") (pin "24") (pinfunction "PVDD_24") (pintype "input"))
      (node (ref "U6") (pin "3") (pinfunction "DVDD_3") (pintype "input"))
      (node (ref "U67") (pin "3") (pinfunction "VCC_3") (pintype "input"))
      (node (ref "U71") (pin "1") (pinfunction "1_1") (pintype "unspecified"))
      (node (ref "U98") (pin "6") (pinfunction "IN_6") (pintype "input"))
    )
    (net (code "163") (name "VTX") (class "Default")
      (node (ref "R128") (pin "2") (pinfunction "2_2") (pintype "input"))
      (node (ref "U196") (pin "1") (pinfunction "1_1") (pintype "input"))
    )
    (net (code "164") (name "W2815") (class "Default")
      (node (ref "U187") (pin "1") (pinfunction "1_1") (pintype "input"))
      (node (ref "U65") (pin "A7") (pinfunction "PB3_A7") (pintype "input"))
    )
    (net (code "165") (name "unconnected-(CARD4-DAT1-Pad8)") (class "Default")
      (node (ref "CARD4") (pin "8") (pinfunction "DAT1_8") (pintype "input+no_connect"))
    )
    (net (code "166") (name "unconnected-(CARD4-DAT2-Pad1)") (class "Default")
      (node (ref "CARD4") (pin "1") (pinfunction "DAT2_1") (pintype "input+no_connect"))
    )
    (net (code "167") (name "unconnected-(U6-CLKOUT-Pad7)") (class "Default")
      (node (ref "U6") (pin "7") (pinfunction "CLKOUT_7") (pintype "input+no_connect"))
    )
    (net (code "168") (name "unconnected-(U6-HSYNC#-Pad18)") (class "Default")
      (node (ref "U6") (pin "18") (pinfunction "HSYNC#_18") (pintype "input+no_connect"))
    )
    (net (code "169") (name "unconnected-(U6-LOS-Pad12)") (class "Default")
      (node (ref "U6") (pin "12") (pinfunction "LOS_12") (pintype "input+no_connect"))
    )
    (net (code "170") (name "unconnected-(U6-NC-Pad1)") (class "Default")
      (node (ref "U6") (pin "1") (pinfunction "NC_1") (pintype "input+no_connect"))
    )
    (net (code "171") (name "unconnected-(U6-NC-Pad2)") (class "Default")
      (node (ref "U6") (pin "2") (pinfunction "NC_2") (pintype "input+no_connect"))
    )
    (net (code "172") (name "unconnected-(U6-NC-Pad14)") (class "Default")
      (node (ref "U6") (pin "14") (pinfunction "NC_14") (pintype "input+no_connect"))
    )
    (net (code "173") (name "unconnected-(U6-NC-Pad15)") (class "Default")
      (node (ref "U6") (pin "15") (pinfunction "NC_15") (pintype "input+no_connect"))
    )
    (net (code "174") (name "unconnected-(U6-NC-Pad16)") (class "Default")
      (node (ref "U6") (pin "16") (pinfunction "NC_16") (pintype "input+no_connect"))
    )
    (net (code "175") (name "unconnected-(U6-NC-Pad27)") (class "Default")
      (node (ref "U6") (pin "27") (pinfunction "NC_27") (pintype "input+no_connect"))
    )
    (net (code "176") (name "unconnected-(U6-NC-Pad28)") (class "Default")
      (node (ref "U6") (pin "28") (pinfunction "NC_28") (pintype "input+no_connect"))
    )
    (net (code "177") (name "unconnected-(U6-SYNC_IN-Pad13)") (class "Default")
      (node (ref "U6") (pin "13") (pinfunction "SYNC_IN_13") (pintype "input+no_connect"))
    )
    (net (code "178") (name "unconnected-(U6-VSYNC#-Pad17)") (class "Default")
      (node (ref "U6") (pin "17") (pinfunction "VSYNC#_17") (pintype "input+no_connect"))
    )
    (net (code "179") (name "unconnected-(U30-RESV-Pad2)") (class "Default")
      (node (ref "U30") (pin "2") (pinfunction "RESV_2") (pintype "unspecified+no_connect"))
    )
    (net (code "180") (name "unconnected-(U30-RESV-Pad3)") (class "Default")
      (node (ref "U30") (pin "3") (pinfunction "RESV_3") (pintype "unspecified+no_connect"))
    )
    (net (code "181") (name "unconnected-(U30-RESV-Pad10)") (class "Default")
      (node (ref "U30") (pin "10") (pinfunction "RESV_10") (pintype "unspecified+no_connect"))
    )
    (net (code "182") (name "unconnected-(U30-RESV-Pad11)") (class "Default")
      (node (ref "U30") (pin "11") (pinfunction "RESV_11") (pintype "unspecified+no_connect"))
    )
    (net (code "183") (name "unconnected-(U37-DRDY-Pad15)") (class "Default")
      (node (ref "U37") (pin "15") (pinfunction "DRDY_15") (pintype "unspecified+no_connect"))
    )
    (net (code "184") (name "unconnected-(U37-VPP-Pad7)") (class "Default")
      (node (ref "U37") (pin "7") (pinfunction "VPP_7") (pintype "unspecified+no_connect"))
    )
    (net (code "185") (name "unconnected-(U58-RESV-Pad2)") (class "Default")
      (node (ref "U58") (pin "2") (pinfunction "RESV_2") (pintype "unspecified+no_connect"))
    )
    (net (code "186") (name "unconnected-(U58-RESV-Pad3)") (class "Default")
      (node (ref "U58") (pin "3") (pinfunction "RESV_3") (pintype "unspecified+no_connect"))
    )
    (net (code "187") (name "unconnected-(U58-RESV-Pad10)") (class "Default")
      (node (ref "U58") (pin "10") (pinfunction "RESV_10") (pintype "unspecified+no_connect"))
    )
    (net (code "188") (name "unconnected-(U58-RESV-Pad11)") (class "Default")
      (node (ref "U58") (pin "11") (pinfunction "RESV_11") (pintype "unspecified+no_connect"))
    )
    (net (code "189") (name "unconnected-(U59-CSB-Pad4)") (class "Default")
      (node (ref "U59") (pin "4") (pinfunction "CSB_4") (pintype "unspecified"))
    )
    (net (code "190") (name "unconnected-(U65-PB0-PadJ4)") (class "Default")
      (node (ref "U65") (pin "J4") (pinfunction "PB0_J4") (pintype "input"))
    )
    (net (code "191") (name "unconnected-(U65-PC15-OSC32_OUT-PadB1)") (class "Default")
      (node (ref "U65") (pin "B1") (pinfunction "PC15-OSC32_OUT_B1") (pintype "input+no_connect"))
    )
    (net (code "192") (name "unconnected-(U65-PE12-PadJ6)") (class "Default")
      (node (ref "U65") (pin "J6") (pinfunction "PE12_J6") (pintype "input"))
    )
    (net (code "193") (name "unconnected-(U65-PE13-PadK6)") (class "Default")
      (node (ref "U65") (pin "K6") (pinfunction "PE13_K6") (pintype "input"))
    )
    (net (code "194") (name "unconnected-(U98-NC-Pad2)") (class "Default")
      (node (ref "U98") (pin "2") (pinfunction "NC_2") (pintype "input+no_connect"))
    )
    (net (code "195") (name "unconnected-(U204-NC-Pad2)") (class "Default")
      (node (ref "U204") (pin "2") (pinfunction "NC_2") (pintype "input+no_connect"))
    )
    (net (code "196") (name "unconnected-(USB1-SBU1-PadA8)") (class "Default")
      (node (ref "USB1") (pin "A8") (pinfunction "SBU1_A8") (pintype "input+no_connect"))
    )
    (net (code "197") (name "unconnected-(USB1-SBU2-PadB8)") (class "Default")
      (node (ref "USB1") (pin "B8") (pinfunction "SBU2_B8") (pintype "input+no_connect"))
    )
  )
)
